# W952.net
KiCad netlist of a schematic drawn in EAGLE
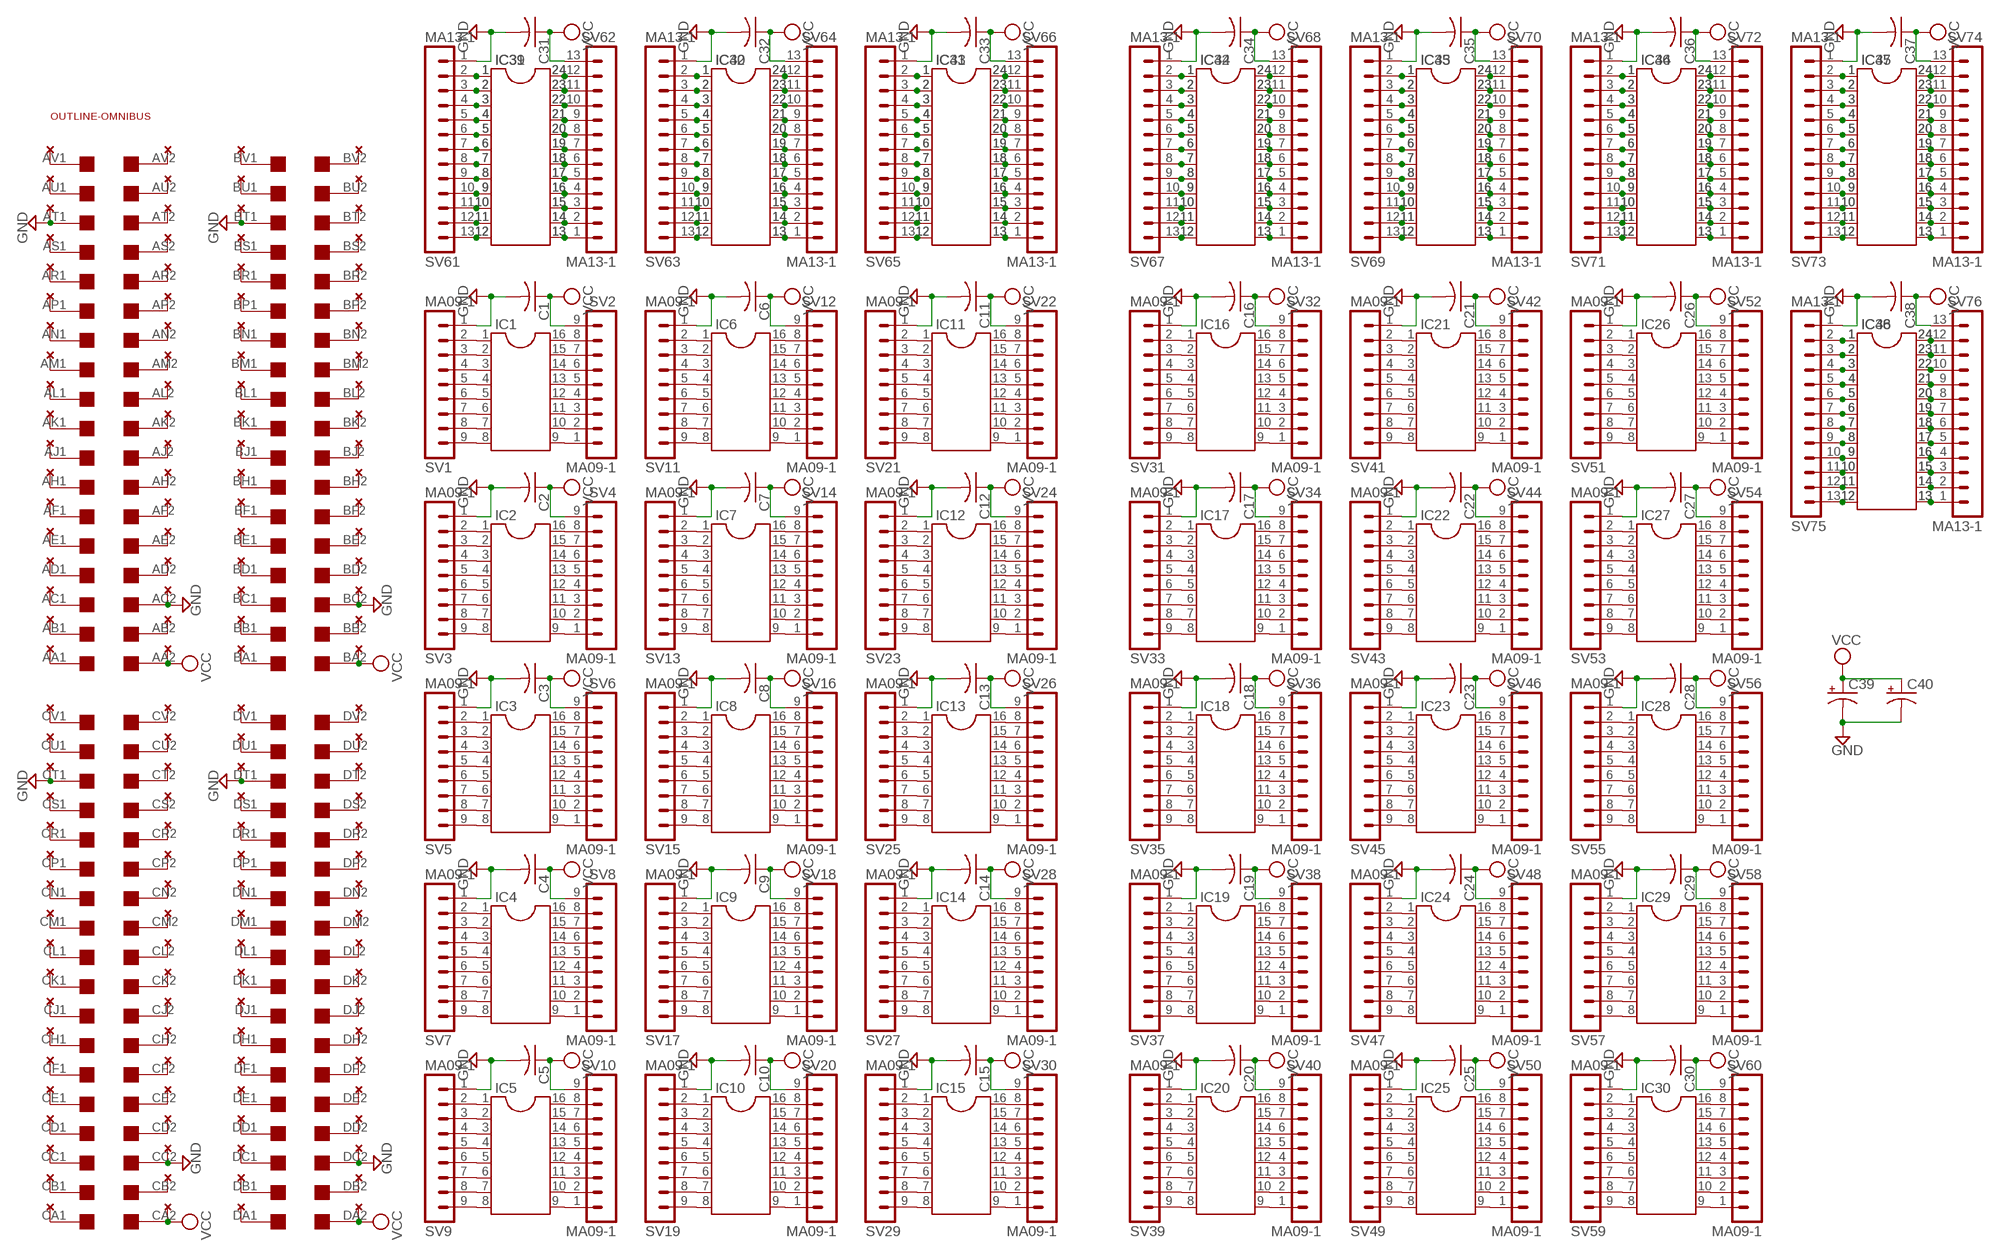
[diagram p0: schematic, sheet 1]

(export (version "E")
  (design (tool "Eeschema 10.0.6"))
  (components
    (comp (ref "C1")
      (value "C-US075-032X103")
      (footprint "eagle-import:C075-032X103")
      (libsource (lib "eagle-import") (part "C-US075-032X103"))
    )
    (comp (ref "C2")
      (value "C-US075-032X103")
      (footprint "eagle-import:C075-032X103")
      (libsource (lib "eagle-import") (part "C-US075-032X103"))
    )
    (comp (ref "C3")
      (value "C-US075-032X103")
      (footprint "eagle-import:C075-032X103")
      (libsource (lib "eagle-import") (part "C-US075-032X103"))
    )
    (comp (ref "C4")
      (value "C-US075-032X103")
      (footprint "eagle-import:C075-032X103")
      (libsource (lib "eagle-import") (part "C-US075-032X103"))
    )
    (comp (ref "C5")
      (value "C-US075-032X103")
      (footprint "eagle-import:C075-032X103")
      (libsource (lib "eagle-import") (part "C-US075-032X103"))
    )
    (comp (ref "C6")
      (value "C-US075-032X103")
      (footprint "eagle-import:C075-032X103")
      (libsource (lib "eagle-import") (part "C-US075-032X103"))
    )
    (comp (ref "C7")
      (value "C-US075-032X103")
      (footprint "eagle-import:C075-032X103")
      (libsource (lib "eagle-import") (part "C-US075-032X103"))
    )
    (comp (ref "C8")
      (value "C-US075-032X103")
      (footprint "eagle-import:C075-032X103")
      (libsource (lib "eagle-import") (part "C-US075-032X103"))
    )
    (comp (ref "C9")
      (value "C-US075-032X103")
      (footprint "eagle-import:C075-032X103")
      (libsource (lib "eagle-import") (part "C-US075-032X103"))
    )
    (comp (ref "C10")
      (value "C-US075-032X103")
      (footprint "eagle-import:C075-032X103")
      (libsource (lib "eagle-import") (part "C-US075-032X103"))
    )
    (comp (ref "C11")
      (value "C-US075-032X103")
      (footprint "eagle-import:C075-032X103")
      (libsource (lib "eagle-import") (part "C-US075-032X103"))
    )
    (comp (ref "C12")
      (value "C-US075-032X103")
      (footprint "eagle-import:C075-032X103")
      (libsource (lib "eagle-import") (part "C-US075-032X103"))
    )
    (comp (ref "C13")
      (value "C-US075-032X103")
      (footprint "eagle-import:C075-032X103")
      (libsource (lib "eagle-import") (part "C-US075-032X103"))
    )
    (comp (ref "C14")
      (value "C-US075-032X103")
      (footprint "eagle-import:C075-032X103")
      (libsource (lib "eagle-import") (part "C-US075-032X103"))
    )
    (comp (ref "C15")
      (value "C-US075-032X103")
      (footprint "eagle-import:C075-032X103")
      (libsource (lib "eagle-import") (part "C-US075-032X103"))
    )
    (comp (ref "C16")
      (value "C-US075-032X103")
      (footprint "eagle-import:C075-032X103")
      (libsource (lib "eagle-import") (part "C-US075-032X103"))
    )
    (comp (ref "C17")
      (value "C-US075-032X103")
      (footprint "eagle-import:C075-032X103")
      (libsource (lib "eagle-import") (part "C-US075-032X103"))
    )
    (comp (ref "C18")
      (value "C-US075-032X103")
      (footprint "eagle-import:C075-032X103")
      (libsource (lib "eagle-import") (part "C-US075-032X103"))
    )
    (comp (ref "C19")
      (value "C-US075-032X103")
      (footprint "eagle-import:C075-032X103")
      (libsource (lib "eagle-import") (part "C-US075-032X103"))
    )
    (comp (ref "C20")
      (value "C-US075-032X103")
      (footprint "eagle-import:C075-032X103")
      (libsource (lib "eagle-import") (part "C-US075-032X103"))
    )
    (comp (ref "C21")
      (value "C-US075-032X103")
      (footprint "eagle-import:C075-032X103")
      (libsource (lib "eagle-import") (part "C-US075-032X103"))
    )
    (comp (ref "C22")
      (value "C-US075-032X103")
      (footprint "eagle-import:C075-032X103")
      (libsource (lib "eagle-import") (part "C-US075-032X103"))
    )
    (comp (ref "C23")
      (value "C-US075-032X103")
      (footprint "eagle-import:C075-032X103")
      (libsource (lib "eagle-import") (part "C-US075-032X103"))
    )
    (comp (ref "C24")
      (value "C-US075-032X103")
      (footprint "eagle-import:C075-032X103")
      (libsource (lib "eagle-import") (part "C-US075-032X103"))
    )
    (comp (ref "C25")
      (value "C-US075-032X103")
      (footprint "eagle-import:C075-032X103")
      (libsource (lib "eagle-import") (part "C-US075-032X103"))
    )
    (comp (ref "C26")
      (value "C-US075-032X103")
      (footprint "eagle-import:C075-032X103")
      (libsource (lib "eagle-import") (part "C-US075-032X103"))
    )
    (comp (ref "C27")
      (value "C-US075-032X103")
      (footprint "eagle-import:C075-032X103")
      (libsource (lib "eagle-import") (part "C-US075-032X103"))
    )
    (comp (ref "C28")
      (value "C-US075-032X103")
      (footprint "eagle-import:C075-032X103")
      (libsource (lib "eagle-import") (part "C-US075-032X103"))
    )
    (comp (ref "C29")
      (value "C-US075-032X103")
      (footprint "eagle-import:C075-032X103")
      (libsource (lib "eagle-import") (part "C-US075-032X103"))
    )
    (comp (ref "C30")
      (value "C-US075-032X103")
      (footprint "eagle-import:C075-032X103")
      (libsource (lib "eagle-import") (part "C-US075-032X103"))
    )
    (comp (ref "C31")
      (value "C-US075-032X103")
      (footprint "eagle-import:C075-032X103")
      (libsource (lib "eagle-import") (part "C-US075-032X103"))
    )
    (comp (ref "C32")
      (value "C-US075-032X103")
      (footprint "eagle-import:C075-032X103")
      (libsource (lib "eagle-import") (part "C-US075-032X103"))
    )
    (comp (ref "C33")
      (value "C-US075-032X103")
      (footprint "eagle-import:C075-032X103")
      (libsource (lib "eagle-import") (part "C-US075-032X103"))
    )
    (comp (ref "C34")
      (value "C-US075-032X103")
      (footprint "eagle-import:C075-032X103")
      (libsource (lib "eagle-import") (part "C-US075-032X103"))
    )
    (comp (ref "C35")
      (value "C-US075-032X103")
      (footprint "eagle-import:C075-032X103")
      (libsource (lib "eagle-import") (part "C-US075-032X103"))
    )
    (comp (ref "C36")
      (value "C-US075-032X103")
      (footprint "eagle-import:C075-032X103")
      (libsource (lib "eagle-import") (part "C-US075-032X103"))
    )
    (comp (ref "C37")
      (value "C-US075-032X103")
      (footprint "eagle-import:C075-032X103")
      (libsource (lib "eagle-import") (part "C-US075-032X103"))
    )
    (comp (ref "C38")
      (value "C-US075-032X103")
      (footprint "eagle-import:C075-032X103")
      (libsource (lib "eagle-import") (part "C-US075-032X103"))
    )
    (comp (ref "C39")
      (value "CPOL-USE15-5AXIAL")
      (footprint "eagle-import:E15-5")
      (libsource (lib "eagle-import") (part "CPOL-USE15-5AXIAL"))
    )
    (comp (ref "C40")
      (value "CPOL-USE15-5AXIAL")
      (footprint "eagle-import:E15-5")
      (libsource (lib "eagle-import") (part "CPOL-USE15-5AXIAL"))
    )
    (comp (ref "IC1")
      (value "DIL16S")
      (footprint "eagle-import:SOCKET-16")
      (libsource (lib "eagle-import") (part "DIL16S"))
    )
    (comp (ref "IC2")
      (value "DIL16S")
      (footprint "eagle-import:SOCKET-16")
      (libsource (lib "eagle-import") (part "DIL16S"))
    )
    (comp (ref "IC3")
      (value "DIL16S")
      (footprint "eagle-import:SOCKET-16")
      (libsource (lib "eagle-import") (part "DIL16S"))
    )
    (comp (ref "IC4")
      (value "DIL16S")
      (footprint "eagle-import:SOCKET-16")
      (libsource (lib "eagle-import") (part "DIL16S"))
    )
    (comp (ref "IC5")
      (value "DIL16S")
      (footprint "eagle-import:SOCKET-16")
      (libsource (lib "eagle-import") (part "DIL16S"))
    )
    (comp (ref "IC6")
      (value "DIL16S")
      (footprint "eagle-import:SOCKET-16")
      (libsource (lib "eagle-import") (part "DIL16S"))
    )
    (comp (ref "IC7")
      (value "DIL16S")
      (footprint "eagle-import:SOCKET-16")
      (libsource (lib "eagle-import") (part "DIL16S"))
    )
    (comp (ref "IC8")
      (value "DIL16S")
      (footprint "eagle-import:SOCKET-16")
      (libsource (lib "eagle-import") (part "DIL16S"))
    )
    (comp (ref "IC9")
      (value "DIL16S")
      (footprint "eagle-import:SOCKET-16")
      (libsource (lib "eagle-import") (part "DIL16S"))
    )
    (comp (ref "IC10")
      (value "DIL16S")
      (footprint "eagle-import:SOCKET-16")
      (libsource (lib "eagle-import") (part "DIL16S"))
    )
    (comp (ref "IC11")
      (value "DIL16S")
      (footprint "eagle-import:SOCKET-16")
      (libsource (lib "eagle-import") (part "DIL16S"))
    )
    (comp (ref "IC12")
      (value "DIL16S")
      (footprint "eagle-import:SOCKET-16")
      (libsource (lib "eagle-import") (part "DIL16S"))
    )
    (comp (ref "IC13")
      (value "DIL16S")
      (footprint "eagle-import:SOCKET-16")
      (libsource (lib "eagle-import") (part "DIL16S"))
    )
    (comp (ref "IC14")
      (value "DIL16S")
      (footprint "eagle-import:SOCKET-16")
      (libsource (lib "eagle-import") (part "DIL16S"))
    )
    (comp (ref "IC15")
      (value "DIL16S")
      (footprint "eagle-import:SOCKET-16")
      (libsource (lib "eagle-import") (part "DIL16S"))
    )
    (comp (ref "IC16")
      (value "DIL16S")
      (footprint "eagle-import:SOCKET-16")
      (libsource (lib "eagle-import") (part "DIL16S"))
    )
    (comp (ref "IC17")
      (value "DIL16S")
      (footprint "eagle-import:SOCKET-16")
      (libsource (lib "eagle-import") (part "DIL16S"))
    )
    (comp (ref "IC18")
      (value "DIL16S")
      (footprint "eagle-import:SOCKET-16")
      (libsource (lib "eagle-import") (part "DIL16S"))
    )
    (comp (ref "IC19")
      (value "DIL16S")
      (footprint "eagle-import:SOCKET-16")
      (libsource (lib "eagle-import") (part "DIL16S"))
    )
    (comp (ref "IC20")
      (value "DIL16S")
      (footprint "eagle-import:SOCKET-16")
      (libsource (lib "eagle-import") (part "DIL16S"))
    )
    (comp (ref "IC21")
      (value "DIL16S")
      (footprint "eagle-import:SOCKET-16")
      (libsource (lib "eagle-import") (part "DIL16S"))
    )
    (comp (ref "IC22")
      (value "DIL16S")
      (footprint "eagle-import:SOCKET-16")
      (libsource (lib "eagle-import") (part "DIL16S"))
    )
    (comp (ref "IC23")
      (value "DIL16S")
      (footprint "eagle-import:SOCKET-16")
      (libsource (lib "eagle-import") (part "DIL16S"))
    )
    (comp (ref "IC24")
      (value "DIL16S")
      (footprint "eagle-import:SOCKET-16")
      (libsource (lib "eagle-import") (part "DIL16S"))
    )
    (comp (ref "IC25")
      (value "DIL16S")
      (footprint "eagle-import:SOCKET-16")
      (libsource (lib "eagle-import") (part "DIL16S"))
    )
    (comp (ref "IC26")
      (value "DIL16S")
      (footprint "eagle-import:SOCKET-16")
      (libsource (lib "eagle-import") (part "DIL16S"))
    )
    (comp (ref "IC27")
      (value "DIL16S")
      (footprint "eagle-import:SOCKET-16")
      (libsource (lib "eagle-import") (part "DIL16S"))
    )
    (comp (ref "IC28")
      (value "DIL16S")
      (footprint "eagle-import:SOCKET-16")
      (libsource (lib "eagle-import") (part "DIL16S"))
    )
    (comp (ref "IC29")
      (value "DIL16S")
      (footprint "eagle-import:SOCKET-16")
      (libsource (lib "eagle-import") (part "DIL16S"))
    )
    (comp (ref "IC30")
      (value "DIL16S")
      (footprint "eagle-import:SOCKET-16")
      (libsource (lib "eagle-import") (part "DIL16S"))
    )
    (comp (ref "IC31")
      (value "DIL24-6")
      (footprint "eagle-import:DIL24-6")
      (libsource (lib "eagle-import") (part "DIL24-6"))
    )
    (comp (ref "IC32")
      (value "DIL24-6")
      (footprint "eagle-import:DIL24-6")
      (libsource (lib "eagle-import") (part "DIL24-6"))
    )
    (comp (ref "IC33")
      (value "DIL24-6")
      (footprint "eagle-import:DIL24-6")
      (libsource (lib "eagle-import") (part "DIL24-6"))
    )
    (comp (ref "IC34")
      (value "DIL24-6")
      (footprint "eagle-import:DIL24-6")
      (libsource (lib "eagle-import") (part "DIL24-6"))
    )
    (comp (ref "IC35")
      (value "DIL24-6")
      (footprint "eagle-import:DIL24-6")
      (libsource (lib "eagle-import") (part "DIL24-6"))
    )
    (comp (ref "IC36")
      (value "DIL24-6")
      (footprint "eagle-import:DIL24-6")
      (libsource (lib "eagle-import") (part "DIL24-6"))
    )
    (comp (ref "IC37")
      (value "DIL24-6")
      (footprint "eagle-import:DIL24-6")
      (libsource (lib "eagle-import") (part "DIL24-6"))
    )
    (comp (ref "IC38")
      (value "DIL24-6")
      (footprint "eagle-import:DIL24-6")
      (libsource (lib "eagle-import") (part "DIL24-6"))
    )
    (comp (ref "IC39")
      (value "DIL24-3")
      (footprint "eagle-import:DIL24-3")
      (libsource (lib "eagle-import") (part "DIL24-3"))
    )
    (comp (ref "IC40")
      (value "DIL24-3")
      (footprint "eagle-import:DIL24-3")
      (libsource (lib "eagle-import") (part "DIL24-3"))
    )
    (comp (ref "IC41")
      (value "DIL24-3")
      (footprint "eagle-import:DIL24-3")
      (libsource (lib "eagle-import") (part "DIL24-3"))
    )
    (comp (ref "IC42")
      (value "DIL24-3")
      (footprint "eagle-import:DIL24-3")
      (libsource (lib "eagle-import") (part "DIL24-3"))
    )
    (comp (ref "IC43")
      (value "DIL24-3")
      (footprint "eagle-import:DIL24-3")
      (libsource (lib "eagle-import") (part "DIL24-3"))
    )
    (comp (ref "IC44")
      (value "DIL24-3")
      (footprint "eagle-import:DIL24-3")
      (libsource (lib "eagle-import") (part "DIL24-3"))
    )
    (comp (ref "IC45")
      (value "DIL24-3")
      (footprint "eagle-import:DIL24-3")
      (libsource (lib "eagle-import") (part "DIL24-3"))
    )
    (comp (ref "IC46")
      (value "DIL24-3")
      (footprint "eagle-import:DIL24-3")
      (libsource (lib "eagle-import") (part "DIL24-3"))
    )
    (comp (ref "SV1")
      (value "MA09-1")
      (footprint "eagle-import:MA09-1")
      (libsource (lib "eagle-import") (part "MA09-1"))
    )
    (comp (ref "SV2")
      (value "MA09-1")
      (footprint "eagle-import:MA09-1")
      (libsource (lib "eagle-import") (part "MA09-1"))
    )
    (comp (ref "SV3")
      (value "MA09-1")
      (footprint "eagle-import:MA09-1")
      (libsource (lib "eagle-import") (part "MA09-1"))
    )
    (comp (ref "SV4")
      (value "MA09-1")
      (footprint "eagle-import:MA09-1")
      (libsource (lib "eagle-import") (part "MA09-1"))
    )
    (comp (ref "SV5")
      (value "MA09-1")
      (footprint "eagle-import:MA09-1")
      (libsource (lib "eagle-import") (part "MA09-1"))
    )
    (comp (ref "SV6")
      (value "MA09-1")
      (footprint "eagle-import:MA09-1")
      (libsource (lib "eagle-import") (part "MA09-1"))
    )
    (comp (ref "SV7")
      (value "MA09-1")
      (footprint "eagle-import:MA09-1")
      (libsource (lib "eagle-import") (part "MA09-1"))
    )
    (comp (ref "SV8")
      (value "MA09-1")
      (footprint "eagle-import:MA09-1")
      (libsource (lib "eagle-import") (part "MA09-1"))
    )
    (comp (ref "SV9")
      (value "MA09-1")
      (footprint "eagle-import:MA09-1")
      (libsource (lib "eagle-import") (part "MA09-1"))
    )
    (comp (ref "SV10")
      (value "MA09-1")
      (footprint "eagle-import:MA09-1")
      (libsource (lib "eagle-import") (part "MA09-1"))
    )
    (comp (ref "SV11")
      (value "MA09-1")
      (footprint "eagle-import:MA09-1")
      (libsource (lib "eagle-import") (part "MA09-1"))
    )
    (comp (ref "SV12")
      (value "MA09-1")
      (footprint "eagle-import:MA09-1")
      (libsource (lib "eagle-import") (part "MA09-1"))
    )
    (comp (ref "SV13")
      (value "MA09-1")
      (footprint "eagle-import:MA09-1")
      (libsource (lib "eagle-import") (part "MA09-1"))
    )
    (comp (ref "SV14")
      (value "MA09-1")
      (footprint "eagle-import:MA09-1")
      (libsource (lib "eagle-import") (part "MA09-1"))
    )
    (comp (ref "SV15")
      (value "MA09-1")
      (footprint "eagle-import:MA09-1")
      (libsource (lib "eagle-import") (part "MA09-1"))
    )
    (comp (ref "SV16")
      (value "MA09-1")
      (footprint "eagle-import:MA09-1")
      (libsource (lib "eagle-import") (part "MA09-1"))
    )
    (comp (ref "SV17")
      (value "MA09-1")
      (footprint "eagle-import:MA09-1")
      (libsource (lib "eagle-import") (part "MA09-1"))
    )
    (comp (ref "SV18")
      (value "MA09-1")
      (footprint "eagle-import:MA09-1")
      (libsource (lib "eagle-import") (part "MA09-1"))
    )
    (comp (ref "SV19")
      (value "MA09-1")
      (footprint "eagle-import:MA09-1")
      (libsource (lib "eagle-import") (part "MA09-1"))
    )
    (comp (ref "SV20")
      (value "MA09-1")
      (footprint "eagle-import:MA09-1")
      (libsource (lib "eagle-import") (part "MA09-1"))
    )
    (comp (ref "SV21")
      (value "MA09-1")
      (footprint "eagle-import:MA09-1")
      (libsource (lib "eagle-import") (part "MA09-1"))
    )
    (comp (ref "SV22")
      (value "MA09-1")
      (footprint "eagle-import:MA09-1")
      (libsource (lib "eagle-import") (part "MA09-1"))
    )
    (comp (ref "SV23")
      (value "MA09-1")
      (footprint "eagle-import:MA09-1")
      (libsource (lib "eagle-import") (part "MA09-1"))
    )
    (comp (ref "SV24")
      (value "MA09-1")
      (footprint "eagle-import:MA09-1")
      (libsource (lib "eagle-import") (part "MA09-1"))
    )
    (comp (ref "SV25")
      (value "MA09-1")
      (footprint "eagle-import:MA09-1")
      (libsource (lib "eagle-import") (part "MA09-1"))
    )
    (comp (ref "SV26")
      (value "MA09-1")
      (footprint "eagle-import:MA09-1")
      (libsource (lib "eagle-import") (part "MA09-1"))
    )
    (comp (ref "SV27")
      (value "MA09-1")
      (footprint "eagle-import:MA09-1")
      (libsource (lib "eagle-import") (part "MA09-1"))
    )
    (comp (ref "SV28")
      (value "MA09-1")
      (footprint "eagle-import:MA09-1")
      (libsource (lib "eagle-import") (part "MA09-1"))
    )
    (comp (ref "SV29")
      (value "MA09-1")
      (footprint "eagle-import:MA09-1")
      (libsource (lib "eagle-import") (part "MA09-1"))
    )
    (comp (ref "SV30")
      (value "MA09-1")
      (footprint "eagle-import:MA09-1")
      (libsource (lib "eagle-import") (part "MA09-1"))
    )
    (comp (ref "SV31")
      (value "MA09-1")
      (footprint "eagle-import:MA09-1")
      (libsource (lib "eagle-import") (part "MA09-1"))
    )
    (comp (ref "SV32")
      (value "MA09-1")
      (footprint "eagle-import:MA09-1")
      (libsource (lib "eagle-import") (part "MA09-1"))
    )
    (comp (ref "SV33")
      (value "MA09-1")
      (footprint "eagle-import:MA09-1")
      (libsource (lib "eagle-import") (part "MA09-1"))
    )
    (comp (ref "SV34")
      (value "MA09-1")
      (footprint "eagle-import:MA09-1")
      (libsource (lib "eagle-import") (part "MA09-1"))
    )
    (comp (ref "SV35")
      (value "MA09-1")
      (footprint "eagle-import:MA09-1")
      (libsource (lib "eagle-import") (part "MA09-1"))
    )
    (comp (ref "SV36")
      (value "MA09-1")
      (footprint "eagle-import:MA09-1")
      (libsource (lib "eagle-import") (part "MA09-1"))
    )
    (comp (ref "SV37")
      (value "MA09-1")
      (footprint "eagle-import:MA09-1")
      (libsource (lib "eagle-import") (part "MA09-1"))
    )
    (comp (ref "SV38")
      (value "MA09-1")
      (footprint "eagle-import:MA09-1")
      (libsource (lib "eagle-import") (part "MA09-1"))
    )
    (comp (ref "SV39")
      (value "MA09-1")
      (footprint "eagle-import:MA09-1")
      (libsource (lib "eagle-import") (part "MA09-1"))
    )
    (comp (ref "SV40")
      (value "MA09-1")
      (footprint "eagle-import:MA09-1")
      (libsource (lib "eagle-import") (part "MA09-1"))
    )
    (comp (ref "SV41")
      (value "MA09-1")
      (footprint "eagle-import:MA09-1")
      (libsource (lib "eagle-import") (part "MA09-1"))
    )
    (comp (ref "SV42")
      (value "MA09-1")
      (footprint "eagle-import:MA09-1")
      (libsource (lib "eagle-import") (part "MA09-1"))
    )
    (comp (ref "SV43")
      (value "MA09-1")
      (footprint "eagle-import:MA09-1")
      (libsource (lib "eagle-import") (part "MA09-1"))
    )
    (comp (ref "SV44")
      (value "MA09-1")
      (footprint "eagle-import:MA09-1")
      (libsource (lib "eagle-import") (part "MA09-1"))
    )
    (comp (ref "SV45")
      (value "MA09-1")
      (footprint "eagle-import:MA09-1")
      (libsource (lib "eagle-import") (part "MA09-1"))
    )
    (comp (ref "SV46")
      (value "MA09-1")
      (footprint "eagle-import:MA09-1")
      (libsource (lib "eagle-import") (part "MA09-1"))
    )
    (comp (ref "SV47")
      (value "MA09-1")
      (footprint "eagle-import:MA09-1")
      (libsource (lib "eagle-import") (part "MA09-1"))
    )
    (comp (ref "SV48")
      (value "MA09-1")
      (footprint "eagle-import:MA09-1")
      (libsource (lib "eagle-import") (part "MA09-1"))
    )
    (comp (ref "SV49")
      (value "MA09-1")
      (footprint "eagle-import:MA09-1")
      (libsource (lib "eagle-import") (part "MA09-1"))
    )
    (comp (ref "SV50")
      (value "MA09-1")
      (footprint "eagle-import:MA09-1")
      (libsource (lib "eagle-import") (part "MA09-1"))
    )
    (comp (ref "SV51")
      (value "MA09-1")
      (footprint "eagle-import:MA09-1")
      (libsource (lib "eagle-import") (part "MA09-1"))
    )
    (comp (ref "SV52")
      (value "MA09-1")
      (footprint "eagle-import:MA09-1")
      (libsource (lib "eagle-import") (part "MA09-1"))
    )
    (comp (ref "SV53")
      (value "MA09-1")
      (footprint "eagle-import:MA09-1")
      (libsource (lib "eagle-import") (part "MA09-1"))
    )
    (comp (ref "SV54")
      (value "MA09-1")
      (footprint "eagle-import:MA09-1")
      (libsource (lib "eagle-import") (part "MA09-1"))
    )
    (comp (ref "SV55")
      (value "MA09-1")
      (footprint "eagle-import:MA09-1")
      (libsource (lib "eagle-import") (part "MA09-1"))
    )
    (comp (ref "SV56")
      (value "MA09-1")
      (footprint "eagle-import:MA09-1")
      (libsource (lib "eagle-import") (part "MA09-1"))
    )
    (comp (ref "SV57")
      (value "MA09-1")
      (footprint "eagle-import:MA09-1")
      (libsource (lib "eagle-import") (part "MA09-1"))
    )
    (comp (ref "SV58")
      (value "MA09-1")
      (footprint "eagle-import:MA09-1")
      (libsource (lib "eagle-import") (part "MA09-1"))
    )
    (comp (ref "SV59")
      (value "MA09-1")
      (footprint "eagle-import:MA09-1")
      (libsource (lib "eagle-import") (part "MA09-1"))
    )
    (comp (ref "SV60")
      (value "MA09-1")
      (footprint "eagle-import:MA09-1")
      (libsource (lib "eagle-import") (part "MA09-1"))
    )
    (comp (ref "SV61")
      (value "MA13-1")
      (footprint "eagle-import:MA13-1")
      (libsource (lib "eagle-import") (part "MA13-1"))
    )
    (comp (ref "SV62")
      (value "MA13-1")
      (footprint "eagle-import:MA13-1")
      (libsource (lib "eagle-import") (part "MA13-1"))
    )
    (comp (ref "SV63")
      (value "MA13-1")
      (footprint "eagle-import:MA13-1")
      (libsource (lib "eagle-import") (part "MA13-1"))
    )
    (comp (ref "SV64")
      (value "MA13-1")
      (footprint "eagle-import:MA13-1")
      (libsource (lib "eagle-import") (part "MA13-1"))
    )
    (comp (ref "SV65")
      (value "MA13-1")
      (footprint "eagle-import:MA13-1")
      (libsource (lib "eagle-import") (part "MA13-1"))
    )
    (comp (ref "SV66")
      (value "MA13-1")
      (footprint "eagle-import:MA13-1")
      (libsource (lib "eagle-import") (part "MA13-1"))
    )
    (comp (ref "SV67")
      (value "MA13-1")
      (footprint "eagle-import:MA13-1")
      (libsource (lib "eagle-import") (part "MA13-1"))
    )
    (comp (ref "SV68")
      (value "MA13-1")
      (footprint "eagle-import:MA13-1")
      (libsource (lib "eagle-import") (part "MA13-1"))
    )
    (comp (ref "SV69")
      (value "MA13-1")
      (footprint "eagle-import:MA13-1")
      (libsource (lib "eagle-import") (part "MA13-1"))
    )
    (comp (ref "SV70")
      (value "MA13-1")
      (footprint "eagle-import:MA13-1")
      (libsource (lib "eagle-import") (part "MA13-1"))
    )
    (comp (ref "SV71")
      (value "MA13-1")
      (footprint "eagle-import:MA13-1")
      (libsource (lib "eagle-import") (part "MA13-1"))
    )
    (comp (ref "SV72")
      (value "MA13-1")
      (footprint "eagle-import:MA13-1")
      (libsource (lib "eagle-import") (part "MA13-1"))
    )
    (comp (ref "SV73")
      (value "MA13-1")
      (footprint "eagle-import:MA13-1")
      (libsource (lib "eagle-import") (part "MA13-1"))
    )
    (comp (ref "SV74")
      (value "MA13-1")
      (footprint "eagle-import:MA13-1")
      (libsource (lib "eagle-import") (part "MA13-1"))
    )
    (comp (ref "SV75")
      (value "MA13-1")
      (footprint "eagle-import:MA13-1")
      (libsource (lib "eagle-import") (part "MA13-1"))
    )
    (comp (ref "SV76")
      (value "MA13-1")
      (footprint "eagle-import:MA13-1")
      (libsource (lib "eagle-import") (part "MA13-1"))
    )
    (comp (ref "U$1")
      (value "QUAD")
      (footprint "eagle-import:EDGE-CON8")
      (libsource (lib "eagle-import") (part "QUAD"))
    )
    (comp (ref "U$2")
      (value "THRU-HOLE2W")
      (footprint "eagle-import:THRU-HOLE2")
      (libsource (lib "eagle-import") (part "THRU-HOLE2W"))
    )
    (comp (ref "U$3")
      (value "THRU-HOLE2W")
      (footprint "eagle-import:THRU-HOLE2")
      (libsource (lib "eagle-import") (part "THRU-HOLE2W"))
    )
    (comp (ref "U$4")
      (value "THRU-HOLE2W")
      (footprint "eagle-import:THRU-HOLE2")
      (libsource (lib "eagle-import") (part "THRU-HOLE2W"))
    )
    (comp (ref "U$5")
      (value "THRU-HOLE2W")
      (footprint "eagle-import:THRU-HOLE2")
      (libsource (lib "eagle-import") (part "THRU-HOLE2W"))
    )
    (comp (ref "U$8")
      (value "OUTLINE-OMNIBUS")
      (footprint "eagle-import:OMNIBUS")
      (libsource (lib "eagle-import") (part "OUTLINE-OMNIBUS"))
    )
  )
  (nets
    (net (code "1") (name "GND") (class "Default")
      (node (ref "C1") (pin "2") (pinfunction "2_2") (pintype "passive"))
      (node (ref "C10") (pin "2") (pinfunction "2_2") (pintype "passive"))
      (node (ref "C11") (pin "2") (pinfunction "2_2") (pintype "passive"))
      (node (ref "C12") (pin "2") (pinfunction "2_2") (pintype "passive"))
      (node (ref "C13") (pin "2") (pinfunction "2_2") (pintype "passive"))
      (node (ref "C14") (pin "2") (pinfunction "2_2") (pintype "passive"))
      (node (ref "C15") (pin "2") (pinfunction "2_2") (pintype "passive"))
      (node (ref "C16") (pin "2") (pinfunction "2_2") (pintype "passive"))
      (node (ref "C17") (pin "2") (pinfunction "2_2") (pintype "passive"))
      (node (ref "C18") (pin "2") (pinfunction "2_2") (pintype "passive"))
      (node (ref "C19") (pin "2") (pinfunction "2_2") (pintype "passive"))
      (node (ref "C2") (pin "2") (pinfunction "2_2") (pintype "passive"))
      (node (ref "C20") (pin "2") (pinfunction "2_2") (pintype "passive"))
      (node (ref "C21") (pin "2") (pinfunction "2_2") (pintype "passive"))
      (node (ref "C22") (pin "2") (pinfunction "2_2") (pintype "passive"))
      (node (ref "C23") (pin "2") (pinfunction "2_2") (pintype "passive"))
      (node (ref "C24") (pin "2") (pinfunction "2_2") (pintype "passive"))
      (node (ref "C25") (pin "2") (pinfunction "2_2") (pintype "passive"))
      (node (ref "C26") (pin "2") (pinfunction "2_2") (pintype "passive"))
      (node (ref "C27") (pin "2") (pinfunction "2_2") (pintype "passive"))
      (node (ref "C28") (pin "2") (pinfunction "2_2") (pintype "passive"))
      (node (ref "C29") (pin "2") (pinfunction "2_2") (pintype "passive"))
      (node (ref "C3") (pin "2") (pinfunction "2_2") (pintype "passive"))
      (node (ref "C30") (pin "2") (pinfunction "2_2") (pintype "passive"))
      (node (ref "C31") (pin "2") (pinfunction "2_2") (pintype "passive"))
      (node (ref "C32") (pin "2") (pinfunction "2_2") (pintype "passive"))
      (node (ref "C33") (pin "2") (pinfunction "2_2") (pintype "passive"))
      (node (ref "C34") (pin "2") (pinfunction "2_2") (pintype "passive"))
      (node (ref "C35") (pin "2") (pinfunction "2_2") (pintype "passive"))
      (node (ref "C36") (pin "2") (pinfunction "2_2") (pintype "passive"))
      (node (ref "C37") (pin "2") (pinfunction "2_2") (pintype "passive"))
      (node (ref "C38") (pin "2") (pinfunction "2_2") (pintype "passive"))
      (node (ref "C39") (pin "-") (pinfunction "-_-") (pintype "passive"))
      (node (ref "C4") (pin "2") (pinfunction "2_2") (pintype "passive"))
      (node (ref "C40") (pin "-") (pinfunction "-_-") (pintype "passive"))
      (node (ref "C5") (pin "2") (pinfunction "2_2") (pintype "passive"))
      (node (ref "C6") (pin "2") (pinfunction "2_2") (pintype "passive"))
      (node (ref "C7") (pin "2") (pinfunction "2_2") (pintype "passive"))
      (node (ref "C8") (pin "2") (pinfunction "2_2") (pintype "passive"))
      (node (ref "C9") (pin "2") (pinfunction "2_2") (pintype "passive"))
      (node (ref "SV1") (pin "1") (pinfunction "1_1") (pintype "passive"))
      (node (ref "SV11") (pin "1") (pinfunction "1_1") (pintype "passive"))
      (node (ref "SV13") (pin "1") (pinfunction "1_1") (pintype "passive"))
      (node (ref "SV15") (pin "1") (pinfunction "1_1") (pintype "passive"))
      (node (ref "SV17") (pin "1") (pinfunction "1_1") (pintype "passive"))
      (node (ref "SV19") (pin "1") (pinfunction "1_1") (pintype "passive"))
      (node (ref "SV21") (pin "1") (pinfunction "1_1") (pintype "passive"))
      (node (ref "SV23") (pin "1") (pinfunction "1_1") (pintype "passive"))
      (node (ref "SV25") (pin "1") (pinfunction "1_1") (pintype "passive"))
      (node (ref "SV27") (pin "1") (pinfunction "1_1") (pintype "passive"))
      (node (ref "SV29") (pin "1") (pinfunction "1_1") (pintype "passive"))
      (node (ref "SV3") (pin "1") (pinfunction "1_1") (pintype "passive"))
      (node (ref "SV31") (pin "1") (pinfunction "1_1") (pintype "passive"))
      (node (ref "SV33") (pin "1") (pinfunction "1_1") (pintype "passive"))
      (node (ref "SV35") (pin "1") (pinfunction "1_1") (pintype "passive"))
      (node (ref "SV37") (pin "1") (pinfunction "1_1") (pintype "passive"))
      (node (ref "SV39") (pin "1") (pinfunction "1_1") (pintype "passive"))
      (node (ref "SV41") (pin "1") (pinfunction "1_1") (pintype "passive"))
      (node (ref "SV43") (pin "1") (pinfunction "1_1") (pintype "passive"))
      (node (ref "SV45") (pin "1") (pinfunction "1_1") (pintype "passive"))
      (node (ref "SV47") (pin "1") (pinfunction "1_1") (pintype "passive"))
      (node (ref "SV49") (pin "1") (pinfunction "1_1") (pintype "passive"))
      (node (ref "SV5") (pin "1") (pinfunction "1_1") (pintype "passive"))
      (node (ref "SV51") (pin "1") (pinfunction "1_1") (pintype "passive"))
      (node (ref "SV53") (pin "1") (pinfunction "1_1") (pintype "passive"))
      (node (ref "SV55") (pin "1") (pinfunction "1_1") (pintype "passive"))
      (node (ref "SV57") (pin "1") (pinfunction "1_1") (pintype "passive"))
      (node (ref "SV59") (pin "1") (pinfunction "1_1") (pintype "passive"))
      (node (ref "SV61") (pin "1") (pinfunction "1_1") (pintype "passive"))
      (node (ref "SV63") (pin "1") (pinfunction "1_1") (pintype "passive"))
      (node (ref "SV65") (pin "1") (pinfunction "1_1") (pintype "passive"))
      (node (ref "SV67") (pin "1") (pinfunction "1_1") (pintype "passive"))
      (node (ref "SV69") (pin "1") (pinfunction "1_1") (pintype "passive"))
      (node (ref "SV7") (pin "1") (pinfunction "1_1") (pintype "passive"))
      (node (ref "SV71") (pin "1") (pinfunction "1_1") (pintype "passive"))
      (node (ref "SV73") (pin "1") (pinfunction "1_1") (pintype "passive"))
      (node (ref "SV75") (pin "1") (pinfunction "1_1") (pintype "passive"))
      (node (ref "SV9") (pin "1") (pinfunction "1_1") (pintype "passive"))
      (node (ref "U$1") (pin "AC2") (pinfunction "1_AC2") (pintype "bidirectional"))
      (node (ref "U$1") (pin "AT1") (pinfunction "1_AT1") (pintype "bidirectional"))
      (node (ref "U$1") (pin "BC2") (pinfunction "1_BC2") (pintype "bidirectional"))
      (node (ref "U$1") (pin "BT1") (pinfunction "1_BT1") (pintype "bidirectional"))
      (node (ref "U$1") (pin "CC2") (pinfunction "1_CC2") (pintype "bidirectional"))
      (node (ref "U$1") (pin "CT1") (pinfunction "1_CT1") (pintype "bidirectional"))
      (node (ref "U$1") (pin "DC2") (pinfunction "1_DC2") (pintype "bidirectional"))
      (node (ref "U$1") (pin "DT1") (pinfunction "1_DT1") (pintype "bidirectional"))
      (node (ref "U$2") (pin "C1") (pinfunction "P$1_C1") (pintype "passive"))
      (node (ref "U$2") (pin "T2") (pinfunction "P$1_T2") (pintype "passive"))
      (node (ref "U$3") (pin "C1") (pinfunction "P$1_C1") (pintype "passive"))
      (node (ref "U$3") (pin "T2") (pinfunction "P$1_T2") (pintype "passive"))
      (node (ref "U$4") (pin "C1") (pinfunction "P$1_C1") (pintype "passive"))
      (node (ref "U$4") (pin "T2") (pinfunction "P$1_T2") (pintype "passive"))
      (node (ref "U$5") (pin "C1") (pinfunction "P$1_C1") (pintype "passive"))
      (node (ref "U$5") (pin "T2") (pinfunction "P$1_T2") (pintype "passive"))
    )
    (net (code "2") (name "Net-(IC1-Pad1)") (class "Default")
      (node (ref "IC1") (pin "1") (pinfunction "1_1") (pintype "passive"))
      (node (ref "SV1") (pin "2") (pinfunction "2_2") (pintype "passive"))
    )
    (net (code "3") (name "Net-(IC1-Pad2)") (class "Default")
      (node (ref "IC1") (pin "2") (pinfunction "2_2") (pintype "passive"))
      (node (ref "SV1") (pin "3") (pinfunction "3_3") (pintype "passive"))
    )
    (net (code "4") (name "Net-(IC1-Pad3)") (class "Default")
      (node (ref "IC1") (pin "3") (pinfunction "3_3") (pintype "passive"))
      (node (ref "SV1") (pin "4") (pinfunction "4_4") (pintype "passive"))
    )
    (net (code "5") (name "Net-(IC1-Pad4)") (class "Default")
      (node (ref "IC1") (pin "4") (pinfunction "4_4") (pintype "passive"))
      (node (ref "SV1") (pin "5") (pinfunction "5_5") (pintype "passive"))
    )
    (net (code "6") (name "Net-(IC1-Pad5)") (class "Default")
      (node (ref "IC1") (pin "5") (pinfunction "5_5") (pintype "passive"))
      (node (ref "SV1") (pin "6") (pinfunction "6_6") (pintype "passive"))
    )
    (net (code "7") (name "Net-(IC1-Pad6)") (class "Default")
      (node (ref "IC1") (pin "6") (pinfunction "6_6") (pintype "passive"))
      (node (ref "SV1") (pin "7") (pinfunction "7_7") (pintype "passive"))
    )
    (net (code "8") (name "Net-(IC1-Pad7)") (class "Default")
      (node (ref "IC1") (pin "7") (pinfunction "7_7") (pintype "passive"))
      (node (ref "SV1") (pin "8") (pinfunction "8_8") (pintype "passive"))
    )
    (net (code "9") (name "Net-(IC1-Pad8)") (class "Default")
      (node (ref "IC1") (pin "8") (pinfunction "8_8") (pintype "passive"))
      (node (ref "SV1") (pin "9") (pinfunction "9_9") (pintype "passive"))
    )
    (net (code "10") (name "Net-(IC1-Pad9)") (class "Default")
      (node (ref "IC1") (pin "9") (pinfunction "9_9") (pintype "passive"))
      (node (ref "SV2") (pin "1") (pinfunction "1_1") (pintype "passive"))
    )
    (net (code "11") (name "Net-(IC1-Pad10)") (class "Default")
      (node (ref "IC1") (pin "10") (pinfunction "10_10") (pintype "passive"))
      (node (ref "SV2") (pin "2") (pinfunction "2_2") (pintype "passive"))
    )
    (net (code "12") (name "Net-(IC1-Pad11)") (class "Default")
      (node (ref "IC1") (pin "11") (pinfunction "11_11") (pintype "passive"))
      (node (ref "SV2") (pin "3") (pinfunction "3_3") (pintype "passive"))
    )
    (net (code "13") (name "Net-(IC1-Pad12)") (class "Default")
      (node (ref "IC1") (pin "12") (pinfunction "12_12") (pintype "passive"))
      (node (ref "SV2") (pin "4") (pinfunction "4_4") (pintype "passive"))
    )
    (net (code "14") (name "Net-(IC1-Pad13)") (class "Default")
      (node (ref "IC1") (pin "13") (pinfunction "13_13") (pintype "passive"))
      (node (ref "SV2") (pin "5") (pinfunction "5_5") (pintype "passive"))
    )
    (net (code "15") (name "Net-(IC1-Pad14)") (class "Default")
      (node (ref "IC1") (pin "14") (pinfunction "14_14") (pintype "passive"))
      (node (ref "SV2") (pin "6") (pinfunction "6_6") (pintype "passive"))
    )
    (net (code "16") (name "Net-(IC1-Pad15)") (class "Default")
      (node (ref "IC1") (pin "15") (pinfunction "15_15") (pintype "passive"))
      (node (ref "SV2") (pin "7") (pinfunction "7_7") (pintype "passive"))
    )
    (net (code "17") (name "Net-(IC1-Pad16)") (class "Default")
      (node (ref "IC1") (pin "16") (pinfunction "16_16") (pintype "passive"))
      (node (ref "SV2") (pin "8") (pinfunction "8_8") (pintype "passive"))
    )
    (net (code "18") (name "Net-(IC2-Pad1)") (class "Default")
      (node (ref "IC2") (pin "1") (pinfunction "1_1") (pintype "passive"))
      (node (ref "SV3") (pin "2") (pinfunction "2_2") (pintype "passive"))
    )
    (net (code "19") (name "Net-(IC2-Pad2)") (class "Default")
      (node (ref "IC2") (pin "2") (pinfunction "2_2") (pintype "passive"))
      (node (ref "SV3") (pin "3") (pinfunction "3_3") (pintype "passive"))
    )
    (net (code "20") (name "Net-(IC2-Pad3)") (class "Default")
      (node (ref "IC2") (pin "3") (pinfunction "3_3") (pintype "passive"))
      (node (ref "SV3") (pin "4") (pinfunction "4_4") (pintype "passive"))
    )
    (net (code "21") (name "Net-(IC2-Pad4)") (class "Default")
      (node (ref "IC2") (pin "4") (pinfunction "4_4") (pintype "passive"))
      (node (ref "SV3") (pin "5") (pinfunction "5_5") (pintype "passive"))
    )
    (net (code "22") (name "Net-(IC2-Pad5)") (class "Default")
      (node (ref "IC2") (pin "5") (pinfunction "5_5") (pintype "passive"))
      (node (ref "SV3") (pin "6") (pinfunction "6_6") (pintype "passive"))
    )
    (net (code "23") (name "Net-(IC2-Pad6)") (class "Default")
      (node (ref "IC2") (pin "6") (pinfunction "6_6") (pintype "passive"))
      (node (ref "SV3") (pin "7") (pinfunction "7_7") (pintype "passive"))
    )
    (net (code "24") (name "Net-(IC2-Pad7)") (class "Default")
      (node (ref "IC2") (pin "7") (pinfunction "7_7") (pintype "passive"))
      (node (ref "SV3") (pin "8") (pinfunction "8_8") (pintype "passive"))
    )
    (net (code "25") (name "Net-(IC2-Pad8)") (class "Default")
      (node (ref "IC2") (pin "8") (pinfunction "8_8") (pintype "passive"))
      (node (ref "SV3") (pin "9") (pinfunction "9_9") (pintype "passive"))
    )
    (net (code "26") (name "Net-(IC2-Pad9)") (class "Default")
      (node (ref "IC2") (pin "9") (pinfunction "9_9") (pintype "passive"))
      (node (ref "SV4") (pin "1") (pinfunction "1_1") (pintype "passive"))
    )
    (net (code "27") (name "Net-(IC2-Pad10)") (class "Default")
      (node (ref "IC2") (pin "10") (pinfunction "10_10") (pintype "passive"))
      (node (ref "SV4") (pin "2") (pinfunction "2_2") (pintype "passive"))
    )
    (net (code "28") (name "Net-(IC2-Pad11)") (class "Default")
      (node (ref "IC2") (pin "11") (pinfunction "11_11") (pintype "passive"))
      (node (ref "SV4") (pin "3") (pinfunction "3_3") (pintype "passive"))
    )
    (net (code "29") (name "Net-(IC2-Pad12)") (class "Default")
      (node (ref "IC2") (pin "12") (pinfunction "12_12") (pintype "passive"))
      (node (ref "SV4") (pin "4") (pinfunction "4_4") (pintype "passive"))
    )
    (net (code "30") (name "Net-(IC2-Pad13)") (class "Default")
      (node (ref "IC2") (pin "13") (pinfunction "13_13") (pintype "passive"))
      (node (ref "SV4") (pin "5") (pinfunction "5_5") (pintype "passive"))
    )
    (net (code "31") (name "Net-(IC2-Pad14)") (class "Default")
      (node (ref "IC2") (pin "14") (pinfunction "14_14") (pintype "passive"))
      (node (ref "SV4") (pin "6") (pinfunction "6_6") (pintype "passive"))
    )
    (net (code "32") (name "Net-(IC2-Pad15)") (class "Default")
      (node (ref "IC2") (pin "15") (pinfunction "15_15") (pintype "passive"))
      (node (ref "SV4") (pin "7") (pinfunction "7_7") (pintype "passive"))
    )
    (net (code "33") (name "Net-(IC2-Pad16)") (class "Default")
      (node (ref "IC2") (pin "16") (pinfunction "16_16") (pintype "passive"))
      (node (ref "SV4") (pin "8") (pinfunction "8_8") (pintype "passive"))
    )
    (net (code "34") (name "Net-(IC3-Pad1)") (class "Default")
      (node (ref "IC3") (pin "1") (pinfunction "1_1") (pintype "passive"))
      (node (ref "SV5") (pin "2") (pinfunction "2_2") (pintype "passive"))
    )
    (net (code "35") (name "Net-(IC3-Pad2)") (class "Default")
      (node (ref "IC3") (pin "2") (pinfunction "2_2") (pintype "passive"))
      (node (ref "SV5") (pin "3") (pinfunction "3_3") (pintype "passive"))
    )
    (net (code "36") (name "Net-(IC3-Pad3)") (class "Default")
      (node (ref "IC3") (pin "3") (pinfunction "3_3") (pintype "passive"))
      (node (ref "SV5") (pin "4") (pinfunction "4_4") (pintype "passive"))
    )
    (net (code "37") (name "Net-(IC3-Pad4)") (class "Default")
      (node (ref "IC3") (pin "4") (pinfunction "4_4") (pintype "passive"))
      (node (ref "SV5") (pin "5") (pinfunction "5_5") (pintype "passive"))
    )
    (net (code "38") (name "Net-(IC3-Pad5)") (class "Default")
      (node (ref "IC3") (pin "5") (pinfunction "5_5") (pintype "passive"))
      (node (ref "SV5") (pin "6") (pinfunction "6_6") (pintype "passive"))
    )
    (net (code "39") (name "Net-(IC3-Pad6)") (class "Default")
      (node (ref "IC3") (pin "6") (pinfunction "6_6") (pintype "passive"))
      (node (ref "SV5") (pin "7") (pinfunction "7_7") (pintype "passive"))
    )
    (net (code "40") (name "Net-(IC3-Pad7)") (class "Default")
      (node (ref "IC3") (pin "7") (pinfunction "7_7") (pintype "passive"))
      (node (ref "SV5") (pin "8") (pinfunction "8_8") (pintype "passive"))
    )
    (net (code "41") (name "Net-(IC3-Pad8)") (class "Default")
      (node (ref "IC3") (pin "8") (pinfunction "8_8") (pintype "passive"))
      (node (ref "SV5") (pin "9") (pinfunction "9_9") (pintype "passive"))
    )
    (net (code "42") (name "Net-(IC3-Pad9)") (class "Default")
      (node (ref "IC3") (pin "9") (pinfunction "9_9") (pintype "passive"))
      (node (ref "SV6") (pin "1") (pinfunction "1_1") (pintype "passive"))
    )
    (net (code "43") (name "Net-(IC3-Pad10)") (class "Default")
      (node (ref "IC3") (pin "10") (pinfunction "10_10") (pintype "passive"))
      (node (ref "SV6") (pin "2") (pinfunction "2_2") (pintype "passive"))
    )
    (net (code "44") (name "Net-(IC3-Pad11)") (class "Default")
      (node (ref "IC3") (pin "11") (pinfunction "11_11") (pintype "passive"))
      (node (ref "SV6") (pin "3") (pinfunction "3_3") (pintype "passive"))
    )
    (net (code "45") (name "Net-(IC3-Pad12)") (class "Default")
      (node (ref "IC3") (pin "12") (pinfunction "12_12") (pintype "passive"))
      (node (ref "SV6") (pin "4") (pinfunction "4_4") (pintype "passive"))
    )
    (net (code "46") (name "Net-(IC3-Pad13)") (class "Default")
      (node (ref "IC3") (pin "13") (pinfunction "13_13") (pintype "passive"))
      (node (ref "SV6") (pin "5") (pinfunction "5_5") (pintype "passive"))
    )
    (net (code "47") (name "Net-(IC3-Pad14)") (class "Default")
      (node (ref "IC3") (pin "14") (pinfunction "14_14") (pintype "passive"))
      (node (ref "SV6") (pin "6") (pinfunction "6_6") (pintype "passive"))
    )
    (net (code "48") (name "Net-(IC3-Pad15)") (class "Default")
      (node (ref "IC3") (pin "15") (pinfunction "15_15") (pintype "passive"))
      (node (ref "SV6") (pin "7") (pinfunction "7_7") (pintype "passive"))
    )
    (net (code "49") (name "Net-(IC3-Pad16)") (class "Default")
      (node (ref "IC3") (pin "16") (pinfunction "16_16") (pintype "passive"))
      (node (ref "SV6") (pin "8") (pinfunction "8_8") (pintype "passive"))
    )
    (net (code "50") (name "Net-(IC4-Pad1)") (class "Default")
      (node (ref "IC4") (pin "1") (pinfunction "1_1") (pintype "passive"))
      (node (ref "SV7") (pin "2") (pinfunction "2_2") (pintype "passive"))
    )
    (net (code "51") (name "Net-(IC4-Pad2)") (class "Default")
      (node (ref "IC4") (pin "2") (pinfunction "2_2") (pintype "passive"))
      (node (ref "SV7") (pin "3") (pinfunction "3_3") (pintype "passive"))
    )
    (net (code "52") (name "Net-(IC4-Pad3)") (class "Default")
      (node (ref "IC4") (pin "3") (pinfunction "3_3") (pintype "passive"))
      (node (ref "SV7") (pin "4") (pinfunction "4_4") (pintype "passive"))
    )
    (net (code "53") (name "Net-(IC4-Pad4)") (class "Default")
      (node (ref "IC4") (pin "4") (pinfunction "4_4") (pintype "passive"))
      (node (ref "SV7") (pin "5") (pinfunction "5_5") (pintype "passive"))
    )
    (net (code "54") (name "Net-(IC4-Pad5)") (class "Default")
      (node (ref "IC4") (pin "5") (pinfunction "5_5") (pintype "passive"))
      (node (ref "SV7") (pin "6") (pinfunction "6_6") (pintype "passive"))
    )
    (net (code "55") (name "Net-(IC4-Pad6)") (class "Default")
      (node (ref "IC4") (pin "6") (pinfunction "6_6") (pintype "passive"))
      (node (ref "SV7") (pin "7") (pinfunction "7_7") (pintype "passive"))
    )
    (net (code "56") (name "Net-(IC4-Pad7)") (class "Default")
      (node (ref "IC4") (pin "7") (pinfunction "7_7") (pintype "passive"))
      (node (ref "SV7") (pin "8") (pinfunction "8_8") (pintype "passive"))
    )
    (net (code "57") (name "Net-(IC4-Pad8)") (class "Default")
      (node (ref "IC4") (pin "8") (pinfunction "8_8") (pintype "passive"))
      (node (ref "SV7") (pin "9") (pinfunction "9_9") (pintype "passive"))
    )
    (net (code "58") (name "Net-(IC4-Pad9)") (class "Default")
      (node (ref "IC4") (pin "9") (pinfunction "9_9") (pintype "passive"))
      (node (ref "SV8") (pin "1") (pinfunction "1_1") (pintype "passive"))
    )
    (net (code "59") (name "Net-(IC4-Pad10)") (class "Default")
      (node (ref "IC4") (pin "10") (pinfunction "10_10") (pintype "passive"))
      (node (ref "SV8") (pin "2") (pinfunction "2_2") (pintype "passive"))
    )
    (net (code "60") (name "Net-(IC4-Pad11)") (class "Default")
      (node (ref "IC4") (pin "11") (pinfunction "11_11") (pintype "passive"))
      (node (ref "SV8") (pin "3") (pinfunction "3_3") (pintype "passive"))
    )
    (net (code "61") (name "Net-(IC4-Pad12)") (class "Default")
      (node (ref "IC4") (pin "12") (pinfunction "12_12") (pintype "passive"))
      (node (ref "SV8") (pin "4") (pinfunction "4_4") (pintype "passive"))
    )
    (net (code "62") (name "Net-(IC4-Pad13)") (class "Default")
      (node (ref "IC4") (pin "13") (pinfunction "13_13") (pintype "passive"))
      (node (ref "SV8") (pin "5") (pinfunction "5_5") (pintype "passive"))
    )
    (net (code "63") (name "Net-(IC4-Pad14)") (class "Default")
      (node (ref "IC4") (pin "14") (pinfunction "14_14") (pintype "passive"))
      (node (ref "SV8") (pin "6") (pinfunction "6_6") (pintype "passive"))
    )
    (net (code "64") (name "Net-(IC4-Pad15)") (class "Default")
      (node (ref "IC4") (pin "15") (pinfunction "15_15") (pintype "passive"))
      (node (ref "SV8") (pin "7") (pinfunction "7_7") (pintype "passive"))
    )
    (net (code "65") (name "Net-(IC4-Pad16)") (class "Default")
      (node (ref "IC4") (pin "16") (pinfunction "16_16") (pintype "passive"))
      (node (ref "SV8") (pin "8") (pinfunction "8_8") (pintype "passive"))
    )
    (net (code "66") (name "Net-(IC5-Pad1)") (class "Default")
      (node (ref "IC5") (pin "1") (pinfunction "1_1") (pintype "passive"))
      (node (ref "SV9") (pin "2") (pinfunction "2_2") (pintype "passive"))
    )
    (net (code "67") (name "Net-(IC5-Pad2)") (class "Default")
      (node (ref "IC5") (pin "2") (pinfunction "2_2") (pintype "passive"))
      (node (ref "SV9") (pin "3") (pinfunction "3_3") (pintype "passive"))
    )
    (net (code "68") (name "Net-(IC5-Pad3)") (class "Default")
      (node (ref "IC5") (pin "3") (pinfunction "3_3") (pintype "passive"))
      (node (ref "SV9") (pin "4") (pinfunction "4_4") (pintype "passive"))
    )
    (net (code "69") (name "Net-(IC5-Pad4)") (class "Default")
      (node (ref "IC5") (pin "4") (pinfunction "4_4") (pintype "passive"))
      (node (ref "SV9") (pin "5") (pinfunction "5_5") (pintype "passive"))
    )
    (net (code "70") (name "Net-(IC5-Pad5)") (class "Default")
      (node (ref "IC5") (pin "5") (pinfunction "5_5") (pintype "passive"))
      (node (ref "SV9") (pin "6") (pinfunction "6_6") (pintype "passive"))
    )
    (net (code "71") (name "Net-(IC5-Pad6)") (class "Default")
      (node (ref "IC5") (pin "6") (pinfunction "6_6") (pintype "passive"))
      (node (ref "SV9") (pin "7") (pinfunction "7_7") (pintype "passive"))
    )
    (net (code "72") (name "Net-(IC5-Pad7)") (class "Default")
      (node (ref "IC5") (pin "7") (pinfunction "7_7") (pintype "passive"))
      (node (ref "SV9") (pin "8") (pinfunction "8_8") (pintype "passive"))
    )
    (net (code "73") (name "Net-(IC5-Pad8)") (class "Default")
      (node (ref "IC5") (pin "8") (pinfunction "8_8") (pintype "passive"))
      (node (ref "SV9") (pin "9") (pinfunction "9_9") (pintype "passive"))
    )
    (net (code "74") (name "Net-(IC5-Pad9)") (class "Default")
      (node (ref "IC5") (pin "9") (pinfunction "9_9") (pintype "passive"))
      (node (ref "SV10") (pin "1") (pinfunction "1_1") (pintype "passive"))
    )
    (net (code "75") (name "Net-(IC5-Pad10)") (class "Default")
      (node (ref "IC5") (pin "10") (pinfunction "10_10") (pintype "passive"))
      (node (ref "SV10") (pin "2") (pinfunction "2_2") (pintype "passive"))
    )
    (net (code "76") (name "Net-(IC5-Pad11)") (class "Default")
      (node (ref "IC5") (pin "11") (pinfunction "11_11") (pintype "passive"))
      (node (ref "SV10") (pin "3") (pinfunction "3_3") (pintype "passive"))
    )
    (net (code "77") (name "Net-(IC5-Pad12)") (class "Default")
      (node (ref "IC5") (pin "12") (pinfunction "12_12") (pintype "passive"))
      (node (ref "SV10") (pin "4") (pinfunction "4_4") (pintype "passive"))
    )
    (net (code "78") (name "Net-(IC5-Pad13)") (class "Default")
      (node (ref "IC5") (pin "13") (pinfunction "13_13") (pintype "passive"))
      (node (ref "SV10") (pin "5") (pinfunction "5_5") (pintype "passive"))
    )
    (net (code "79") (name "Net-(IC5-Pad14)") (class "Default")
      (node (ref "IC5") (pin "14") (pinfunction "14_14") (pintype "passive"))
      (node (ref "SV10") (pin "6") (pinfunction "6_6") (pintype "passive"))
    )
    (net (code "80") (name "Net-(IC5-Pad15)") (class "Default")
      (node (ref "IC5") (pin "15") (pinfunction "15_15") (pintype "passive"))
      (node (ref "SV10") (pin "7") (pinfunction "7_7") (pintype "passive"))
    )
    (net (code "81") (name "Net-(IC5-Pad16)") (class "Default")
      (node (ref "IC5") (pin "16") (pinfunction "16_16") (pintype "passive"))
      (node (ref "SV10") (pin "8") (pinfunction "8_8") (pintype "passive"))
    )
    (net (code "82") (name "Net-(IC6-Pad1)") (class "Default")
      (node (ref "IC6") (pin "1") (pinfunction "1_1") (pintype "passive"))
      (node (ref "SV11") (pin "2") (pinfunction "2_2") (pintype "passive"))
    )
    (net (code "83") (name "Net-(IC6-Pad2)") (class "Default")
      (node (ref "IC6") (pin "2") (pinfunction "2_2") (pintype "passive"))
      (node (ref "SV11") (pin "3") (pinfunction "3_3") (pintype "passive"))
    )
    (net (code "84") (name "Net-(IC6-Pad3)") (class "Default")
      (node (ref "IC6") (pin "3") (pinfunction "3_3") (pintype "passive"))
      (node (ref "SV11") (pin "4") (pinfunction "4_4") (pintype "passive"))
    )
    (net (code "85") (name "Net-(IC6-Pad4)") (class "Default")
      (node (ref "IC6") (pin "4") (pinfunction "4_4") (pintype "passive"))
      (node (ref "SV11") (pin "5") (pinfunction "5_5") (pintype "passive"))
    )
    (net (code "86") (name "Net-(IC6-Pad5)") (class "Default")
      (node (ref "IC6") (pin "5") (pinfunction "5_5") (pintype "passive"))
      (node (ref "SV11") (pin "6") (pinfunction "6_6") (pintype "passive"))
    )
    (net (code "87") (name "Net-(IC6-Pad6)") (class "Default")
      (node (ref "IC6") (pin "6") (pinfunction "6_6") (pintype "passive"))
      (node (ref "SV11") (pin "7") (pinfunction "7_7") (pintype "passive"))
    )
    (net (code "88") (name "Net-(IC6-Pad7)") (class "Default")
      (node (ref "IC6") (pin "7") (pinfunction "7_7") (pintype "passive"))
      (node (ref "SV11") (pin "8") (pinfunction "8_8") (pintype "passive"))
    )
    (net (code "89") (name "Net-(IC6-Pad8)") (class "Default")
      (node (ref "IC6") (pin "8") (pinfunction "8_8") (pintype "passive"))
      (node (ref "SV11") (pin "9") (pinfunction "9_9") (pintype "passive"))
    )
    (net (code "90") (name "Net-(IC6-Pad9)") (class "Default")
      (node (ref "IC6") (pin "9") (pinfunction "9_9") (pintype "passive"))
      (node (ref "SV12") (pin "1") (pinfunction "1_1") (pintype "passive"))
    )
    (net (code "91") (name "Net-(IC6-Pad10)") (class "Default")
      (node (ref "IC6") (pin "10") (pinfunction "10_10") (pintype "passive"))
      (node (ref "SV12") (pin "2") (pinfunction "2_2") (pintype "passive"))
    )
    (net (code "92") (name "Net-(IC6-Pad11)") (class "Default")
      (node (ref "IC6") (pin "11") (pinfunction "11_11") (pintype "passive"))
      (node (ref "SV12") (pin "3") (pinfunction "3_3") (pintype "passive"))
    )
    (net (code "93") (name "Net-(IC6-Pad12)") (class "Default")
      (node (ref "IC6") (pin "12") (pinfunction "12_12") (pintype "passive"))
      (node (ref "SV12") (pin "4") (pinfunction "4_4") (pintype "passive"))
    )
    (net (code "94") (name "Net-(IC6-Pad13)") (class "Default")
      (node (ref "IC6") (pin "13") (pinfunction "13_13") (pintype "passive"))
      (node (ref "SV12") (pin "5") (pinfunction "5_5") (pintype "passive"))
    )
    (net (code "95") (name "Net-(IC6-Pad14)") (class "Default")
      (node (ref "IC6") (pin "14") (pinfunction "14_14") (pintype "passive"))
      (node (ref "SV12") (pin "6") (pinfunction "6_6") (pintype "passive"))
    )
    (net (code "96") (name "Net-(IC6-Pad15)") (class "Default")
      (node (ref "IC6") (pin "15") (pinfunction "15_15") (pintype "passive"))
      (node (ref "SV12") (pin "7") (pinfunction "7_7") (pintype "passive"))
    )
    (net (code "97") (name "Net-(IC6-Pad16)") (class "Default")
      (node (ref "IC6") (pin "16") (pinfunction "16_16") (pintype "passive"))
      (node (ref "SV12") (pin "8") (pinfunction "8_8") (pintype "passive"))
    )
    (net (code "98") (name "Net-(IC7-Pad1)") (class "Default")
      (node (ref "IC7") (pin "1") (pinfunction "1_1") (pintype "passive"))
      (node (ref "SV13") (pin "2") (pinfunction "2_2") (pintype "passive"))
    )
    (net (code "99") (name "Net-(IC7-Pad2)") (class "Default")
      (node (ref "IC7") (pin "2") (pinfunction "2_2") (pintype "passive"))
      (node (ref "SV13") (pin "3") (pinfunction "3_3") (pintype "passive"))
    )
    (net (code "100") (name "Net-(IC7-Pad3)") (class "Default")
      (node (ref "IC7") (pin "3") (pinfunction "3_3") (pintype "passive"))
      (node (ref "SV13") (pin "4") (pinfunction "4_4") (pintype "passive"))
    )
    (net (code "101") (name "Net-(IC7-Pad4)") (class "Default")
      (node (ref "IC7") (pin "4") (pinfunction "4_4") (pintype "passive"))
      (node (ref "SV13") (pin "5") (pinfunction "5_5") (pintype "passive"))
    )
    (net (code "102") (name "Net-(IC7-Pad5)") (class "Default")
      (node (ref "IC7") (pin "5") (pinfunction "5_5") (pintype "passive"))
      (node (ref "SV13") (pin "6") (pinfunction "6_6") (pintype "passive"))
    )
    (net (code "103") (name "Net-(IC7-Pad6)") (class "Default")
      (node (ref "IC7") (pin "6") (pinfunction "6_6") (pintype "passive"))
      (node (ref "SV13") (pin "7") (pinfunction "7_7") (pintype "passive"))
    )
    (net (code "104") (name "Net-(IC7-Pad7)") (class "Default")
      (node (ref "IC7") (pin "7") (pinfunction "7_7") (pintype "passive"))
      (node (ref "SV13") (pin "8") (pinfunction "8_8") (pintype "passive"))
    )
    (net (code "105") (name "Net-(IC7-Pad8)") (class "Default")
      (node (ref "IC7") (pin "8") (pinfunction "8_8") (pintype "passive"))
      (node (ref "SV13") (pin "9") (pinfunction "9_9") (pintype "passive"))
    )
    (net (code "106") (name "Net-(IC7-Pad9)") (class "Default")
      (node (ref "IC7") (pin "9") (pinfunction "9_9") (pintype "passive"))
      (node (ref "SV14") (pin "1") (pinfunction "1_1") (pintype "passive"))
    )
    (net (code "107") (name "Net-(IC7-Pad10)") (class "Default")
      (node (ref "IC7") (pin "10") (pinfunction "10_10") (pintype "passive"))
      (node (ref "SV14") (pin "2") (pinfunction "2_2") (pintype "passive"))
    )
    (net (code "108") (name "Net-(IC7-Pad11)") (class "Default")
      (node (ref "IC7") (pin "11") (pinfunction "11_11") (pintype "passive"))
      (node (ref "SV14") (pin "3") (pinfunction "3_3") (pintype "passive"))
    )
    (net (code "109") (name "Net-(IC7-Pad12)") (class "Default")
      (node (ref "IC7") (pin "12") (pinfunction "12_12") (pintype "passive"))
      (node (ref "SV14") (pin "4") (pinfunction "4_4") (pintype "passive"))
    )
    (net (code "110") (name "Net-(IC7-Pad13)") (class "Default")
      (node (ref "IC7") (pin "13") (pinfunction "13_13") (pintype "passive"))
      (node (ref "SV14") (pin "5") (pinfunction "5_5") (pintype "passive"))
    )
    (net (code "111") (name "Net-(IC7-Pad14)") (class "Default")
      (node (ref "IC7") (pin "14") (pinfunction "14_14") (pintype "passive"))
      (node (ref "SV14") (pin "6") (pinfunction "6_6") (pintype "passive"))
    )
    (net (code "112") (name "Net-(IC7-Pad15)") (class "Default")
      (node (ref "IC7") (pin "15") (pinfunction "15_15") (pintype "passive"))
      (node (ref "SV14") (pin "7") (pinfunction "7_7") (pintype "passive"))
    )
    (net (code "113") (name "Net-(IC7-Pad16)") (class "Default")
      (node (ref "IC7") (pin "16") (pinfunction "16_16") (pintype "passive"))
      (node (ref "SV14") (pin "8") (pinfunction "8_8") (pintype "passive"))
    )
    (net (code "114") (name "Net-(IC8-Pad1)") (class "Default")
      (node (ref "IC8") (pin "1") (pinfunction "1_1") (pintype "passive"))
      (node (ref "SV15") (pin "2") (pinfunction "2_2") (pintype "passive"))
    )
    (net (code "115") (name "Net-(IC8-Pad2)") (class "Default")
      (node (ref "IC8") (pin "2") (pinfunction "2_2") (pintype "passive"))
      (node (ref "SV15") (pin "3") (pinfunction "3_3") (pintype "passive"))
    )
    (net (code "116") (name "Net-(IC8-Pad3)") (class "Default")
      (node (ref "IC8") (pin "3") (pinfunction "3_3") (pintype "passive"))
      (node (ref "SV15") (pin "4") (pinfunction "4_4") (pintype "passive"))
    )
    (net (code "117") (name "Net-(IC8-Pad4)") (class "Default")
      (node (ref "IC8") (pin "4") (pinfunction "4_4") (pintype "passive"))
      (node (ref "SV15") (pin "5") (pinfunction "5_5") (pintype "passive"))
    )
    (net (code "118") (name "Net-(IC8-Pad5)") (class "Default")
      (node (ref "IC8") (pin "5") (pinfunction "5_5") (pintype "passive"))
      (node (ref "SV15") (pin "6") (pinfunction "6_6") (pintype "passive"))
    )
    (net (code "119") (name "Net-(IC8-Pad6)") (class "Default")
      (node (ref "IC8") (pin "6") (pinfunction "6_6") (pintype "passive"))
      (node (ref "SV15") (pin "7") (pinfunction "7_7") (pintype "passive"))
    )
    (net (code "120") (name "Net-(IC8-Pad7)") (class "Default")
      (node (ref "IC8") (pin "7") (pinfunction "7_7") (pintype "passive"))
      (node (ref "SV15") (pin "8") (pinfunction "8_8") (pintype "passive"))
    )
    (net (code "121") (name "Net-(IC8-Pad8)") (class "Default")
      (node (ref "IC8") (pin "8") (pinfunction "8_8") (pintype "passive"))
      (node (ref "SV15") (pin "9") (pinfunction "9_9") (pintype "passive"))
    )
    (net (code "122") (name "Net-(IC8-Pad9)") (class "Default")
      (node (ref "IC8") (pin "9") (pinfunction "9_9") (pintype "passive"))
      (node (ref "SV16") (pin "1") (pinfunction "1_1") (pintype "passive"))
    )
    (net (code "123") (name "Net-(IC8-Pad10)") (class "Default")
      (node (ref "IC8") (pin "10") (pinfunction "10_10") (pintype "passive"))
      (node (ref "SV16") (pin "2") (pinfunction "2_2") (pintype "passive"))
    )
    (net (code "124") (name "Net-(IC8-Pad11)") (class "Default")
      (node (ref "IC8") (pin "11") (pinfunction "11_11") (pintype "passive"))
      (node (ref "SV16") (pin "3") (pinfunction "3_3") (pintype "passive"))
    )
    (net (code "125") (name "Net-(IC8-Pad12)") (class "Default")
      (node (ref "IC8") (pin "12") (pinfunction "12_12") (pintype "passive"))
      (node (ref "SV16") (pin "4") (pinfunction "4_4") (pintype "passive"))
    )
    (net (code "126") (name "Net-(IC8-Pad13)") (class "Default")
      (node (ref "IC8") (pin "13") (pinfunction "13_13") (pintype "passive"))
      (node (ref "SV16") (pin "5") (pinfunction "5_5") (pintype "passive"))
    )
    (net (code "127") (name "Net-(IC8-Pad14)") (class "Default")
      (node (ref "IC8") (pin "14") (pinfunction "14_14") (pintype "passive"))
      (node (ref "SV16") (pin "6") (pinfunction "6_6") (pintype "passive"))
    )
    (net (code "128") (name "Net-(IC8-Pad15)") (class "Default")
      (node (ref "IC8") (pin "15") (pinfunction "15_15") (pintype "passive"))
      (node (ref "SV16") (pin "7") (pinfunction "7_7") (pintype "passive"))
    )
    (net (code "129") (name "Net-(IC8-Pad16)") (class "Default")
      (node (ref "IC8") (pin "16") (pinfunction "16_16") (pintype "passive"))
      (node (ref "SV16") (pin "8") (pinfunction "8_8") (pintype "passive"))
    )
    (net (code "130") (name "Net-(IC9-Pad1)") (class "Default")
      (node (ref "IC9") (pin "1") (pinfunction "1_1") (pintype "passive"))
      (node (ref "SV17") (pin "2") (pinfunction "2_2") (pintype "passive"))
    )
    (net (code "131") (name "Net-(IC9-Pad2)") (class "Default")
      (node (ref "IC9") (pin "2") (pinfunction "2_2") (pintype "passive"))
      (node (ref "SV17") (pin "3") (pinfunction "3_3") (pintype "passive"))
    )
    (net (code "132") (name "Net-(IC9-Pad3)") (class "Default")
      (node (ref "IC9") (pin "3") (pinfunction "3_3") (pintype "passive"))
      (node (ref "SV17") (pin "4") (pinfunction "4_4") (pintype "passive"))
    )
    (net (code "133") (name "Net-(IC9-Pad4)") (class "Default")
      (node (ref "IC9") (pin "4") (pinfunction "4_4") (pintype "passive"))
      (node (ref "SV17") (pin "5") (pinfunction "5_5") (pintype "passive"))
    )
    (net (code "134") (name "Net-(IC9-Pad5)") (class "Default")
      (node (ref "IC9") (pin "5") (pinfunction "5_5") (pintype "passive"))
      (node (ref "SV17") (pin "6") (pinfunction "6_6") (pintype "passive"))
    )
    (net (code "135") (name "Net-(IC9-Pad6)") (class "Default")
      (node (ref "IC9") (pin "6") (pinfunction "6_6") (pintype "passive"))
      (node (ref "SV17") (pin "7") (pinfunction "7_7") (pintype "passive"))
    )
    (net (code "136") (name "Net-(IC9-Pad7)") (class "Default")
      (node (ref "IC9") (pin "7") (pinfunction "7_7") (pintype "passive"))
      (node (ref "SV17") (pin "8") (pinfunction "8_8") (pintype "passive"))
    )
    (net (code "137") (name "Net-(IC9-Pad8)") (class "Default")
      (node (ref "IC9") (pin "8") (pinfunction "8_8") (pintype "passive"))
      (node (ref "SV17") (pin "9") (pinfunction "9_9") (pintype "passive"))
    )
    (net (code "138") (name "Net-(IC9-Pad9)") (class "Default")
      (node (ref "IC9") (pin "9") (pinfunction "9_9") (pintype "passive"))
      (node (ref "SV18") (pin "1") (pinfunction "1_1") (pintype "passive"))
    )
    (net (code "139") (name "Net-(IC9-Pad10)") (class "Default")
      (node (ref "IC9") (pin "10") (pinfunction "10_10") (pintype "passive"))
      (node (ref "SV18") (pin "2") (pinfunction "2_2") (pintype "passive"))
    )
    (net (code "140") (name "Net-(IC9-Pad11)") (class "Default")
      (node (ref "IC9") (pin "11") (pinfunction "11_11") (pintype "passive"))
      (node (ref "SV18") (pin "3") (pinfunction "3_3") (pintype "passive"))
    )
    (net (code "141") (name "Net-(IC9-Pad12)") (class "Default")
      (node (ref "IC9") (pin "12") (pinfunction "12_12") (pintype "passive"))
      (node (ref "SV18") (pin "4") (pinfunction "4_4") (pintype "passive"))
    )
    (net (code "142") (name "Net-(IC9-Pad13)") (class "Default")
      (node (ref "IC9") (pin "13") (pinfunction "13_13") (pintype "passive"))
      (node (ref "SV18") (pin "5") (pinfunction "5_5") (pintype "passive"))
    )
    (net (code "143") (name "Net-(IC9-Pad14)") (class "Default")
      (node (ref "IC9") (pin "14") (pinfunction "14_14") (pintype "passive"))
      (node (ref "SV18") (pin "6") (pinfunction "6_6") (pintype "passive"))
    )
    (net (code "144") (name "Net-(IC9-Pad15)") (class "Default")
      (node (ref "IC9") (pin "15") (pinfunction "15_15") (pintype "passive"))
      (node (ref "SV18") (pin "7") (pinfunction "7_7") (pintype "passive"))
    )
    (net (code "145") (name "Net-(IC9-Pad16)") (class "Default")
      (node (ref "IC9") (pin "16") (pinfunction "16_16") (pintype "passive"))
      (node (ref "SV18") (pin "8") (pinfunction "8_8") (pintype "passive"))
    )
    (net (code "146") (name "Net-(IC10-Pad1)") (class "Default")
      (node (ref "IC10") (pin "1") (pinfunction "1_1") (pintype "passive"))
      (node (ref "SV19") (pin "2") (pinfunction "2_2") (pintype "passive"))
    )
    (net (code "147") (name "Net-(IC10-Pad2)") (class "Default")
      (node (ref "IC10") (pin "2") (pinfunction "2_2") (pintype "passive"))
      (node (ref "SV19") (pin "3") (pinfunction "3_3") (pintype "passive"))
    )
    (net (code "148") (name "Net-(IC10-Pad3)") (class "Default")
      (node (ref "IC10") (pin "3") (pinfunction "3_3") (pintype "passive"))
      (node (ref "SV19") (pin "4") (pinfunction "4_4") (pintype "passive"))
    )
    (net (code "149") (name "Net-(IC10-Pad4)") (class "Default")
      (node (ref "IC10") (pin "4") (pinfunction "4_4") (pintype "passive"))
      (node (ref "SV19") (pin "5") (pinfunction "5_5") (pintype "passive"))
    )
    (net (code "150") (name "Net-(IC10-Pad5)") (class "Default")
      (node (ref "IC10") (pin "5") (pinfunction "5_5") (pintype "passive"))
      (node (ref "SV19") (pin "6") (pinfunction "6_6") (pintype "passive"))
    )
    (net (code "151") (name "Net-(IC10-Pad6)") (class "Default")
      (node (ref "IC10") (pin "6") (pinfunction "6_6") (pintype "passive"))
      (node (ref "SV19") (pin "7") (pinfunction "7_7") (pintype "passive"))
    )
    (net (code "152") (name "Net-(IC10-Pad7)") (class "Default")
      (node (ref "IC10") (pin "7") (pinfunction "7_7") (pintype "passive"))
      (node (ref "SV19") (pin "8") (pinfunction "8_8") (pintype "passive"))
    )
    (net (code "153") (name "Net-(IC10-Pad8)") (class "Default")
      (node (ref "IC10") (pin "8") (pinfunction "8_8") (pintype "passive"))
      (node (ref "SV19") (pin "9") (pinfunction "9_9") (pintype "passive"))
    )
    (net (code "154") (name "Net-(IC10-Pad9)") (class "Default")
      (node (ref "IC10") (pin "9") (pinfunction "9_9") (pintype "passive"))
      (node (ref "SV20") (pin "1") (pinfunction "1_1") (pintype "passive"))
    )
    (net (code "155") (name "Net-(IC10-Pad10)") (class "Default")
      (node (ref "IC10") (pin "10") (pinfunction "10_10") (pintype "passive"))
      (node (ref "SV20") (pin "2") (pinfunction "2_2") (pintype "passive"))
    )
    (net (code "156") (name "Net-(IC10-Pad11)") (class "Default")
      (node (ref "IC10") (pin "11") (pinfunction "11_11") (pintype "passive"))
      (node (ref "SV20") (pin "3") (pinfunction "3_3") (pintype "passive"))
    )
    (net (code "157") (name "Net-(IC10-Pad12)") (class "Default")
      (node (ref "IC10") (pin "12") (pinfunction "12_12") (pintype "passive"))
      (node (ref "SV20") (pin "4") (pinfunction "4_4") (pintype "passive"))
    )
    (net (code "158") (name "Net-(IC10-Pad13)") (class "Default")
      (node (ref "IC10") (pin "13") (pinfunction "13_13") (pintype "passive"))
      (node (ref "SV20") (pin "5") (pinfunction "5_5") (pintype "passive"))
    )
    (net (code "159") (name "Net-(IC10-Pad14)") (class "Default")
      (node (ref "IC10") (pin "14") (pinfunction "14_14") (pintype "passive"))
      (node (ref "SV20") (pin "6") (pinfunction "6_6") (pintype "passive"))
    )
    (net (code "160") (name "Net-(IC10-Pad15)") (class "Default")
      (node (ref "IC10") (pin "15") (pinfunction "15_15") (pintype "passive"))
      (node (ref "SV20") (pin "7") (pinfunction "7_7") (pintype "passive"))
    )
    (net (code "161") (name "Net-(IC10-Pad16)") (class "Default")
      (node (ref "IC10") (pin "16") (pinfunction "16_16") (pintype "passive"))
      (node (ref "SV20") (pin "8") (pinfunction "8_8") (pintype "passive"))
    )
    (net (code "162") (name "Net-(IC11-Pad1)") (class "Default")
      (node (ref "IC11") (pin "1") (pinfunction "1_1") (pintype "passive"))
      (node (ref "SV21") (pin "2") (pinfunction "2_2") (pintype "passive"))
    )
    (net (code "163") (name "Net-(IC11-Pad2)") (class "Default")
      (node (ref "IC11") (pin "2") (pinfunction "2_2") (pintype "passive"))
      (node (ref "SV21") (pin "3") (pinfunction "3_3") (pintype "passive"))
    )
    (net (code "164") (name "Net-(IC11-Pad3)") (class "Default")
      (node (ref "IC11") (pin "3") (pinfunction "3_3") (pintype "passive"))
      (node (ref "SV21") (pin "4") (pinfunction "4_4") (pintype "passive"))
    )
    (net (code "165") (name "Net-(IC11-Pad4)") (class "Default")
      (node (ref "IC11") (pin "4") (pinfunction "4_4") (pintype "passive"))
      (node (ref "SV21") (pin "5") (pinfunction "5_5") (pintype "passive"))
    )
    (net (code "166") (name "Net-(IC11-Pad5)") (class "Default")
      (node (ref "IC11") (pin "5") (pinfunction "5_5") (pintype "passive"))
      (node (ref "SV21") (pin "6") (pinfunction "6_6") (pintype "passive"))
    )
    (net (code "167") (name "Net-(IC11-Pad6)") (class "Default")
      (node (ref "IC11") (pin "6") (pinfunction "6_6") (pintype "passive"))
      (node (ref "SV21") (pin "7") (pinfunction "7_7") (pintype "passive"))
    )
    (net (code "168") (name "Net-(IC11-Pad7)") (class "Default")
      (node (ref "IC11") (pin "7") (pinfunction "7_7") (pintype "passive"))
      (node (ref "SV21") (pin "8") (pinfunction "8_8") (pintype "passive"))
    )
    (net (code "169") (name "Net-(IC11-Pad8)") (class "Default")
      (node (ref "IC11") (pin "8") (pinfunction "8_8") (pintype "passive"))
      (node (ref "SV21") (pin "9") (pinfunction "9_9") (pintype "passive"))
    )
    (net (code "170") (name "Net-(IC11-Pad9)") (class "Default")
      (node (ref "IC11") (pin "9") (pinfunction "9_9") (pintype "passive"))
      (node (ref "SV22") (pin "1") (pinfunction "1_1") (pintype "passive"))
    )
    (net (code "171") (name "Net-(IC11-Pad10)") (class "Default")
      (node (ref "IC11") (pin "10") (pinfunction "10_10") (pintype "passive"))
      (node (ref "SV22") (pin "2") (pinfunction "2_2") (pintype "passive"))
    )
    (net (code "172") (name "Net-(IC11-Pad11)") (class "Default")
      (node (ref "IC11") (pin "11") (pinfunction "11_11") (pintype "passive"))
      (node (ref "SV22") (pin "3") (pinfunction "3_3") (pintype "passive"))
    )
    (net (code "173") (name "Net-(IC11-Pad12)") (class "Default")
      (node (ref "IC11") (pin "12") (pinfunction "12_12") (pintype "passive"))
      (node (ref "SV22") (pin "4") (pinfunction "4_4") (pintype "passive"))
    )
    (net (code "174") (name "Net-(IC11-Pad13)") (class "Default")
      (node (ref "IC11") (pin "13") (pinfunction "13_13") (pintype "passive"))
      (node (ref "SV22") (pin "5") (pinfunction "5_5") (pintype "passive"))
    )
    (net (code "175") (name "Net-(IC11-Pad14)") (class "Default")
      (node (ref "IC11") (pin "14") (pinfunction "14_14") (pintype "passive"))
      (node (ref "SV22") (pin "6") (pinfunction "6_6") (pintype "passive"))
    )
    (net (code "176") (name "Net-(IC11-Pad15)") (class "Default")
      (node (ref "IC11") (pin "15") (pinfunction "15_15") (pintype "passive"))
      (node (ref "SV22") (pin "7") (pinfunction "7_7") (pintype "passive"))
    )
    (net (code "177") (name "Net-(IC11-Pad16)") (class "Default")
      (node (ref "IC11") (pin "16") (pinfunction "16_16") (pintype "passive"))
      (node (ref "SV22") (pin "8") (pinfunction "8_8") (pintype "passive"))
    )
    (net (code "178") (name "Net-(IC12-Pad1)") (class "Default")
      (node (ref "IC12") (pin "1") (pinfunction "1_1") (pintype "passive"))
      (node (ref "SV23") (pin "2") (pinfunction "2_2") (pintype "passive"))
    )
    (net (code "179") (name "Net-(IC12-Pad2)") (class "Default")
      (node (ref "IC12") (pin "2") (pinfunction "2_2") (pintype "passive"))
      (node (ref "SV23") (pin "3") (pinfunction "3_3") (pintype "passive"))
    )
    (net (code "180") (name "Net-(IC12-Pad3)") (class "Default")
      (node (ref "IC12") (pin "3") (pinfunction "3_3") (pintype "passive"))
      (node (ref "SV23") (pin "4") (pinfunction "4_4") (pintype "passive"))
    )
    (net (code "181") (name "Net-(IC12-Pad4)") (class "Default")
      (node (ref "IC12") (pin "4") (pinfunction "4_4") (pintype "passive"))
      (node (ref "SV23") (pin "5") (pinfunction "5_5") (pintype "passive"))
    )
    (net (code "182") (name "Net-(IC12-Pad5)") (class "Default")
      (node (ref "IC12") (pin "5") (pinfunction "5_5") (pintype "passive"))
      (node (ref "SV23") (pin "6") (pinfunction "6_6") (pintype "passive"))
    )
    (net (code "183") (name "Net-(IC12-Pad6)") (class "Default")
      (node (ref "IC12") (pin "6") (pinfunction "6_6") (pintype "passive"))
      (node (ref "SV23") (pin "7") (pinfunction "7_7") (pintype "passive"))
    )
    (net (code "184") (name "Net-(IC12-Pad7)") (class "Default")
      (node (ref "IC12") (pin "7") (pinfunction "7_7") (pintype "passive"))
      (node (ref "SV23") (pin "8") (pinfunction "8_8") (pintype "passive"))
    )
    (net (code "185") (name "Net-(IC12-Pad8)") (class "Default")
      (node (ref "IC12") (pin "8") (pinfunction "8_8") (pintype "passive"))
      (node (ref "SV23") (pin "9") (pinfunction "9_9") (pintype "passive"))
    )
    (net (code "186") (name "Net-(IC12-Pad9)") (class "Default")
      (node (ref "IC12") (pin "9") (pinfunction "9_9") (pintype "passive"))
      (node (ref "SV24") (pin "1") (pinfunction "1_1") (pintype "passive"))
    )
    (net (code "187") (name "Net-(IC12-Pad10)") (class "Default")
      (node (ref "IC12") (pin "10") (pinfunction "10_10") (pintype "passive"))
      (node (ref "SV24") (pin "2") (pinfunction "2_2") (pintype "passive"))
    )
    (net (code "188") (name "Net-(IC12-Pad11)") (class "Default")
      (node (ref "IC12") (pin "11") (pinfunction "11_11") (pintype "passive"))
      (node (ref "SV24") (pin "3") (pinfunction "3_3") (pintype "passive"))
    )
    (net (code "189") (name "Net-(IC12-Pad12)") (class "Default")
      (node (ref "IC12") (pin "12") (pinfunction "12_12") (pintype "passive"))
      (node (ref "SV24") (pin "4") (pinfunction "4_4") (pintype "passive"))
    )
    (net (code "190") (name "Net-(IC12-Pad13)") (class "Default")
      (node (ref "IC12") (pin "13") (pinfunction "13_13") (pintype "passive"))
      (node (ref "SV24") (pin "5") (pinfunction "5_5") (pintype "passive"))
    )
    (net (code "191") (name "Net-(IC12-Pad14)") (class "Default")
      (node (ref "IC12") (pin "14") (pinfunction "14_14") (pintype "passive"))
      (node (ref "SV24") (pin "6") (pinfunction "6_6") (pintype "passive"))
    )
    (net (code "192") (name "Net-(IC12-Pad15)") (class "Default")
      (node (ref "IC12") (pin "15") (pinfunction "15_15") (pintype "passive"))
      (node (ref "SV24") (pin "7") (pinfunction "7_7") (pintype "passive"))
    )
    (net (code "193") (name "Net-(IC12-Pad16)") (class "Default")
      (node (ref "IC12") (pin "16") (pinfunction "16_16") (pintype "passive"))
      (node (ref "SV24") (pin "8") (pinfunction "8_8") (pintype "passive"))
    )
    (net (code "194") (name "Net-(IC13-Pad1)") (class "Default")
      (node (ref "IC13") (pin "1") (pinfunction "1_1") (pintype "passive"))
      (node (ref "SV25") (pin "2") (pinfunction "2_2") (pintype "passive"))
    )
    (net (code "195") (name "Net-(IC13-Pad2)") (class "Default")
      (node (ref "IC13") (pin "2") (pinfunction "2_2") (pintype "passive"))
      (node (ref "SV25") (pin "3") (pinfunction "3_3") (pintype "passive"))
    )
    (net (code "196") (name "Net-(IC13-Pad3)") (class "Default")
      (node (ref "IC13") (pin "3") (pinfunction "3_3") (pintype "passive"))
      (node (ref "SV25") (pin "4") (pinfunction "4_4") (pintype "passive"))
    )
    (net (code "197") (name "Net-(IC13-Pad4)") (class "Default")
      (node (ref "IC13") (pin "4") (pinfunction "4_4") (pintype "passive"))
      (node (ref "SV25") (pin "5") (pinfunction "5_5") (pintype "passive"))
    )
    (net (code "198") (name "Net-(IC13-Pad5)") (class "Default")
      (node (ref "IC13") (pin "5") (pinfunction "5_5") (pintype "passive"))
      (node (ref "SV25") (pin "6") (pinfunction "6_6") (pintype "passive"))
    )
    (net (code "199") (name "Net-(IC13-Pad6)") (class "Default")
      (node (ref "IC13") (pin "6") (pinfunction "6_6") (pintype "passive"))
      (node (ref "SV25") (pin "7") (pinfunction "7_7") (pintype "passive"))
    )
    (net (code "200") (name "Net-(IC13-Pad7)") (class "Default")
      (node (ref "IC13") (pin "7") (pinfunction "7_7") (pintype "passive"))
      (node (ref "SV25") (pin "8") (pinfunction "8_8") (pintype "passive"))
    )
    (net (code "201") (name "Net-(IC13-Pad8)") (class "Default")
      (node (ref "IC13") (pin "8") (pinfunction "8_8") (pintype "passive"))
      (node (ref "SV25") (pin "9") (pinfunction "9_9") (pintype "passive"))
    )
    (net (code "202") (name "Net-(IC13-Pad9)") (class "Default")
      (node (ref "IC13") (pin "9") (pinfunction "9_9") (pintype "passive"))
      (node (ref "SV26") (pin "1") (pinfunction "1_1") (pintype "passive"))
    )
    (net (code "203") (name "Net-(IC13-Pad10)") (class "Default")
      (node (ref "IC13") (pin "10") (pinfunction "10_10") (pintype "passive"))
      (node (ref "SV26") (pin "2") (pinfunction "2_2") (pintype "passive"))
    )
    (net (code "204") (name "Net-(IC13-Pad11)") (class "Default")
      (node (ref "IC13") (pin "11") (pinfunction "11_11") (pintype "passive"))
      (node (ref "SV26") (pin "3") (pinfunction "3_3") (pintype "passive"))
    )
    (net (code "205") (name "Net-(IC13-Pad12)") (class "Default")
      (node (ref "IC13") (pin "12") (pinfunction "12_12") (pintype "passive"))
      (node (ref "SV26") (pin "4") (pinfunction "4_4") (pintype "passive"))
    )
    (net (code "206") (name "Net-(IC13-Pad13)") (class "Default")
      (node (ref "IC13") (pin "13") (pinfunction "13_13") (pintype "passive"))
      (node (ref "SV26") (pin "5") (pinfunction "5_5") (pintype "passive"))
    )
    (net (code "207") (name "Net-(IC13-Pad14)") (class "Default")
      (node (ref "IC13") (pin "14") (pinfunction "14_14") (pintype "passive"))
      (node (ref "SV26") (pin "6") (pinfunction "6_6") (pintype "passive"))
    )
    (net (code "208") (name "Net-(IC13-Pad15)") (class "Default")
      (node (ref "IC13") (pin "15") (pinfunction "15_15") (pintype "passive"))
      (node (ref "SV26") (pin "7") (pinfunction "7_7") (pintype "passive"))
    )
    (net (code "209") (name "Net-(IC13-Pad16)") (class "Default")
      (node (ref "IC13") (pin "16") (pinfunction "16_16") (pintype "passive"))
      (node (ref "SV26") (pin "8") (pinfunction "8_8") (pintype "passive"))
    )
    (net (code "210") (name "Net-(IC14-Pad1)") (class "Default")
      (node (ref "IC14") (pin "1") (pinfunction "1_1") (pintype "passive"))
      (node (ref "SV27") (pin "2") (pinfunction "2_2") (pintype "passive"))
    )
    (net (code "211") (name "Net-(IC14-Pad2)") (class "Default")
      (node (ref "IC14") (pin "2") (pinfunction "2_2") (pintype "passive"))
      (node (ref "SV27") (pin "3") (pinfunction "3_3") (pintype "passive"))
    )
    (net (code "212") (name "Net-(IC14-Pad3)") (class "Default")
      (node (ref "IC14") (pin "3") (pinfunction "3_3") (pintype "passive"))
      (node (ref "SV27") (pin "4") (pinfunction "4_4") (pintype "passive"))
    )
    (net (code "213") (name "Net-(IC14-Pad4)") (class "Default")
      (node (ref "IC14") (pin "4") (pinfunction "4_4") (pintype "passive"))
      (node (ref "SV27") (pin "5") (pinfunction "5_5") (pintype "passive"))
    )
    (net (code "214") (name "Net-(IC14-Pad5)") (class "Default")
      (node (ref "IC14") (pin "5") (pinfunction "5_5") (pintype "passive"))
      (node (ref "SV27") (pin "6") (pinfunction "6_6") (pintype "passive"))
    )
    (net (code "215") (name "Net-(IC14-Pad6)") (class "Default")
      (node (ref "IC14") (pin "6") (pinfunction "6_6") (pintype "passive"))
      (node (ref "SV27") (pin "7") (pinfunction "7_7") (pintype "passive"))
    )
    (net (code "216") (name "Net-(IC14-Pad7)") (class "Default")
      (node (ref "IC14") (pin "7") (pinfunction "7_7") (pintype "passive"))
      (node (ref "SV27") (pin "8") (pinfunction "8_8") (pintype "passive"))
    )
    (net (code "217") (name "Net-(IC14-Pad8)") (class "Default")
      (node (ref "IC14") (pin "8") (pinfunction "8_8") (pintype "passive"))
      (node (ref "SV27") (pin "9") (pinfunction "9_9") (pintype "passive"))
    )
    (net (code "218") (name "Net-(IC14-Pad9)") (class "Default")
      (node (ref "IC14") (pin "9") (pinfunction "9_9") (pintype "passive"))
      (node (ref "SV28") (pin "1") (pinfunction "1_1") (pintype "passive"))
    )
    (net (code "219") (name "Net-(IC14-Pad10)") (class "Default")
      (node (ref "IC14") (pin "10") (pinfunction "10_10") (pintype "passive"))
      (node (ref "SV28") (pin "2") (pinfunction "2_2") (pintype "passive"))
    )
    (net (code "220") (name "Net-(IC14-Pad11)") (class "Default")
      (node (ref "IC14") (pin "11") (pinfunction "11_11") (pintype "passive"))
      (node (ref "SV28") (pin "3") (pinfunction "3_3") (pintype "passive"))
    )
    (net (code "221") (name "Net-(IC14-Pad12)") (class "Default")
      (node (ref "IC14") (pin "12") (pinfunction "12_12") (pintype "passive"))
      (node (ref "SV28") (pin "4") (pinfunction "4_4") (pintype "passive"))
    )
    (net (code "222") (name "Net-(IC14-Pad13)") (class "Default")
      (node (ref "IC14") (pin "13") (pinfunction "13_13") (pintype "passive"))
      (node (ref "SV28") (pin "5") (pinfunction "5_5") (pintype "passive"))
    )
    (net (code "223") (name "Net-(IC14-Pad14)") (class "Default")
      (node (ref "IC14") (pin "14") (pinfunction "14_14") (pintype "passive"))
      (node (ref "SV28") (pin "6") (pinfunction "6_6") (pintype "passive"))
    )
    (net (code "224") (name "Net-(IC14-Pad15)") (class "Default")
      (node (ref "IC14") (pin "15") (pinfunction "15_15") (pintype "passive"))
      (node (ref "SV28") (pin "7") (pinfunction "7_7") (pintype "passive"))
    )
    (net (code "225") (name "Net-(IC14-Pad16)") (class "Default")
      (node (ref "IC14") (pin "16") (pinfunction "16_16") (pintype "passive"))
      (node (ref "SV28") (pin "8") (pinfunction "8_8") (pintype "passive"))
    )
    (net (code "226") (name "Net-(IC15-Pad1)") (class "Default")
      (node (ref "IC15") (pin "1") (pinfunction "1_1") (pintype "passive"))
      (node (ref "SV29") (pin "2") (pinfunction "2_2") (pintype "passive"))
    )
    (net (code "227") (name "Net-(IC15-Pad2)") (class "Default")
      (node (ref "IC15") (pin "2") (pinfunction "2_2") (pintype "passive"))
      (node (ref "SV29") (pin "3") (pinfunction "3_3") (pintype "passive"))
    )
    (net (code "228") (name "Net-(IC15-Pad3)") (class "Default")
      (node (ref "IC15") (pin "3") (pinfunction "3_3") (pintype "passive"))
      (node (ref "SV29") (pin "4") (pinfunction "4_4") (pintype "passive"))
    )
    (net (code "229") (name "Net-(IC15-Pad4)") (class "Default")
      (node (ref "IC15") (pin "4") (pinfunction "4_4") (pintype "passive"))
      (node (ref "SV29") (pin "5") (pinfunction "5_5") (pintype "passive"))
    )
    (net (code "230") (name "Net-(IC15-Pad5)") (class "Default")
      (node (ref "IC15") (pin "5") (pinfunction "5_5") (pintype "passive"))
      (node (ref "SV29") (pin "6") (pinfunction "6_6") (pintype "passive"))
    )
    (net (code "231") (name "Net-(IC15-Pad6)") (class "Default")
      (node (ref "IC15") (pin "6") (pinfunction "6_6") (pintype "passive"))
      (node (ref "SV29") (pin "7") (pinfunction "7_7") (pintype "passive"))
    )
    (net (code "232") (name "Net-(IC15-Pad7)") (class "Default")
      (node (ref "IC15") (pin "7") (pinfunction "7_7") (pintype "passive"))
      (node (ref "SV29") (pin "8") (pinfunction "8_8") (pintype "passive"))
    )
    (net (code "233") (name "Net-(IC15-Pad8)") (class "Default")
      (node (ref "IC15") (pin "8") (pinfunction "8_8") (pintype "passive"))
      (node (ref "SV29") (pin "9") (pinfunction "9_9") (pintype "passive"))
    )
    (net (code "234") (name "Net-(IC15-Pad9)") (class "Default")
      (node (ref "IC15") (pin "9") (pinfunction "9_9") (pintype "passive"))
      (node (ref "SV30") (pin "1") (pinfunction "1_1") (pintype "passive"))
    )
    (net (code "235") (name "Net-(IC15-Pad10)") (class "Default")
      (node (ref "IC15") (pin "10") (pinfunction "10_10") (pintype "passive"))
      (node (ref "SV30") (pin "2") (pinfunction "2_2") (pintype "passive"))
    )
    (net (code "236") (name "Net-(IC15-Pad11)") (class "Default")
      (node (ref "IC15") (pin "11") (pinfunction "11_11") (pintype "passive"))
      (node (ref "SV30") (pin "3") (pinfunction "3_3") (pintype "passive"))
    )
    (net (code "237") (name "Net-(IC15-Pad12)") (class "Default")
      (node (ref "IC15") (pin "12") (pinfunction "12_12") (pintype "passive"))
      (node (ref "SV30") (pin "4") (pinfunction "4_4") (pintype "passive"))
    )
    (net (code "238") (name "Net-(IC15-Pad13)") (class "Default")
      (node (ref "IC15") (pin "13") (pinfunction "13_13") (pintype "passive"))
      (node (ref "SV30") (pin "5") (pinfunction "5_5") (pintype "passive"))
    )
    (net (code "239") (name "Net-(IC15-Pad14)") (class "Default")
      (node (ref "IC15") (pin "14") (pinfunction "14_14") (pintype "passive"))
      (node (ref "SV30") (pin "6") (pinfunction "6_6") (pintype "passive"))
    )
    (net (code "240") (name "Net-(IC15-Pad15)") (class "Default")
      (node (ref "IC15") (pin "15") (pinfunction "15_15") (pintype "passive"))
      (node (ref "SV30") (pin "7") (pinfunction "7_7") (pintype "passive"))
    )
    (net (code "241") (name "Net-(IC15-Pad16)") (class "Default")
      (node (ref "IC15") (pin "16") (pinfunction "16_16") (pintype "passive"))
      (node (ref "SV30") (pin "8") (pinfunction "8_8") (pintype "passive"))
    )
    (net (code "242") (name "Net-(IC16-Pad1)") (class "Default")
      (node (ref "IC16") (pin "1") (pinfunction "1_1") (pintype "passive"))
      (node (ref "SV31") (pin "2") (pinfunction "2_2") (pintype "passive"))
    )
    (net (code "243") (name "Net-(IC16-Pad2)") (class "Default")
      (node (ref "IC16") (pin "2") (pinfunction "2_2") (pintype "passive"))
      (node (ref "SV31") (pin "3") (pinfunction "3_3") (pintype "passive"))
    )
    (net (code "244") (name "Net-(IC16-Pad3)") (class "Default")
      (node (ref "IC16") (pin "3") (pinfunction "3_3") (pintype "passive"))
      (node (ref "SV31") (pin "4") (pinfunction "4_4") (pintype "passive"))
    )
    (net (code "245") (name "Net-(IC16-Pad4)") (class "Default")
      (node (ref "IC16") (pin "4") (pinfunction "4_4") (pintype "passive"))
      (node (ref "SV31") (pin "5") (pinfunction "5_5") (pintype "passive"))
    )
    (net (code "246") (name "Net-(IC16-Pad5)") (class "Default")
      (node (ref "IC16") (pin "5") (pinfunction "5_5") (pintype "passive"))
      (node (ref "SV31") (pin "6") (pinfunction "6_6") (pintype "passive"))
    )
    (net (code "247") (name "Net-(IC16-Pad6)") (class "Default")
      (node (ref "IC16") (pin "6") (pinfunction "6_6") (pintype "passive"))
      (node (ref "SV31") (pin "7") (pinfunction "7_7") (pintype "passive"))
    )
    (net (code "248") (name "Net-(IC16-Pad7)") (class "Default")
      (node (ref "IC16") (pin "7") (pinfunction "7_7") (pintype "passive"))
      (node (ref "SV31") (pin "8") (pinfunction "8_8") (pintype "passive"))
    )
    (net (code "249") (name "Net-(IC16-Pad8)") (class "Default")
      (node (ref "IC16") (pin "8") (pinfunction "8_8") (pintype "passive"))
      (node (ref "SV31") (pin "9") (pinfunction "9_9") (pintype "passive"))
    )
    (net (code "250") (name "Net-(IC16-Pad9)") (class "Default")
      (node (ref "IC16") (pin "9") (pinfunction "9_9") (pintype "passive"))
      (node (ref "SV32") (pin "1") (pinfunction "1_1") (pintype "passive"))
    )
    (net (code "251") (name "Net-(IC16-Pad10)") (class "Default")
      (node (ref "IC16") (pin "10") (pinfunction "10_10") (pintype "passive"))
      (node (ref "SV32") (pin "2") (pinfunction "2_2") (pintype "passive"))
    )
    (net (code "252") (name "Net-(IC16-Pad11)") (class "Default")
      (node (ref "IC16") (pin "11") (pinfunction "11_11") (pintype "passive"))
      (node (ref "SV32") (pin "3") (pinfunction "3_3") (pintype "passive"))
    )
    (net (code "253") (name "Net-(IC16-Pad12)") (class "Default")
      (node (ref "IC16") (pin "12") (pinfunction "12_12") (pintype "passive"))
      (node (ref "SV32") (pin "4") (pinfunction "4_4") (pintype "passive"))
    )
    (net (code "254") (name "Net-(IC16-Pad13)") (class "Default")
      (node (ref "IC16") (pin "13") (pinfunction "13_13") (pintype "passive"))
      (node (ref "SV32") (pin "5") (pinfunction "5_5") (pintype "passive"))
    )
    (net (code "255") (name "Net-(IC16-Pad14)") (class "Default")
      (node (ref "IC16") (pin "14") (pinfunction "14_14") (pintype "passive"))
      (node (ref "SV32") (pin "6") (pinfunction "6_6") (pintype "passive"))
    )
    (net (code "256") (name "Net-(IC16-Pad15)") (class "Default")
      (node (ref "IC16") (pin "15") (pinfunction "15_15") (pintype "passive"))
      (node (ref "SV32") (pin "7") (pinfunction "7_7") (pintype "passive"))
    )
    (net (code "257") (name "Net-(IC16-Pad16)") (class "Default")
      (node (ref "IC16") (pin "16") (pinfunction "16_16") (pintype "passive"))
      (node (ref "SV32") (pin "8") (pinfunction "8_8") (pintype "passive"))
    )
    (net (code "258") (name "Net-(IC17-Pad1)") (class "Default")
      (node (ref "IC17") (pin "1") (pinfunction "1_1") (pintype "passive"))
      (node (ref "SV33") (pin "2") (pinfunction "2_2") (pintype "passive"))
    )
    (net (code "259") (name "Net-(IC17-Pad2)") (class "Default")
      (node (ref "IC17") (pin "2") (pinfunction "2_2") (pintype "passive"))
      (node (ref "SV33") (pin "3") (pinfunction "3_3") (pintype "passive"))
    )
    (net (code "260") (name "Net-(IC17-Pad3)") (class "Default")
      (node (ref "IC17") (pin "3") (pinfunction "3_3") (pintype "passive"))
      (node (ref "SV33") (pin "4") (pinfunction "4_4") (pintype "passive"))
    )
    (net (code "261") (name "Net-(IC17-Pad4)") (class "Default")
      (node (ref "IC17") (pin "4") (pinfunction "4_4") (pintype "passive"))
      (node (ref "SV33") (pin "5") (pinfunction "5_5") (pintype "passive"))
    )
    (net (code "262") (name "Net-(IC17-Pad5)") (class "Default")
      (node (ref "IC17") (pin "5") (pinfunction "5_5") (pintype "passive"))
      (node (ref "SV33") (pin "6") (pinfunction "6_6") (pintype "passive"))
    )
    (net (code "263") (name "Net-(IC17-Pad6)") (class "Default")
      (node (ref "IC17") (pin "6") (pinfunction "6_6") (pintype "passive"))
      (node (ref "SV33") (pin "7") (pinfunction "7_7") (pintype "passive"))
    )
    (net (code "264") (name "Net-(IC17-Pad7)") (class "Default")
      (node (ref "IC17") (pin "7") (pinfunction "7_7") (pintype "passive"))
      (node (ref "SV33") (pin "8") (pinfunction "8_8") (pintype "passive"))
    )
    (net (code "265") (name "Net-(IC17-Pad8)") (class "Default")
      (node (ref "IC17") (pin "8") (pinfunction "8_8") (pintype "passive"))
      (node (ref "SV33") (pin "9") (pinfunction "9_9") (pintype "passive"))
    )
    (net (code "266") (name "Net-(IC17-Pad9)") (class "Default")
      (node (ref "IC17") (pin "9") (pinfunction "9_9") (pintype "passive"))
      (node (ref "SV34") (pin "1") (pinfunction "1_1") (pintype "passive"))
    )
    (net (code "267") (name "Net-(IC17-Pad10)") (class "Default")
      (node (ref "IC17") (pin "10") (pinfunction "10_10") (pintype "passive"))
      (node (ref "SV34") (pin "2") (pinfunction "2_2") (pintype "passive"))
    )
    (net (code "268") (name "Net-(IC17-Pad11)") (class "Default")
      (node (ref "IC17") (pin "11") (pinfunction "11_11") (pintype "passive"))
      (node (ref "SV34") (pin "3") (pinfunction "3_3") (pintype "passive"))
    )
    (net (code "269") (name "Net-(IC17-Pad12)") (class "Default")
      (node (ref "IC17") (pin "12") (pinfunction "12_12") (pintype "passive"))
      (node (ref "SV34") (pin "4") (pinfunction "4_4") (pintype "passive"))
    )
    (net (code "270") (name "Net-(IC17-Pad13)") (class "Default")
      (node (ref "IC17") (pin "13") (pinfunction "13_13") (pintype "passive"))
      (node (ref "SV34") (pin "5") (pinfunction "5_5") (pintype "passive"))
    )
    (net (code "271") (name "Net-(IC17-Pad14)") (class "Default")
      (node (ref "IC17") (pin "14") (pinfunction "14_14") (pintype "passive"))
      (node (ref "SV34") (pin "6") (pinfunction "6_6") (pintype "passive"))
    )
    (net (code "272") (name "Net-(IC17-Pad15)") (class "Default")
      (node (ref "IC17") (pin "15") (pinfunction "15_15") (pintype "passive"))
      (node (ref "SV34") (pin "7") (pinfunction "7_7") (pintype "passive"))
    )
    (net (code "273") (name "Net-(IC17-Pad16)") (class "Default")
      (node (ref "IC17") (pin "16") (pinfunction "16_16") (pintype "passive"))
      (node (ref "SV34") (pin "8") (pinfunction "8_8") (pintype "passive"))
    )
    (net (code "274") (name "Net-(IC18-Pad1)") (class "Default")
      (node (ref "IC18") (pin "1") (pinfunction "1_1") (pintype "passive"))
      (node (ref "SV35") (pin "2") (pinfunction "2_2") (pintype "passive"))
    )
    (net (code "275") (name "Net-(IC18-Pad2)") (class "Default")
      (node (ref "IC18") (pin "2") (pinfunction "2_2") (pintype "passive"))
      (node (ref "SV35") (pin "3") (pinfunction "3_3") (pintype "passive"))
    )
    (net (code "276") (name "Net-(IC18-Pad3)") (class "Default")
      (node (ref "IC18") (pin "3") (pinfunction "3_3") (pintype "passive"))
      (node (ref "SV35") (pin "4") (pinfunction "4_4") (pintype "passive"))
    )
    (net (code "277") (name "Net-(IC18-Pad4)") (class "Default")
      (node (ref "IC18") (pin "4") (pinfunction "4_4") (pintype "passive"))
      (node (ref "SV35") (pin "5") (pinfunction "5_5") (pintype "passive"))
    )
    (net (code "278") (name "Net-(IC18-Pad5)") (class "Default")
      (node (ref "IC18") (pin "5") (pinfunction "5_5") (pintype "passive"))
      (node (ref "SV35") (pin "6") (pinfunction "6_6") (pintype "passive"))
    )
    (net (code "279") (name "Net-(IC18-Pad6)") (class "Default")
      (node (ref "IC18") (pin "6") (pinfunction "6_6") (pintype "passive"))
      (node (ref "SV35") (pin "7") (pinfunction "7_7") (pintype "passive"))
    )
    (net (code "280") (name "Net-(IC18-Pad7)") (class "Default")
      (node (ref "IC18") (pin "7") (pinfunction "7_7") (pintype "passive"))
      (node (ref "SV35") (pin "8") (pinfunction "8_8") (pintype "passive"))
    )
    (net (code "281") (name "Net-(IC18-Pad8)") (class "Default")
      (node (ref "IC18") (pin "8") (pinfunction "8_8") (pintype "passive"))
      (node (ref "SV35") (pin "9") (pinfunction "9_9") (pintype "passive"))
    )
    (net (code "282") (name "Net-(IC18-Pad9)") (class "Default")
      (node (ref "IC18") (pin "9") (pinfunction "9_9") (pintype "passive"))
      (node (ref "SV36") (pin "1") (pinfunction "1_1") (pintype "passive"))
    )
    (net (code "283") (name "Net-(IC18-Pad10)") (class "Default")
      (node (ref "IC18") (pin "10") (pinfunction "10_10") (pintype "passive"))
      (node (ref "SV36") (pin "2") (pinfunction "2_2") (pintype "passive"))
    )
    (net (code "284") (name "Net-(IC18-Pad11)") (class "Default")
      (node (ref "IC18") (pin "11") (pinfunction "11_11") (pintype "passive"))
      (node (ref "SV36") (pin "3") (pinfunction "3_3") (pintype "passive"))
    )
    (net (code "285") (name "Net-(IC18-Pad12)") (class "Default")
      (node (ref "IC18") (pin "12") (pinfunction "12_12") (pintype "passive"))
      (node (ref "SV36") (pin "4") (pinfunction "4_4") (pintype "passive"))
    )
    (net (code "286") (name "Net-(IC18-Pad13)") (class "Default")
      (node (ref "IC18") (pin "13") (pinfunction "13_13") (pintype "passive"))
      (node (ref "SV36") (pin "5") (pinfunction "5_5") (pintype "passive"))
    )
    (net (code "287") (name "Net-(IC18-Pad14)") (class "Default")
      (node (ref "IC18") (pin "14") (pinfunction "14_14") (pintype "passive"))
      (node (ref "SV36") (pin "6") (pinfunction "6_6") (pintype "passive"))
    )
    (net (code "288") (name "Net-(IC18-Pad15)") (class "Default")
      (node (ref "IC18") (pin "15") (pinfunction "15_15") (pintype "passive"))
      (node (ref "SV36") (pin "7") (pinfunction "7_7") (pintype "passive"))
    )
    (net (code "289") (name "Net-(IC18-Pad16)") (class "Default")
      (node (ref "IC18") (pin "16") (pinfunction "16_16") (pintype "passive"))
      (node (ref "SV36") (pin "8") (pinfunction "8_8") (pintype "passive"))
    )
    (net (code "290") (name "Net-(IC19-Pad1)") (class "Default")
      (node (ref "IC19") (pin "1") (pinfunction "1_1") (pintype "passive"))
      (node (ref "SV37") (pin "2") (pinfunction "2_2") (pintype "passive"))
    )
    (net (code "291") (name "Net-(IC19-Pad2)") (class "Default")
      (node (ref "IC19") (pin "2") (pinfunction "2_2") (pintype "passive"))
      (node (ref "SV37") (pin "3") (pinfunction "3_3") (pintype "passive"))
    )
    (net (code "292") (name "Net-(IC19-Pad3)") (class "Default")
      (node (ref "IC19") (pin "3") (pinfunction "3_3") (pintype "passive"))
      (node (ref "SV37") (pin "4") (pinfunction "4_4") (pintype "passive"))
    )
    (net (code "293") (name "Net-(IC19-Pad4)") (class "Default")
      (node (ref "IC19") (pin "4") (pinfunction "4_4") (pintype "passive"))
      (node (ref "SV37") (pin "5") (pinfunction "5_5") (pintype "passive"))
    )
    (net (code "294") (name "Net-(IC19-Pad5)") (class "Default")
      (node (ref "IC19") (pin "5") (pinfunction "5_5") (pintype "passive"))
      (node (ref "SV37") (pin "6") (pinfunction "6_6") (pintype "passive"))
    )
    (net (code "295") (name "Net-(IC19-Pad6)") (class "Default")
      (node (ref "IC19") (pin "6") (pinfunction "6_6") (pintype "passive"))
      (node (ref "SV37") (pin "7") (pinfunction "7_7") (pintype "passive"))
    )
    (net (code "296") (name "Net-(IC19-Pad7)") (class "Default")
      (node (ref "IC19") (pin "7") (pinfunction "7_7") (pintype "passive"))
      (node (ref "SV37") (pin "8") (pinfunction "8_8") (pintype "passive"))
    )
    (net (code "297") (name "Net-(IC19-Pad8)") (class "Default")
      (node (ref "IC19") (pin "8") (pinfunction "8_8") (pintype "passive"))
      (node (ref "SV37") (pin "9") (pinfunction "9_9") (pintype "passive"))
    )
    (net (code "298") (name "Net-(IC19-Pad9)") (class "Default")
      (node (ref "IC19") (pin "9") (pinfunction "9_9") (pintype "passive"))
      (node (ref "SV38") (pin "1") (pinfunction "1_1") (pintype "passive"))
    )
    (net (code "299") (name "Net-(IC19-Pad10)") (class "Default")
      (node (ref "IC19") (pin "10") (pinfunction "10_10") (pintype "passive"))
      (node (ref "SV38") (pin "2") (pinfunction "2_2") (pintype "passive"))
    )
    (net (code "300") (name "Net-(IC19-Pad11)") (class "Default")
      (node (ref "IC19") (pin "11") (pinfunction "11_11") (pintype "passive"))
      (node (ref "SV38") (pin "3") (pinfunction "3_3") (pintype "passive"))
    )
    (net (code "301") (name "Net-(IC19-Pad12)") (class "Default")
      (node (ref "IC19") (pin "12") (pinfunction "12_12") (pintype "passive"))
      (node (ref "SV38") (pin "4") (pinfunction "4_4") (pintype "passive"))
    )
    (net (code "302") (name "Net-(IC19-Pad13)") (class "Default")
      (node (ref "IC19") (pin "13") (pinfunction "13_13") (pintype "passive"))
      (node (ref "SV38") (pin "5") (pinfunction "5_5") (pintype "passive"))
    )
    (net (code "303") (name "Net-(IC19-Pad14)") (class "Default")
      (node (ref "IC19") (pin "14") (pinfunction "14_14") (pintype "passive"))
      (node (ref "SV38") (pin "6") (pinfunction "6_6") (pintype "passive"))
    )
    (net (code "304") (name "Net-(IC19-Pad15)") (class "Default")
      (node (ref "IC19") (pin "15") (pinfunction "15_15") (pintype "passive"))
      (node (ref "SV38") (pin "7") (pinfunction "7_7") (pintype "passive"))
    )
    (net (code "305") (name "Net-(IC19-Pad16)") (class "Default")
      (node (ref "IC19") (pin "16") (pinfunction "16_16") (pintype "passive"))
      (node (ref "SV38") (pin "8") (pinfunction "8_8") (pintype "passive"))
    )
    (net (code "306") (name "Net-(IC20-Pad1)") (class "Default")
      (node (ref "IC20") (pin "1") (pinfunction "1_1") (pintype "passive"))
      (node (ref "SV39") (pin "2") (pinfunction "2_2") (pintype "passive"))
    )
    (net (code "307") (name "Net-(IC20-Pad2)") (class "Default")
      (node (ref "IC20") (pin "2") (pinfunction "2_2") (pintype "passive"))
      (node (ref "SV39") (pin "3") (pinfunction "3_3") (pintype "passive"))
    )
    (net (code "308") (name "Net-(IC20-Pad3)") (class "Default")
      (node (ref "IC20") (pin "3") (pinfunction "3_3") (pintype "passive"))
      (node (ref "SV39") (pin "4") (pinfunction "4_4") (pintype "passive"))
    )
    (net (code "309") (name "Net-(IC20-Pad4)") (class "Default")
      (node (ref "IC20") (pin "4") (pinfunction "4_4") (pintype "passive"))
      (node (ref "SV39") (pin "5") (pinfunction "5_5") (pintype "passive"))
    )
    (net (code "310") (name "Net-(IC20-Pad5)") (class "Default")
      (node (ref "IC20") (pin "5") (pinfunction "5_5") (pintype "passive"))
      (node (ref "SV39") (pin "6") (pinfunction "6_6") (pintype "passive"))
    )
    (net (code "311") (name "Net-(IC20-Pad6)") (class "Default")
      (node (ref "IC20") (pin "6") (pinfunction "6_6") (pintype "passive"))
      (node (ref "SV39") (pin "7") (pinfunction "7_7") (pintype "passive"))
    )
    (net (code "312") (name "Net-(IC20-Pad7)") (class "Default")
      (node (ref "IC20") (pin "7") (pinfunction "7_7") (pintype "passive"))
      (node (ref "SV39") (pin "8") (pinfunction "8_8") (pintype "passive"))
    )
    (net (code "313") (name "Net-(IC20-Pad8)") (class "Default")
      (node (ref "IC20") (pin "8") (pinfunction "8_8") (pintype "passive"))
      (node (ref "SV39") (pin "9") (pinfunction "9_9") (pintype "passive"))
    )
    (net (code "314") (name "Net-(IC20-Pad9)") (class "Default")
      (node (ref "IC20") (pin "9") (pinfunction "9_9") (pintype "passive"))
      (node (ref "SV40") (pin "1") (pinfunction "1_1") (pintype "passive"))
    )
    (net (code "315") (name "Net-(IC20-Pad10)") (class "Default")
      (node (ref "IC20") (pin "10") (pinfunction "10_10") (pintype "passive"))
      (node (ref "SV40") (pin "2") (pinfunction "2_2") (pintype "passive"))
    )
    (net (code "316") (name "Net-(IC20-Pad11)") (class "Default")
      (node (ref "IC20") (pin "11") (pinfunction "11_11") (pintype "passive"))
      (node (ref "SV40") (pin "3") (pinfunction "3_3") (pintype "passive"))
    )
    (net (code "317") (name "Net-(IC20-Pad12)") (class "Default")
      (node (ref "IC20") (pin "12") (pinfunction "12_12") (pintype "passive"))
      (node (ref "SV40") (pin "4") (pinfunction "4_4") (pintype "passive"))
    )
    (net (code "318") (name "Net-(IC20-Pad13)") (class "Default")
      (node (ref "IC20") (pin "13") (pinfunction "13_13") (pintype "passive"))
      (node (ref "SV40") (pin "5") (pinfunction "5_5") (pintype "passive"))
    )
    (net (code "319") (name "Net-(IC20-Pad14)") (class "Default")
      (node (ref "IC20") (pin "14") (pinfunction "14_14") (pintype "passive"))
      (node (ref "SV40") (pin "6") (pinfunction "6_6") (pintype "passive"))
    )
    (net (code "320") (name "Net-(IC20-Pad15)") (class "Default")
      (node (ref "IC20") (pin "15") (pinfunction "15_15") (pintype "passive"))
      (node (ref "SV40") (pin "7") (pinfunction "7_7") (pintype "passive"))
    )
    (net (code "321") (name "Net-(IC20-Pad16)") (class "Default")
      (node (ref "IC20") (pin "16") (pinfunction "16_16") (pintype "passive"))
      (node (ref "SV40") (pin "8") (pinfunction "8_8") (pintype "passive"))
    )
    (net (code "322") (name "Net-(IC21-Pad1)") (class "Default")
      (node (ref "IC21") (pin "1") (pinfunction "1_1") (pintype "passive"))
      (node (ref "SV41") (pin "2") (pinfunction "2_2") (pintype "passive"))
    )
    (net (code "323") (name "Net-(IC21-Pad2)") (class "Default")
      (node (ref "IC21") (pin "2") (pinfunction "2_2") (pintype "passive"))
      (node (ref "SV41") (pin "3") (pinfunction "3_3") (pintype "passive"))
    )
    (net (code "324") (name "Net-(IC21-Pad3)") (class "Default")
      (node (ref "IC21") (pin "3") (pinfunction "3_3") (pintype "passive"))
      (node (ref "SV41") (pin "4") (pinfunction "4_4") (pintype "passive"))
    )
    (net (code "325") (name "Net-(IC21-Pad4)") (class "Default")
      (node (ref "IC21") (pin "4") (pinfunction "4_4") (pintype "passive"))
      (node (ref "SV41") (pin "5") (pinfunction "5_5") (pintype "passive"))
    )
    (net (code "326") (name "Net-(IC21-Pad5)") (class "Default")
      (node (ref "IC21") (pin "5") (pinfunction "5_5") (pintype "passive"))
      (node (ref "SV41") (pin "6") (pinfunction "6_6") (pintype "passive"))
    )
    (net (code "327") (name "Net-(IC21-Pad6)") (class "Default")
      (node (ref "IC21") (pin "6") (pinfunction "6_6") (pintype "passive"))
      (node (ref "SV41") (pin "7") (pinfunction "7_7") (pintype "passive"))
    )
    (net (code "328") (name "Net-(IC21-Pad7)") (class "Default")
      (node (ref "IC21") (pin "7") (pinfunction "7_7") (pintype "passive"))
      (node (ref "SV41") (pin "8") (pinfunction "8_8") (pintype "passive"))
    )
    (net (code "329") (name "Net-(IC21-Pad8)") (class "Default")
      (node (ref "IC21") (pin "8") (pinfunction "8_8") (pintype "passive"))
      (node (ref "SV41") (pin "9") (pinfunction "9_9") (pintype "passive"))
    )
    (net (code "330") (name "Net-(IC21-Pad9)") (class "Default")
      (node (ref "IC21") (pin "9") (pinfunction "9_9") (pintype "passive"))
      (node (ref "SV42") (pin "1") (pinfunction "1_1") (pintype "passive"))
    )
    (net (code "331") (name "Net-(IC21-Pad10)") (class "Default")
      (node (ref "IC21") (pin "10") (pinfunction "10_10") (pintype "passive"))
      (node (ref "SV42") (pin "2") (pinfunction "2_2") (pintype "passive"))
    )
    (net (code "332") (name "Net-(IC21-Pad11)") (class "Default")
      (node (ref "IC21") (pin "11") (pinfunction "11_11") (pintype "passive"))
      (node (ref "SV42") (pin "3") (pinfunction "3_3") (pintype "passive"))
    )
    (net (code "333") (name "Net-(IC21-Pad12)") (class "Default")
      (node (ref "IC21") (pin "12") (pinfunction "12_12") (pintype "passive"))
      (node (ref "SV42") (pin "4") (pinfunction "4_4") (pintype "passive"))
    )
    (net (code "334") (name "Net-(IC21-Pad13)") (class "Default")
      (node (ref "IC21") (pin "13") (pinfunction "13_13") (pintype "passive"))
      (node (ref "SV42") (pin "5") (pinfunction "5_5") (pintype "passive"))
    )
    (net (code "335") (name "Net-(IC21-Pad14)") (class "Default")
      (node (ref "IC21") (pin "14") (pinfunction "14_14") (pintype "passive"))
      (node (ref "SV42") (pin "6") (pinfunction "6_6") (pintype "passive"))
    )
    (net (code "336") (name "Net-(IC21-Pad15)") (class "Default")
      (node (ref "IC21") (pin "15") (pinfunction "15_15") (pintype "passive"))
      (node (ref "SV42") (pin "7") (pinfunction "7_7") (pintype "passive"))
    )
    (net (code "337") (name "Net-(IC21-Pad16)") (class "Default")
      (node (ref "IC21") (pin "16") (pinfunction "16_16") (pintype "passive"))
      (node (ref "SV42") (pin "8") (pinfunction "8_8") (pintype "passive"))
    )
    (net (code "338") (name "Net-(IC22-Pad1)") (class "Default")
      (node (ref "IC22") (pin "1") (pinfunction "1_1") (pintype "passive"))
      (node (ref "SV43") (pin "2") (pinfunction "2_2") (pintype "passive"))
    )
    (net (code "339") (name "Net-(IC22-Pad2)") (class "Default")
      (node (ref "IC22") (pin "2") (pinfunction "2_2") (pintype "passive"))
      (node (ref "SV43") (pin "3") (pinfunction "3_3") (pintype "passive"))
    )
    (net (code "340") (name "Net-(IC22-Pad3)") (class "Default")
      (node (ref "IC22") (pin "3") (pinfunction "3_3") (pintype "passive"))
      (node (ref "SV43") (pin "4") (pinfunction "4_4") (pintype "passive"))
    )
    (net (code "341") (name "Net-(IC22-Pad4)") (class "Default")
      (node (ref "IC22") (pin "4") (pinfunction "4_4") (pintype "passive"))
      (node (ref "SV43") (pin "5") (pinfunction "5_5") (pintype "passive"))
    )
    (net (code "342") (name "Net-(IC22-Pad5)") (class "Default")
      (node (ref "IC22") (pin "5") (pinfunction "5_5") (pintype "passive"))
      (node (ref "SV43") (pin "6") (pinfunction "6_6") (pintype "passive"))
    )
    (net (code "343") (name "Net-(IC22-Pad6)") (class "Default")
      (node (ref "IC22") (pin "6") (pinfunction "6_6") (pintype "passive"))
      (node (ref "SV43") (pin "7") (pinfunction "7_7") (pintype "passive"))
    )
    (net (code "344") (name "Net-(IC22-Pad7)") (class "Default")
      (node (ref "IC22") (pin "7") (pinfunction "7_7") (pintype "passive"))
      (node (ref "SV43") (pin "8") (pinfunction "8_8") (pintype "passive"))
    )
    (net (code "345") (name "Net-(IC22-Pad8)") (class "Default")
      (node (ref "IC22") (pin "8") (pinfunction "8_8") (pintype "passive"))
      (node (ref "SV43") (pin "9") (pinfunction "9_9") (pintype "passive"))
    )
    (net (code "346") (name "Net-(IC22-Pad9)") (class "Default")
      (node (ref "IC22") (pin "9") (pinfunction "9_9") (pintype "passive"))
      (node (ref "SV44") (pin "1") (pinfunction "1_1") (pintype "passive"))
    )
    (net (code "347") (name "Net-(IC22-Pad10)") (class "Default")
      (node (ref "IC22") (pin "10") (pinfunction "10_10") (pintype "passive"))
      (node (ref "SV44") (pin "2") (pinfunction "2_2") (pintype "passive"))
    )
    (net (code "348") (name "Net-(IC22-Pad11)") (class "Default")
      (node (ref "IC22") (pin "11") (pinfunction "11_11") (pintype "passive"))
      (node (ref "SV44") (pin "3") (pinfunction "3_3") (pintype "passive"))
    )
    (net (code "349") (name "Net-(IC22-Pad12)") (class "Default")
      (node (ref "IC22") (pin "12") (pinfunction "12_12") (pintype "passive"))
      (node (ref "SV44") (pin "4") (pinfunction "4_4") (pintype "passive"))
    )
    (net (code "350") (name "Net-(IC22-Pad13)") (class "Default")
      (node (ref "IC22") (pin "13") (pinfunction "13_13") (pintype "passive"))
      (node (ref "SV44") (pin "5") (pinfunction "5_5") (pintype "passive"))
    )
    (net (code "351") (name "Net-(IC22-Pad14)") (class "Default")
      (node (ref "IC22") (pin "14") (pinfunction "14_14") (pintype "passive"))
      (node (ref "SV44") (pin "6") (pinfunction "6_6") (pintype "passive"))
    )
    (net (code "352") (name "Net-(IC22-Pad15)") (class "Default")
      (node (ref "IC22") (pin "15") (pinfunction "15_15") (pintype "passive"))
      (node (ref "SV44") (pin "7") (pinfunction "7_7") (pintype "passive"))
    )
    (net (code "353") (name "Net-(IC22-Pad16)") (class "Default")
      (node (ref "IC22") (pin "16") (pinfunction "16_16") (pintype "passive"))
      (node (ref "SV44") (pin "8") (pinfunction "8_8") (pintype "passive"))
    )
    (net (code "354") (name "Net-(IC23-Pad1)") (class "Default")
      (node (ref "IC23") (pin "1") (pinfunction "1_1") (pintype "passive"))
      (node (ref "SV45") (pin "2") (pinfunction "2_2") (pintype "passive"))
    )
    (net (code "355") (name "Net-(IC23-Pad2)") (class "Default")
      (node (ref "IC23") (pin "2") (pinfunction "2_2") (pintype "passive"))
      (node (ref "SV45") (pin "3") (pinfunction "3_3") (pintype "passive"))
    )
    (net (code "356") (name "Net-(IC23-Pad3)") (class "Default")
      (node (ref "IC23") (pin "3") (pinfunction "3_3") (pintype "passive"))
      (node (ref "SV45") (pin "4") (pinfunction "4_4") (pintype "passive"))
    )
    (net (code "357") (name "Net-(IC23-Pad4)") (class "Default")
      (node (ref "IC23") (pin "4") (pinfunction "4_4") (pintype "passive"))
      (node (ref "SV45") (pin "5") (pinfunction "5_5") (pintype "passive"))
    )
    (net (code "358") (name "Net-(IC23-Pad5)") (class "Default")
      (node (ref "IC23") (pin "5") (pinfunction "5_5") (pintype "passive"))
      (node (ref "SV45") (pin "6") (pinfunction "6_6") (pintype "passive"))
    )
    (net (code "359") (name "Net-(IC23-Pad6)") (class "Default")
      (node (ref "IC23") (pin "6") (pinfunction "6_6") (pintype "passive"))
      (node (ref "SV45") (pin "7") (pinfunction "7_7") (pintype "passive"))
    )
    (net (code "360") (name "Net-(IC23-Pad7)") (class "Default")
      (node (ref "IC23") (pin "7") (pinfunction "7_7") (pintype "passive"))
      (node (ref "SV45") (pin "8") (pinfunction "8_8") (pintype "passive"))
    )
    (net (code "361") (name "Net-(IC23-Pad8)") (class "Default")
      (node (ref "IC23") (pin "8") (pinfunction "8_8") (pintype "passive"))
      (node (ref "SV45") (pin "9") (pinfunction "9_9") (pintype "passive"))
    )
    (net (code "362") (name "Net-(IC23-Pad9)") (class "Default")
      (node (ref "IC23") (pin "9") (pinfunction "9_9") (pintype "passive"))
      (node (ref "SV46") (pin "1") (pinfunction "1_1") (pintype "passive"))
    )
    (net (code "363") (name "Net-(IC23-Pad10)") (class "Default")
      (node (ref "IC23") (pin "10") (pinfunction "10_10") (pintype "passive"))
      (node (ref "SV46") (pin "2") (pinfunction "2_2") (pintype "passive"))
    )
    (net (code "364") (name "Net-(IC23-Pad11)") (class "Default")
      (node (ref "IC23") (pin "11") (pinfunction "11_11") (pintype "passive"))
      (node (ref "SV46") (pin "3") (pinfunction "3_3") (pintype "passive"))
    )
    (net (code "365") (name "Net-(IC23-Pad12)") (class "Default")
      (node (ref "IC23") (pin "12") (pinfunction "12_12") (pintype "passive"))
      (node (ref "SV46") (pin "4") (pinfunction "4_4") (pintype "passive"))
    )
    (net (code "366") (name "Net-(IC23-Pad13)") (class "Default")
      (node (ref "IC23") (pin "13") (pinfunction "13_13") (pintype "passive"))
      (node (ref "SV46") (pin "5") (pinfunction "5_5") (pintype "passive"))
    )
    (net (code "367") (name "Net-(IC23-Pad14)") (class "Default")
      (node (ref "IC23") (pin "14") (pinfunction "14_14") (pintype "passive"))
      (node (ref "SV46") (pin "6") (pinfunction "6_6") (pintype "passive"))
    )
    (net (code "368") (name "Net-(IC23-Pad15)") (class "Default")
      (node (ref "IC23") (pin "15") (pinfunction "15_15") (pintype "passive"))
      (node (ref "SV46") (pin "7") (pinfunction "7_7") (pintype "passive"))
    )
    (net (code "369") (name "Net-(IC23-Pad16)") (class "Default")
      (node (ref "IC23") (pin "16") (pinfunction "16_16") (pintype "passive"))
      (node (ref "SV46") (pin "8") (pinfunction "8_8") (pintype "passive"))
    )
    (net (code "370") (name "Net-(IC24-Pad1)") (class "Default")
      (node (ref "IC24") (pin "1") (pinfunction "1_1") (pintype "passive"))
      (node (ref "SV47") (pin "2") (pinfunction "2_2") (pintype "passive"))
    )
    (net (code "371") (name "Net-(IC24-Pad2)") (class "Default")
      (node (ref "IC24") (pin "2") (pinfunction "2_2") (pintype "passive"))
      (node (ref "SV47") (pin "3") (pinfunction "3_3") (pintype "passive"))
    )
    (net (code "372") (name "Net-(IC24-Pad3)") (class "Default")
      (node (ref "IC24") (pin "3") (pinfunction "3_3") (pintype "passive"))
      (node (ref "SV47") (pin "4") (pinfunction "4_4") (pintype "passive"))
    )
    (net (code "373") (name "Net-(IC24-Pad4)") (class "Default")
      (node (ref "IC24") (pin "4") (pinfunction "4_4") (pintype "passive"))
      (node (ref "SV47") (pin "5") (pinfunction "5_5") (pintype "passive"))
    )
    (net (code "374") (name "Net-(IC24-Pad5)") (class "Default")
      (node (ref "IC24") (pin "5") (pinfunction "5_5") (pintype "passive"))
      (node (ref "SV47") (pin "6") (pinfunction "6_6") (pintype "passive"))
    )
    (net (code "375") (name "Net-(IC24-Pad6)") (class "Default")
      (node (ref "IC24") (pin "6") (pinfunction "6_6") (pintype "passive"))
      (node (ref "SV47") (pin "7") (pinfunction "7_7") (pintype "passive"))
    )
    (net (code "376") (name "Net-(IC24-Pad7)") (class "Default")
      (node (ref "IC24") (pin "7") (pinfunction "7_7") (pintype "passive"))
      (node (ref "SV47") (pin "8") (pinfunction "8_8") (pintype "passive"))
    )
    (net (code "377") (name "Net-(IC24-Pad8)") (class "Default")
      (node (ref "IC24") (pin "8") (pinfunction "8_8") (pintype "passive"))
      (node (ref "SV47") (pin "9") (pinfunction "9_9") (pintype "passive"))
    )
    (net (code "378") (name "Net-(IC24-Pad9)") (class "Default")
      (node (ref "IC24") (pin "9") (pinfunction "9_9") (pintype "passive"))
      (node (ref "SV48") (pin "1") (pinfunction "1_1") (pintype "passive"))
    )
    (net (code "379") (name "Net-(IC24-Pad10)") (class "Default")
      (node (ref "IC24") (pin "10") (pinfunction "10_10") (pintype "passive"))
      (node (ref "SV48") (pin "2") (pinfunction "2_2") (pintype "passive"))
    )
    (net (code "380") (name "Net-(IC24-Pad11)") (class "Default")
      (node (ref "IC24") (pin "11") (pinfunction "11_11") (pintype "passive"))
      (node (ref "SV48") (pin "3") (pinfunction "3_3") (pintype "passive"))
    )
    (net (code "381") (name "Net-(IC24-Pad12)") (class "Default")
      (node (ref "IC24") (pin "12") (pinfunction "12_12") (pintype "passive"))
      (node (ref "SV48") (pin "4") (pinfunction "4_4") (pintype "passive"))
    )
    (net (code "382") (name "Net-(IC24-Pad13)") (class "Default")
      (node (ref "IC24") (pin "13") (pinfunction "13_13") (pintype "passive"))
      (node (ref "SV48") (pin "5") (pinfunction "5_5") (pintype "passive"))
    )
    (net (code "383") (name "Net-(IC24-Pad14)") (class "Default")
      (node (ref "IC24") (pin "14") (pinfunction "14_14") (pintype "passive"))
      (node (ref "SV48") (pin "6") (pinfunction "6_6") (pintype "passive"))
    )
    (net (code "384") (name "Net-(IC24-Pad15)") (class "Default")
      (node (ref "IC24") (pin "15") (pinfunction "15_15") (pintype "passive"))
      (node (ref "SV48") (pin "7") (pinfunction "7_7") (pintype "passive"))
    )
    (net (code "385") (name "Net-(IC24-Pad16)") (class "Default")
      (node (ref "IC24") (pin "16") (pinfunction "16_16") (pintype "passive"))
      (node (ref "SV48") (pin "8") (pinfunction "8_8") (pintype "passive"))
    )
    (net (code "386") (name "Net-(IC25-Pad1)") (class "Default")
      (node (ref "IC25") (pin "1") (pinfunction "1_1") (pintype "passive"))
      (node (ref "SV49") (pin "2") (pinfunction "2_2") (pintype "passive"))
    )
    (net (code "387") (name "Net-(IC25-Pad2)") (class "Default")
      (node (ref "IC25") (pin "2") (pinfunction "2_2") (pintype "passive"))
      (node (ref "SV49") (pin "3") (pinfunction "3_3") (pintype "passive"))
    )
    (net (code "388") (name "Net-(IC25-Pad3)") (class "Default")
      (node (ref "IC25") (pin "3") (pinfunction "3_3") (pintype "passive"))
      (node (ref "SV49") (pin "4") (pinfunction "4_4") (pintype "passive"))
    )
    (net (code "389") (name "Net-(IC25-Pad4)") (class "Default")
      (node (ref "IC25") (pin "4") (pinfunction "4_4") (pintype "passive"))
      (node (ref "SV49") (pin "5") (pinfunction "5_5") (pintype "passive"))
    )
    (net (code "390") (name "Net-(IC25-Pad5)") (class "Default")
      (node (ref "IC25") (pin "5") (pinfunction "5_5") (pintype "passive"))
      (node (ref "SV49") (pin "6") (pinfunction "6_6") (pintype "passive"))
    )
    (net (code "391") (name "Net-(IC25-Pad6)") (class "Default")
      (node (ref "IC25") (pin "6") (pinfunction "6_6") (pintype "passive"))
      (node (ref "SV49") (pin "7") (pinfunction "7_7") (pintype "passive"))
    )
    (net (code "392") (name "Net-(IC25-Pad7)") (class "Default")
      (node (ref "IC25") (pin "7") (pinfunction "7_7") (pintype "passive"))
      (node (ref "SV49") (pin "8") (pinfunction "8_8") (pintype "passive"))
    )
    (net (code "393") (name "Net-(IC25-Pad8)") (class "Default")
      (node (ref "IC25") (pin "8") (pinfunction "8_8") (pintype "passive"))
      (node (ref "SV49") (pin "9") (pinfunction "9_9") (pintype "passive"))
    )
    (net (code "394") (name "Net-(IC25-Pad9)") (class "Default")
      (node (ref "IC25") (pin "9") (pinfunction "9_9") (pintype "passive"))
      (node (ref "SV50") (pin "1") (pinfunction "1_1") (pintype "passive"))
    )
    (net (code "395") (name "Net-(IC25-Pad10)") (class "Default")
      (node (ref "IC25") (pin "10") (pinfunction "10_10") (pintype "passive"))
      (node (ref "SV50") (pin "2") (pinfunction "2_2") (pintype "passive"))
    )
    (net (code "396") (name "Net-(IC25-Pad11)") (class "Default")
      (node (ref "IC25") (pin "11") (pinfunction "11_11") (pintype "passive"))
      (node (ref "SV50") (pin "3") (pinfunction "3_3") (pintype "passive"))
    )
    (net (code "397") (name "Net-(IC25-Pad12)") (class "Default")
      (node (ref "IC25") (pin "12") (pinfunction "12_12") (pintype "passive"))
      (node (ref "SV50") (pin "4") (pinfunction "4_4") (pintype "passive"))
    )
    (net (code "398") (name "Net-(IC25-Pad13)") (class "Default")
      (node (ref "IC25") (pin "13") (pinfunction "13_13") (pintype "passive"))
      (node (ref "SV50") (pin "5") (pinfunction "5_5") (pintype "passive"))
    )
    (net (code "399") (name "Net-(IC25-Pad14)") (class "Default")
      (node (ref "IC25") (pin "14") (pinfunction "14_14") (pintype "passive"))
      (node (ref "SV50") (pin "6") (pinfunction "6_6") (pintype "passive"))
    )
    (net (code "400") (name "Net-(IC25-Pad15)") (class "Default")
      (node (ref "IC25") (pin "15") (pinfunction "15_15") (pintype "passive"))
      (node (ref "SV50") (pin "7") (pinfunction "7_7") (pintype "passive"))
    )
    (net (code "401") (name "Net-(IC25-Pad16)") (class "Default")
      (node (ref "IC25") (pin "16") (pinfunction "16_16") (pintype "passive"))
      (node (ref "SV50") (pin "8") (pinfunction "8_8") (pintype "passive"))
    )
    (net (code "402") (name "Net-(IC26-Pad1)") (class "Default")
      (node (ref "IC26") (pin "1") (pinfunction "1_1") (pintype "passive"))
      (node (ref "SV51") (pin "2") (pinfunction "2_2") (pintype "passive"))
    )
    (net (code "403") (name "Net-(IC26-Pad2)") (class "Default")
      (node (ref "IC26") (pin "2") (pinfunction "2_2") (pintype "passive"))
      (node (ref "SV51") (pin "3") (pinfunction "3_3") (pintype "passive"))
    )
    (net (code "404") (name "Net-(IC26-Pad3)") (class "Default")
      (node (ref "IC26") (pin "3") (pinfunction "3_3") (pintype "passive"))
      (node (ref "SV51") (pin "4") (pinfunction "4_4") (pintype "passive"))
    )
    (net (code "405") (name "Net-(IC26-Pad4)") (class "Default")
      (node (ref "IC26") (pin "4") (pinfunction "4_4") (pintype "passive"))
      (node (ref "SV51") (pin "5") (pinfunction "5_5") (pintype "passive"))
    )
    (net (code "406") (name "Net-(IC26-Pad5)") (class "Default")
      (node (ref "IC26") (pin "5") (pinfunction "5_5") (pintype "passive"))
      (node (ref "SV51") (pin "6") (pinfunction "6_6") (pintype "passive"))
    )
    (net (code "407") (name "Net-(IC26-Pad6)") (class "Default")
      (node (ref "IC26") (pin "6") (pinfunction "6_6") (pintype "passive"))
      (node (ref "SV51") (pin "7") (pinfunction "7_7") (pintype "passive"))
    )
    (net (code "408") (name "Net-(IC26-Pad7)") (class "Default")
      (node (ref "IC26") (pin "7") (pinfunction "7_7") (pintype "passive"))
      (node (ref "SV51") (pin "8") (pinfunction "8_8") (pintype "passive"))
    )
    (net (code "409") (name "Net-(IC26-Pad8)") (class "Default")
      (node (ref "IC26") (pin "8") (pinfunction "8_8") (pintype "passive"))
      (node (ref "SV51") (pin "9") (pinfunction "9_9") (pintype "passive"))
    )
    (net (code "410") (name "Net-(IC26-Pad9)") (class "Default")
      (node (ref "IC26") (pin "9") (pinfunction "9_9") (pintype "passive"))
      (node (ref "SV52") (pin "1") (pinfunction "1_1") (pintype "passive"))
    )
    (net (code "411") (name "Net-(IC26-Pad10)") (class "Default")
      (node (ref "IC26") (pin "10") (pinfunction "10_10") (pintype "passive"))
      (node (ref "SV52") (pin "2") (pinfunction "2_2") (pintype "passive"))
    )
    (net (code "412") (name "Net-(IC26-Pad11)") (class "Default")
      (node (ref "IC26") (pin "11") (pinfunction "11_11") (pintype "passive"))
      (node (ref "SV52") (pin "3") (pinfunction "3_3") (pintype "passive"))
    )
    (net (code "413") (name "Net-(IC26-Pad12)") (class "Default")
      (node (ref "IC26") (pin "12") (pinfunction "12_12") (pintype "passive"))
      (node (ref "SV52") (pin "4") (pinfunction "4_4") (pintype "passive"))
    )
    (net (code "414") (name "Net-(IC26-Pad13)") (class "Default")
      (node (ref "IC26") (pin "13") (pinfunction "13_13") (pintype "passive"))
      (node (ref "SV52") (pin "5") (pinfunction "5_5") (pintype "passive"))
    )
    (net (code "415") (name "Net-(IC26-Pad14)") (class "Default")
      (node (ref "IC26") (pin "14") (pinfunction "14_14") (pintype "passive"))
      (node (ref "SV52") (pin "6") (pinfunction "6_6") (pintype "passive"))
    )
    (net (code "416") (name "Net-(IC26-Pad15)") (class "Default")
      (node (ref "IC26") (pin "15") (pinfunction "15_15") (pintype "passive"))
      (node (ref "SV52") (pin "7") (pinfunction "7_7") (pintype "passive"))
    )
    (net (code "417") (name "Net-(IC26-Pad16)") (class "Default")
      (node (ref "IC26") (pin "16") (pinfunction "16_16") (pintype "passive"))
      (node (ref "SV52") (pin "8") (pinfunction "8_8") (pintype "passive"))
    )
    (net (code "418") (name "Net-(IC27-Pad1)") (class "Default")
      (node (ref "IC27") (pin "1") (pinfunction "1_1") (pintype "passive"))
      (node (ref "SV53") (pin "2") (pinfunction "2_2") (pintype "passive"))
    )
    (net (code "419") (name "Net-(IC27-Pad2)") (class "Default")
      (node (ref "IC27") (pin "2") (pinfunction "2_2") (pintype "passive"))
      (node (ref "SV53") (pin "3") (pinfunction "3_3") (pintype "passive"))
    )
    (net (code "420") (name "Net-(IC27-Pad3)") (class "Default")
      (node (ref "IC27") (pin "3") (pinfunction "3_3") (pintype "passive"))
      (node (ref "SV53") (pin "4") (pinfunction "4_4") (pintype "passive"))
    )
    (net (code "421") (name "Net-(IC27-Pad4)") (class "Default")
      (node (ref "IC27") (pin "4") (pinfunction "4_4") (pintype "passive"))
      (node (ref "SV53") (pin "5") (pinfunction "5_5") (pintype "passive"))
    )
    (net (code "422") (name "Net-(IC27-Pad5)") (class "Default")
      (node (ref "IC27") (pin "5") (pinfunction "5_5") (pintype "passive"))
      (node (ref "SV53") (pin "6") (pinfunction "6_6") (pintype "passive"))
    )
    (net (code "423") (name "Net-(IC27-Pad6)") (class "Default")
      (node (ref "IC27") (pin "6") (pinfunction "6_6") (pintype "passive"))
      (node (ref "SV53") (pin "7") (pinfunction "7_7") (pintype "passive"))
    )
    (net (code "424") (name "Net-(IC27-Pad7)") (class "Default")
      (node (ref "IC27") (pin "7") (pinfunction "7_7") (pintype "passive"))
      (node (ref "SV53") (pin "8") (pinfunction "8_8") (pintype "passive"))
    )
    (net (code "425") (name "Net-(IC27-Pad8)") (class "Default")
      (node (ref "IC27") (pin "8") (pinfunction "8_8") (pintype "passive"))
      (node (ref "SV53") (pin "9") (pinfunction "9_9") (pintype "passive"))
    )
    (net (code "426") (name "Net-(IC27-Pad9)") (class "Default")
      (node (ref "IC27") (pin "9") (pinfunction "9_9") (pintype "passive"))
      (node (ref "SV54") (pin "1") (pinfunction "1_1") (pintype "passive"))
    )
    (net (code "427") (name "Net-(IC27-Pad10)") (class "Default")
      (node (ref "IC27") (pin "10") (pinfunction "10_10") (pintype "passive"))
      (node (ref "SV54") (pin "2") (pinfunction "2_2") (pintype "passive"))
    )
    (net (code "428") (name "Net-(IC27-Pad11)") (class "Default")
      (node (ref "IC27") (pin "11") (pinfunction "11_11") (pintype "passive"))
      (node (ref "SV54") (pin "3") (pinfunction "3_3") (pintype "passive"))
    )
    (net (code "429") (name "Net-(IC27-Pad12)") (class "Default")
      (node (ref "IC27") (pin "12") (pinfunction "12_12") (pintype "passive"))
      (node (ref "SV54") (pin "4") (pinfunction "4_4") (pintype "passive"))
    )
    (net (code "430") (name "Net-(IC27-Pad13)") (class "Default")
      (node (ref "IC27") (pin "13") (pinfunction "13_13") (pintype "passive"))
      (node (ref "SV54") (pin "5") (pinfunction "5_5") (pintype "passive"))
    )
    (net (code "431") (name "Net-(IC27-Pad14)") (class "Default")
      (node (ref "IC27") (pin "14") (pinfunction "14_14") (pintype "passive"))
      (node (ref "SV54") (pin "6") (pinfunction "6_6") (pintype "passive"))
    )
    (net (code "432") (name "Net-(IC27-Pad15)") (class "Default")
      (node (ref "IC27") (pin "15") (pinfunction "15_15") (pintype "passive"))
      (node (ref "SV54") (pin "7") (pinfunction "7_7") (pintype "passive"))
    )
    (net (code "433") (name "Net-(IC27-Pad16)") (class "Default")
      (node (ref "IC27") (pin "16") (pinfunction "16_16") (pintype "passive"))
      (node (ref "SV54") (pin "8") (pinfunction "8_8") (pintype "passive"))
    )
    (net (code "434") (name "Net-(IC28-Pad1)") (class "Default")
      (node (ref "IC28") (pin "1") (pinfunction "1_1") (pintype "passive"))
      (node (ref "SV55") (pin "2") (pinfunction "2_2") (pintype "passive"))
    )
    (net (code "435") (name "Net-(IC28-Pad2)") (class "Default")
      (node (ref "IC28") (pin "2") (pinfunction "2_2") (pintype "passive"))
      (node (ref "SV55") (pin "3") (pinfunction "3_3") (pintype "passive"))
    )
    (net (code "436") (name "Net-(IC28-Pad3)") (class "Default")
      (node (ref "IC28") (pin "3") (pinfunction "3_3") (pintype "passive"))
      (node (ref "SV55") (pin "4") (pinfunction "4_4") (pintype "passive"))
    )
    (net (code "437") (name "Net-(IC28-Pad4)") (class "Default")
      (node (ref "IC28") (pin "4") (pinfunction "4_4") (pintype "passive"))
      (node (ref "SV55") (pin "5") (pinfunction "5_5") (pintype "passive"))
    )
    (net (code "438") (name "Net-(IC28-Pad5)") (class "Default")
      (node (ref "IC28") (pin "5") (pinfunction "5_5") (pintype "passive"))
      (node (ref "SV55") (pin "6") (pinfunction "6_6") (pintype "passive"))
    )
    (net (code "439") (name "Net-(IC28-Pad6)") (class "Default")
      (node (ref "IC28") (pin "6") (pinfunction "6_6") (pintype "passive"))
      (node (ref "SV55") (pin "7") (pinfunction "7_7") (pintype "passive"))
    )
    (net (code "440") (name "Net-(IC28-Pad7)") (class "Default")
      (node (ref "IC28") (pin "7") (pinfunction "7_7") (pintype "passive"))
      (node (ref "SV55") (pin "8") (pinfunction "8_8") (pintype "passive"))
    )
    (net (code "441") (name "Net-(IC28-Pad8)") (class "Default")
      (node (ref "IC28") (pin "8") (pinfunction "8_8") (pintype "passive"))
      (node (ref "SV55") (pin "9") (pinfunction "9_9") (pintype "passive"))
    )
    (net (code "442") (name "Net-(IC28-Pad9)") (class "Default")
      (node (ref "IC28") (pin "9") (pinfunction "9_9") (pintype "passive"))
      (node (ref "SV56") (pin "1") (pinfunction "1_1") (pintype "passive"))
    )
    (net (code "443") (name "Net-(IC28-Pad10)") (class "Default")
      (node (ref "IC28") (pin "10") (pinfunction "10_10") (pintype "passive"))
      (node (ref "SV56") (pin "2") (pinfunction "2_2") (pintype "passive"))
    )
    (net (code "444") (name "Net-(IC28-Pad11)") (class "Default")
      (node (ref "IC28") (pin "11") (pinfunction "11_11") (pintype "passive"))
      (node (ref "SV56") (pin "3") (pinfunction "3_3") (pintype "passive"))
    )
    (net (code "445") (name "Net-(IC28-Pad12)") (class "Default")
      (node (ref "IC28") (pin "12") (pinfunction "12_12") (pintype "passive"))
      (node (ref "SV56") (pin "4") (pinfunction "4_4") (pintype "passive"))
    )
    (net (code "446") (name "Net-(IC28-Pad13)") (class "Default")
      (node (ref "IC28") (pin "13") (pinfunction "13_13") (pintype "passive"))
      (node (ref "SV56") (pin "5") (pinfunction "5_5") (pintype "passive"))
    )
    (net (code "447") (name "Net-(IC28-Pad14)") (class "Default")
      (node (ref "IC28") (pin "14") (pinfunction "14_14") (pintype "passive"))
      (node (ref "SV56") (pin "6") (pinfunction "6_6") (pintype "passive"))
    )
    (net (code "448") (name "Net-(IC28-Pad15)") (class "Default")
      (node (ref "IC28") (pin "15") (pinfunction "15_15") (pintype "passive"))
      (node (ref "SV56") (pin "7") (pinfunction "7_7") (pintype "passive"))
    )
    (net (code "449") (name "Net-(IC28-Pad16)") (class "Default")
      (node (ref "IC28") (pin "16") (pinfunction "16_16") (pintype "passive"))
      (node (ref "SV56") (pin "8") (pinfunction "8_8") (pintype "passive"))
    )
    (net (code "450") (name "Net-(IC29-Pad1)") (class "Default")
      (node (ref "IC29") (pin "1") (pinfunction "1_1") (pintype "passive"))
      (node (ref "SV57") (pin "2") (pinfunction "2_2") (pintype "passive"))
    )
    (net (code "451") (name "Net-(IC29-Pad2)") (class "Default")
      (node (ref "IC29") (pin "2") (pinfunction "2_2") (pintype "passive"))
      (node (ref "SV57") (pin "3") (pinfunction "3_3") (pintype "passive"))
    )
    (net (code "452") (name "Net-(IC29-Pad3)") (class "Default")
      (node (ref "IC29") (pin "3") (pinfunction "3_3") (pintype "passive"))
      (node (ref "SV57") (pin "4") (pinfunction "4_4") (pintype "passive"))
    )
    (net (code "453") (name "Net-(IC29-Pad4)") (class "Default")
      (node (ref "IC29") (pin "4") (pinfunction "4_4") (pintype "passive"))
      (node (ref "SV57") (pin "5") (pinfunction "5_5") (pintype "passive"))
    )
    (net (code "454") (name "Net-(IC29-Pad5)") (class "Default")
      (node (ref "IC29") (pin "5") (pinfunction "5_5") (pintype "passive"))
      (node (ref "SV57") (pin "6") (pinfunction "6_6") (pintype "passive"))
    )
    (net (code "455") (name "Net-(IC29-Pad6)") (class "Default")
      (node (ref "IC29") (pin "6") (pinfunction "6_6") (pintype "passive"))
      (node (ref "SV57") (pin "7") (pinfunction "7_7") (pintype "passive"))
    )
    (net (code "456") (name "Net-(IC29-Pad7)") (class "Default")
      (node (ref "IC29") (pin "7") (pinfunction "7_7") (pintype "passive"))
      (node (ref "SV57") (pin "8") (pinfunction "8_8") (pintype "passive"))
    )
    (net (code "457") (name "Net-(IC29-Pad8)") (class "Default")
      (node (ref "IC29") (pin "8") (pinfunction "8_8") (pintype "passive"))
      (node (ref "SV57") (pin "9") (pinfunction "9_9") (pintype "passive"))
    )
    (net (code "458") (name "Net-(IC29-Pad9)") (class "Default")
      (node (ref "IC29") (pin "9") (pinfunction "9_9") (pintype "passive"))
      (node (ref "SV58") (pin "1") (pinfunction "1_1") (pintype "passive"))
    )
    (net (code "459") (name "Net-(IC29-Pad10)") (class "Default")
      (node (ref "IC29") (pin "10") (pinfunction "10_10") (pintype "passive"))
      (node (ref "SV58") (pin "2") (pinfunction "2_2") (pintype "passive"))
    )
    (net (code "460") (name "Net-(IC29-Pad11)") (class "Default")
      (node (ref "IC29") (pin "11") (pinfunction "11_11") (pintype "passive"))
      (node (ref "SV58") (pin "3") (pinfunction "3_3") (pintype "passive"))
    )
    (net (code "461") (name "Net-(IC29-Pad12)") (class "Default")
      (node (ref "IC29") (pin "12") (pinfunction "12_12") (pintype "passive"))
      (node (ref "SV58") (pin "4") (pinfunction "4_4") (pintype "passive"))
    )
    (net (code "462") (name "Net-(IC29-Pad13)") (class "Default")
      (node (ref "IC29") (pin "13") (pinfunction "13_13") (pintype "passive"))
      (node (ref "SV58") (pin "5") (pinfunction "5_5") (pintype "passive"))
    )
    (net (code "463") (name "Net-(IC29-Pad14)") (class "Default")
      (node (ref "IC29") (pin "14") (pinfunction "14_14") (pintype "passive"))
      (node (ref "SV58") (pin "6") (pinfunction "6_6") (pintype "passive"))
    )
    (net (code "464") (name "Net-(IC29-Pad15)") (class "Default")
      (node (ref "IC29") (pin "15") (pinfunction "15_15") (pintype "passive"))
      (node (ref "SV58") (pin "7") (pinfunction "7_7") (pintype "passive"))
    )
    (net (code "465") (name "Net-(IC29-Pad16)") (class "Default")
      (node (ref "IC29") (pin "16") (pinfunction "16_16") (pintype "passive"))
      (node (ref "SV58") (pin "8") (pinfunction "8_8") (pintype "passive"))
    )
    (net (code "466") (name "Net-(IC30-Pad1)") (class "Default")
      (node (ref "IC30") (pin "1") (pinfunction "1_1") (pintype "passive"))
      (node (ref "SV59") (pin "2") (pinfunction "2_2") (pintype "passive"))
    )
    (net (code "467") (name "Net-(IC30-Pad2)") (class "Default")
      (node (ref "IC30") (pin "2") (pinfunction "2_2") (pintype "passive"))
      (node (ref "SV59") (pin "3") (pinfunction "3_3") (pintype "passive"))
    )
    (net (code "468") (name "Net-(IC30-Pad3)") (class "Default")
      (node (ref "IC30") (pin "3") (pinfunction "3_3") (pintype "passive"))
      (node (ref "SV59") (pin "4") (pinfunction "4_4") (pintype "passive"))
    )
    (net (code "469") (name "Net-(IC30-Pad4)") (class "Default")
      (node (ref "IC30") (pin "4") (pinfunction "4_4") (pintype "passive"))
      (node (ref "SV59") (pin "5") (pinfunction "5_5") (pintype "passive"))
    )
    (net (code "470") (name "Net-(IC30-Pad5)") (class "Default")
      (node (ref "IC30") (pin "5") (pinfunction "5_5") (pintype "passive"))
      (node (ref "SV59") (pin "6") (pinfunction "6_6") (pintype "passive"))
    )
    (net (code "471") (name "Net-(IC30-Pad6)") (class "Default")
      (node (ref "IC30") (pin "6") (pinfunction "6_6") (pintype "passive"))
      (node (ref "SV59") (pin "7") (pinfunction "7_7") (pintype "passive"))
    )
    (net (code "472") (name "Net-(IC30-Pad7)") (class "Default")
      (node (ref "IC30") (pin "7") (pinfunction "7_7") (pintype "passive"))
      (node (ref "SV59") (pin "8") (pinfunction "8_8") (pintype "passive"))
    )
    (net (code "473") (name "Net-(IC30-Pad8)") (class "Default")
      (node (ref "IC30") (pin "8") (pinfunction "8_8") (pintype "passive"))
      (node (ref "SV59") (pin "9") (pinfunction "9_9") (pintype "passive"))
    )
    (net (code "474") (name "Net-(IC30-Pad9)") (class "Default")
      (node (ref "IC30") (pin "9") (pinfunction "9_9") (pintype "passive"))
      (node (ref "SV60") (pin "1") (pinfunction "1_1") (pintype "passive"))
    )
    (net (code "475") (name "Net-(IC30-Pad10)") (class "Default")
      (node (ref "IC30") (pin "10") (pinfunction "10_10") (pintype "passive"))
      (node (ref "SV60") (pin "2") (pinfunction "2_2") (pintype "passive"))
    )
    (net (code "476") (name "Net-(IC30-Pad11)") (class "Default")
      (node (ref "IC30") (pin "11") (pinfunction "11_11") (pintype "passive"))
      (node (ref "SV60") (pin "3") (pinfunction "3_3") (pintype "passive"))
    )
    (net (code "477") (name "Net-(IC30-Pad12)") (class "Default")
      (node (ref "IC30") (pin "12") (pinfunction "12_12") (pintype "passive"))
      (node (ref "SV60") (pin "4") (pinfunction "4_4") (pintype "passive"))
    )
    (net (code "478") (name "Net-(IC30-Pad13)") (class "Default")
      (node (ref "IC30") (pin "13") (pinfunction "13_13") (pintype "passive"))
      (node (ref "SV60") (pin "5") (pinfunction "5_5") (pintype "passive"))
    )
    (net (code "479") (name "Net-(IC30-Pad14)") (class "Default")
      (node (ref "IC30") (pin "14") (pinfunction "14_14") (pintype "passive"))
      (node (ref "SV60") (pin "6") (pinfunction "6_6") (pintype "passive"))
    )
    (net (code "480") (name "Net-(IC30-Pad15)") (class "Default")
      (node (ref "IC30") (pin "15") (pinfunction "15_15") (pintype "passive"))
      (node (ref "SV60") (pin "7") (pinfunction "7_7") (pintype "passive"))
    )
    (net (code "481") (name "Net-(IC30-Pad16)") (class "Default")
      (node (ref "IC30") (pin "16") (pinfunction "16_16") (pintype "passive"))
      (node (ref "SV60") (pin "8") (pinfunction "8_8") (pintype "passive"))
    )
    (net (code "482") (name "Net-(IC31-Pad1)") (class "Default")
      (node (ref "IC31") (pin "1") (pinfunction "1_1") (pintype "passive"))
      (node (ref "IC39") (pin "1") (pinfunction "1_1") (pintype "passive"))
      (node (ref "SV61") (pin "2") (pinfunction "2_2") (pintype "passive"))
    )
    (net (code "483") (name "Net-(IC31-Pad2)") (class "Default")
      (node (ref "IC31") (pin "2") (pinfunction "2_2") (pintype "passive"))
      (node (ref "IC39") (pin "2") (pinfunction "2_2") (pintype "passive"))
      (node (ref "SV61") (pin "3") (pinfunction "3_3") (pintype "passive"))
    )
    (net (code "484") (name "Net-(IC31-Pad3)") (class "Default")
      (node (ref "IC31") (pin "3") (pinfunction "3_3") (pintype "passive"))
      (node (ref "IC39") (pin "3") (pinfunction "3_3") (pintype "passive"))
      (node (ref "SV61") (pin "4") (pinfunction "4_4") (pintype "passive"))
    )
    (net (code "485") (name "Net-(IC31-Pad4)") (class "Default")
      (node (ref "IC31") (pin "4") (pinfunction "4_4") (pintype "passive"))
      (node (ref "IC39") (pin "4") (pinfunction "4_4") (pintype "passive"))
      (node (ref "SV61") (pin "5") (pinfunction "5_5") (pintype "passive"))
    )
    (net (code "486") (name "Net-(IC31-Pad5)") (class "Default")
      (node (ref "IC31") (pin "5") (pinfunction "5_5") (pintype "passive"))
      (node (ref "IC39") (pin "5") (pinfunction "5_5") (pintype "passive"))
      (node (ref "SV61") (pin "6") (pinfunction "6_6") (pintype "passive"))
    )
    (net (code "487") (name "Net-(IC31-Pad6)") (class "Default")
      (node (ref "IC31") (pin "6") (pinfunction "6_6") (pintype "passive"))
      (node (ref "IC39") (pin "6") (pinfunction "6_6") (pintype "passive"))
      (node (ref "SV61") (pin "7") (pinfunction "7_7") (pintype "passive"))
    )
    (net (code "488") (name "Net-(IC31-Pad7)") (class "Default")
      (node (ref "IC31") (pin "7") (pinfunction "7_7") (pintype "passive"))
      (node (ref "IC39") (pin "7") (pinfunction "7_7") (pintype "passive"))
      (node (ref "SV61") (pin "8") (pinfunction "8_8") (pintype "passive"))
    )
    (net (code "489") (name "Net-(IC31-Pad8)") (class "Default")
      (node (ref "IC31") (pin "8") (pinfunction "8_8") (pintype "passive"))
      (node (ref "IC39") (pin "8") (pinfunction "8_8") (pintype "passive"))
      (node (ref "SV61") (pin "9") (pinfunction "9_9") (pintype "passive"))
    )
    (net (code "490") (name "Net-(IC31-Pad9)") (class "Default")
      (node (ref "IC31") (pin "9") (pinfunction "9_9") (pintype "passive"))
      (node (ref "IC39") (pin "9") (pinfunction "9_9") (pintype "passive"))
      (node (ref "SV61") (pin "10") (pinfunction "10_10") (pintype "passive"))
    )
    (net (code "491") (name "Net-(IC31-Pad10)") (class "Default")
      (node (ref "IC31") (pin "10") (pinfunction "10_10") (pintype "passive"))
      (node (ref "IC39") (pin "10") (pinfunction "10_10") (pintype "passive"))
      (node (ref "SV61") (pin "11") (pinfunction "11_11") (pintype "passive"))
    )
    (net (code "492") (name "Net-(IC31-Pad11)") (class "Default")
      (node (ref "IC31") (pin "11") (pinfunction "11_11") (pintype "passive"))
      (node (ref "IC39") (pin "11") (pinfunction "11_11") (pintype "passive"))
      (node (ref "SV61") (pin "12") (pinfunction "12_12") (pintype "passive"))
    )
    (net (code "493") (name "Net-(IC31-Pad12)") (class "Default")
      (node (ref "IC31") (pin "12") (pinfunction "12_12") (pintype "passive"))
      (node (ref "IC39") (pin "12") (pinfunction "12_12") (pintype "passive"))
      (node (ref "SV61") (pin "13") (pinfunction "13_13") (pintype "passive"))
    )
    (net (code "494") (name "Net-(IC31-Pad13)") (class "Default")
      (node (ref "IC31") (pin "13") (pinfunction "13_13") (pintype "passive"))
      (node (ref "IC39") (pin "13") (pinfunction "13_13") (pintype "passive"))
      (node (ref "SV62") (pin "1") (pinfunction "1_1") (pintype "passive"))
    )
    (net (code "495") (name "Net-(IC31-Pad14)") (class "Default")
      (node (ref "IC31") (pin "14") (pinfunction "14_14") (pintype "passive"))
      (node (ref "IC39") (pin "14") (pinfunction "14_14") (pintype "passive"))
      (node (ref "SV62") (pin "2") (pinfunction "2_2") (pintype "passive"))
    )
    (net (code "496") (name "Net-(IC31-Pad15)") (class "Default")
      (node (ref "IC31") (pin "15") (pinfunction "15_15") (pintype "passive"))
      (node (ref "IC39") (pin "15") (pinfunction "15_15") (pintype "passive"))
      (node (ref "SV62") (pin "3") (pinfunction "3_3") (pintype "passive"))
    )
    (net (code "497") (name "Net-(IC31-Pad16)") (class "Default")
      (node (ref "IC31") (pin "16") (pinfunction "16_16") (pintype "passive"))
      (node (ref "IC39") (pin "16") (pinfunction "16_16") (pintype "passive"))
      (node (ref "SV62") (pin "4") (pinfunction "4_4") (pintype "passive"))
    )
    (net (code "498") (name "Net-(IC31-Pad17)") (class "Default")
      (node (ref "IC31") (pin "17") (pinfunction "17_17") (pintype "passive"))
      (node (ref "IC39") (pin "17") (pinfunction "17_17") (pintype "passive"))
      (node (ref "SV62") (pin "5") (pinfunction "5_5") (pintype "passive"))
    )
    (net (code "499") (name "Net-(IC31-Pad18)") (class "Default")
      (node (ref "IC31") (pin "18") (pinfunction "18_18") (pintype "passive"))
      (node (ref "IC39") (pin "18") (pinfunction "18_18") (pintype "passive"))
      (node (ref "SV62") (pin "6") (pinfunction "6_6") (pintype "passive"))
    )
    (net (code "500") (name "Net-(IC31-Pad19)") (class "Default")
      (node (ref "IC31") (pin "19") (pinfunction "19_19") (pintype "passive"))
      (node (ref "IC39") (pin "19") (pinfunction "19_19") (pintype "passive"))
      (node (ref "SV62") (pin "7") (pinfunction "7_7") (pintype "passive"))
    )
    (net (code "501") (name "Net-(IC31-Pad20)") (class "Default")
      (node (ref "IC31") (pin "20") (pinfunction "20_20") (pintype "passive"))
      (node (ref "IC39") (pin "20") (pinfunction "20_20") (pintype "passive"))
      (node (ref "SV62") (pin "8") (pinfunction "8_8") (pintype "passive"))
    )
    (net (code "502") (name "Net-(IC31-Pad21)") (class "Default")
      (node (ref "IC31") (pin "21") (pinfunction "21_21") (pintype "passive"))
      (node (ref "IC39") (pin "21") (pinfunction "21_21") (pintype "passive"))
      (node (ref "SV62") (pin "9") (pinfunction "9_9") (pintype "passive"))
    )
    (net (code "503") (name "Net-(IC31-Pad22)") (class "Default")
      (node (ref "IC31") (pin "22") (pinfunction "22_22") (pintype "passive"))
      (node (ref "IC39") (pin "22") (pinfunction "22_22") (pintype "passive"))
      (node (ref "SV62") (pin "10") (pinfunction "10_10") (pintype "passive"))
    )
    (net (code "504") (name "Net-(IC31-Pad23)") (class "Default")
      (node (ref "IC31") (pin "23") (pinfunction "23_23") (pintype "passive"))
      (node (ref "IC39") (pin "23") (pinfunction "23_23") (pintype "passive"))
      (node (ref "SV62") (pin "11") (pinfunction "11_11") (pintype "passive"))
    )
    (net (code "505") (name "Net-(IC31-Pad24)") (class "Default")
      (node (ref "IC31") (pin "24") (pinfunction "24_24") (pintype "passive"))
      (node (ref "IC39") (pin "24") (pinfunction "24_24") (pintype "passive"))
      (node (ref "SV62") (pin "12") (pinfunction "12_12") (pintype "passive"))
    )
    (net (code "506") (name "Net-(IC32-Pad1)") (class "Default")
      (node (ref "IC32") (pin "1") (pinfunction "1_1") (pintype "passive"))
      (node (ref "IC40") (pin "1") (pinfunction "1_1") (pintype "passive"))
      (node (ref "SV63") (pin "2") (pinfunction "2_2") (pintype "passive"))
    )
    (net (code "507") (name "Net-(IC32-Pad2)") (class "Default")
      (node (ref "IC32") (pin "2") (pinfunction "2_2") (pintype "passive"))
      (node (ref "IC40") (pin "2") (pinfunction "2_2") (pintype "passive"))
      (node (ref "SV63") (pin "3") (pinfunction "3_3") (pintype "passive"))
    )
    (net (code "508") (name "Net-(IC32-Pad3)") (class "Default")
      (node (ref "IC32") (pin "3") (pinfunction "3_3") (pintype "passive"))
      (node (ref "IC40") (pin "3") (pinfunction "3_3") (pintype "passive"))
      (node (ref "SV63") (pin "4") (pinfunction "4_4") (pintype "passive"))
    )
    (net (code "509") (name "Net-(IC32-Pad4)") (class "Default")
      (node (ref "IC32") (pin "4") (pinfunction "4_4") (pintype "passive"))
      (node (ref "IC40") (pin "4") (pinfunction "4_4") (pintype "passive"))
      (node (ref "SV63") (pin "5") (pinfunction "5_5") (pintype "passive"))
    )
    (net (code "510") (name "Net-(IC32-Pad5)") (class "Default")
      (node (ref "IC32") (pin "5") (pinfunction "5_5") (pintype "passive"))
      (node (ref "IC40") (pin "5") (pinfunction "5_5") (pintype "passive"))
      (node (ref "SV63") (pin "6") (pinfunction "6_6") (pintype "passive"))
    )
    (net (code "511") (name "Net-(IC32-Pad6)") (class "Default")
      (node (ref "IC32") (pin "6") (pinfunction "6_6") (pintype "passive"))
      (node (ref "IC40") (pin "6") (pinfunction "6_6") (pintype "passive"))
      (node (ref "SV63") (pin "7") (pinfunction "7_7") (pintype "passive"))
    )
    (net (code "512") (name "Net-(IC32-Pad7)") (class "Default")
      (node (ref "IC32") (pin "7") (pinfunction "7_7") (pintype "passive"))
      (node (ref "IC40") (pin "7") (pinfunction "7_7") (pintype "passive"))
      (node (ref "SV63") (pin "8") (pinfunction "8_8") (pintype "passive"))
    )
    (net (code "513") (name "Net-(IC32-Pad8)") (class "Default")
      (node (ref "IC32") (pin "8") (pinfunction "8_8") (pintype "passive"))
      (node (ref "IC40") (pin "8") (pinfunction "8_8") (pintype "passive"))
      (node (ref "SV63") (pin "9") (pinfunction "9_9") (pintype "passive"))
    )
    (net (code "514") (name "Net-(IC32-Pad9)") (class "Default")
      (node (ref "IC32") (pin "9") (pinfunction "9_9") (pintype "passive"))
      (node (ref "IC40") (pin "9") (pinfunction "9_9") (pintype "passive"))
      (node (ref "SV63") (pin "10") (pinfunction "10_10") (pintype "passive"))
    )
    (net (code "515") (name "Net-(IC32-Pad10)") (class "Default")
      (node (ref "IC32") (pin "10") (pinfunction "10_10") (pintype "passive"))
      (node (ref "IC40") (pin "10") (pinfunction "10_10") (pintype "passive"))
      (node (ref "SV63") (pin "11") (pinfunction "11_11") (pintype "passive"))
    )
    (net (code "516") (name "Net-(IC32-Pad11)") (class "Default")
      (node (ref "IC32") (pin "11") (pinfunction "11_11") (pintype "passive"))
      (node (ref "IC40") (pin "11") (pinfunction "11_11") (pintype "passive"))
      (node (ref "SV63") (pin "12") (pinfunction "12_12") (pintype "passive"))
    )
    (net (code "517") (name "Net-(IC32-Pad12)") (class "Default")
      (node (ref "IC32") (pin "12") (pinfunction "12_12") (pintype "passive"))
      (node (ref "IC40") (pin "12") (pinfunction "12_12") (pintype "passive"))
      (node (ref "SV63") (pin "13") (pinfunction "13_13") (pintype "passive"))
    )
    (net (code "518") (name "Net-(IC32-Pad13)") (class "Default")
      (node (ref "IC32") (pin "13") (pinfunction "13_13") (pintype "passive"))
      (node (ref "IC40") (pin "13") (pinfunction "13_13") (pintype "passive"))
      (node (ref "SV64") (pin "1") (pinfunction "1_1") (pintype "passive"))
    )
    (net (code "519") (name "Net-(IC32-Pad14)") (class "Default")
      (node (ref "IC32") (pin "14") (pinfunction "14_14") (pintype "passive"))
      (node (ref "IC40") (pin "14") (pinfunction "14_14") (pintype "passive"))
      (node (ref "SV64") (pin "2") (pinfunction "2_2") (pintype "passive"))
    )
    (net (code "520") (name "Net-(IC32-Pad15)") (class "Default")
      (node (ref "IC32") (pin "15") (pinfunction "15_15") (pintype "passive"))
      (node (ref "IC40") (pin "15") (pinfunction "15_15") (pintype "passive"))
      (node (ref "SV64") (pin "3") (pinfunction "3_3") (pintype "passive"))
    )
    (net (code "521") (name "Net-(IC32-Pad16)") (class "Default")
      (node (ref "IC32") (pin "16") (pinfunction "16_16") (pintype "passive"))
      (node (ref "IC40") (pin "16") (pinfunction "16_16") (pintype "passive"))
      (node (ref "SV64") (pin "4") (pinfunction "4_4") (pintype "passive"))
    )
    (net (code "522") (name "Net-(IC32-Pad17)") (class "Default")
      (node (ref "IC32") (pin "17") (pinfunction "17_17") (pintype "passive"))
      (node (ref "IC40") (pin "17") (pinfunction "17_17") (pintype "passive"))
      (node (ref "SV64") (pin "5") (pinfunction "5_5") (pintype "passive"))
    )
    (net (code "523") (name "Net-(IC32-Pad18)") (class "Default")
      (node (ref "IC32") (pin "18") (pinfunction "18_18") (pintype "passive"))
      (node (ref "IC40") (pin "18") (pinfunction "18_18") (pintype "passive"))
      (node (ref "SV64") (pin "6") (pinfunction "6_6") (pintype "passive"))
    )
    (net (code "524") (name "Net-(IC32-Pad19)") (class "Default")
      (node (ref "IC32") (pin "19") (pinfunction "19_19") (pintype "passive"))
      (node (ref "IC40") (pin "19") (pinfunction "19_19") (pintype "passive"))
      (node (ref "SV64") (pin "7") (pinfunction "7_7") (pintype "passive"))
    )
    (net (code "525") (name "Net-(IC32-Pad20)") (class "Default")
      (node (ref "IC32") (pin "20") (pinfunction "20_20") (pintype "passive"))
      (node (ref "IC40") (pin "20") (pinfunction "20_20") (pintype "passive"))
      (node (ref "SV64") (pin "8") (pinfunction "8_8") (pintype "passive"))
    )
    (net (code "526") (name "Net-(IC32-Pad21)") (class "Default")
      (node (ref "IC32") (pin "21") (pinfunction "21_21") (pintype "passive"))
      (node (ref "IC40") (pin "21") (pinfunction "21_21") (pintype "passive"))
      (node (ref "SV64") (pin "9") (pinfunction "9_9") (pintype "passive"))
    )
    (net (code "527") (name "Net-(IC32-Pad22)") (class "Default")
      (node (ref "IC32") (pin "22") (pinfunction "22_22") (pintype "passive"))
      (node (ref "IC40") (pin "22") (pinfunction "22_22") (pintype "passive"))
      (node (ref "SV64") (pin "10") (pinfunction "10_10") (pintype "passive"))
    )
    (net (code "528") (name "Net-(IC32-Pad23)") (class "Default")
      (node (ref "IC32") (pin "23") (pinfunction "23_23") (pintype "passive"))
      (node (ref "IC40") (pin "23") (pinfunction "23_23") (pintype "passive"))
      (node (ref "SV64") (pin "11") (pinfunction "11_11") (pintype "passive"))
    )
    (net (code "529") (name "Net-(IC32-Pad24)") (class "Default")
      (node (ref "IC32") (pin "24") (pinfunction "24_24") (pintype "passive"))
      (node (ref "IC40") (pin "24") (pinfunction "24_24") (pintype "passive"))
      (node (ref "SV64") (pin "12") (pinfunction "12_12") (pintype "passive"))
    )
    (net (code "530") (name "Net-(IC33-Pad1)") (class "Default")
      (node (ref "IC33") (pin "1") (pinfunction "1_1") (pintype "passive"))
      (node (ref "IC41") (pin "1") (pinfunction "1_1") (pintype "passive"))
      (node (ref "SV65") (pin "2") (pinfunction "2_2") (pintype "passive"))
    )
    (net (code "531") (name "Net-(IC33-Pad2)") (class "Default")
      (node (ref "IC33") (pin "2") (pinfunction "2_2") (pintype "passive"))
      (node (ref "IC41") (pin "2") (pinfunction "2_2") (pintype "passive"))
      (node (ref "SV65") (pin "3") (pinfunction "3_3") (pintype "passive"))
    )
    (net (code "532") (name "Net-(IC33-Pad3)") (class "Default")
      (node (ref "IC33") (pin "3") (pinfunction "3_3") (pintype "passive"))
      (node (ref "IC41") (pin "3") (pinfunction "3_3") (pintype "passive"))
      (node (ref "SV65") (pin "4") (pinfunction "4_4") (pintype "passive"))
    )
    (net (code "533") (name "Net-(IC33-Pad4)") (class "Default")
      (node (ref "IC33") (pin "4") (pinfunction "4_4") (pintype "passive"))
      (node (ref "IC41") (pin "4") (pinfunction "4_4") (pintype "passive"))
      (node (ref "SV65") (pin "5") (pinfunction "5_5") (pintype "passive"))
    )
    (net (code "534") (name "Net-(IC33-Pad5)") (class "Default")
      (node (ref "IC33") (pin "5") (pinfunction "5_5") (pintype "passive"))
      (node (ref "IC41") (pin "5") (pinfunction "5_5") (pintype "passive"))
      (node (ref "SV65") (pin "6") (pinfunction "6_6") (pintype "passive"))
    )
    (net (code "535") (name "Net-(IC33-Pad6)") (class "Default")
      (node (ref "IC33") (pin "6") (pinfunction "6_6") (pintype "passive"))
      (node (ref "IC41") (pin "6") (pinfunction "6_6") (pintype "passive"))
      (node (ref "SV65") (pin "7") (pinfunction "7_7") (pintype "passive"))
    )
    (net (code "536") (name "Net-(IC33-Pad7)") (class "Default")
      (node (ref "IC33") (pin "7") (pinfunction "7_7") (pintype "passive"))
      (node (ref "IC41") (pin "7") (pinfunction "7_7") (pintype "passive"))
      (node (ref "SV65") (pin "8") (pinfunction "8_8") (pintype "passive"))
    )
    (net (code "537") (name "Net-(IC33-Pad8)") (class "Default")
      (node (ref "IC33") (pin "8") (pinfunction "8_8") (pintype "passive"))
      (node (ref "IC41") (pin "8") (pinfunction "8_8") (pintype "passive"))
      (node (ref "SV65") (pin "9") (pinfunction "9_9") (pintype "passive"))
    )
    (net (code "538") (name "Net-(IC33-Pad9)") (class "Default")
      (node (ref "IC33") (pin "9") (pinfunction "9_9") (pintype "passive"))
      (node (ref "IC41") (pin "9") (pinfunction "9_9") (pintype "passive"))
      (node (ref "SV65") (pin "10") (pinfunction "10_10") (pintype "passive"))
    )
    (net (code "539") (name "Net-(IC33-Pad10)") (class "Default")
      (node (ref "IC33") (pin "10") (pinfunction "10_10") (pintype "passive"))
      (node (ref "IC41") (pin "10") (pinfunction "10_10") (pintype "passive"))
      (node (ref "SV65") (pin "11") (pinfunction "11_11") (pintype "passive"))
    )
    (net (code "540") (name "Net-(IC33-Pad11)") (class "Default")
      (node (ref "IC33") (pin "11") (pinfunction "11_11") (pintype "passive"))
      (node (ref "IC41") (pin "11") (pinfunction "11_11") (pintype "passive"))
      (node (ref "SV65") (pin "12") (pinfunction "12_12") (pintype "passive"))
    )
    (net (code "541") (name "Net-(IC33-Pad12)") (class "Default")
      (node (ref "IC33") (pin "12") (pinfunction "12_12") (pintype "passive"))
      (node (ref "IC41") (pin "12") (pinfunction "12_12") (pintype "passive"))
      (node (ref "SV65") (pin "13") (pinfunction "13_13") (pintype "passive"))
    )
    (net (code "542") (name "Net-(IC33-Pad13)") (class "Default")
      (node (ref "IC33") (pin "13") (pinfunction "13_13") (pintype "passive"))
      (node (ref "IC41") (pin "13") (pinfunction "13_13") (pintype "passive"))
      (node (ref "SV66") (pin "1") (pinfunction "1_1") (pintype "passive"))
    )
    (net (code "543") (name "Net-(IC33-Pad14)") (class "Default")
      (node (ref "IC33") (pin "14") (pinfunction "14_14") (pintype "passive"))
      (node (ref "IC41") (pin "14") (pinfunction "14_14") (pintype "passive"))
      (node (ref "SV66") (pin "2") (pinfunction "2_2") (pintype "passive"))
    )
    (net (code "544") (name "Net-(IC33-Pad15)") (class "Default")
      (node (ref "IC33") (pin "15") (pinfunction "15_15") (pintype "passive"))
      (node (ref "IC41") (pin "15") (pinfunction "15_15") (pintype "passive"))
      (node (ref "SV66") (pin "3") (pinfunction "3_3") (pintype "passive"))
    )
    (net (code "545") (name "Net-(IC33-Pad16)") (class "Default")
      (node (ref "IC33") (pin "16") (pinfunction "16_16") (pintype "passive"))
      (node (ref "IC41") (pin "16") (pinfunction "16_16") (pintype "passive"))
      (node (ref "SV66") (pin "4") (pinfunction "4_4") (pintype "passive"))
    )
    (net (code "546") (name "Net-(IC33-Pad17)") (class "Default")
      (node (ref "IC33") (pin "17") (pinfunction "17_17") (pintype "passive"))
      (node (ref "IC41") (pin "17") (pinfunction "17_17") (pintype "passive"))
      (node (ref "SV66") (pin "5") (pinfunction "5_5") (pintype "passive"))
    )
    (net (code "547") (name "Net-(IC33-Pad18)") (class "Default")
      (node (ref "IC33") (pin "18") (pinfunction "18_18") (pintype "passive"))
      (node (ref "IC41") (pin "18") (pinfunction "18_18") (pintype "passive"))
      (node (ref "SV66") (pin "6") (pinfunction "6_6") (pintype "passive"))
    )
    (net (code "548") (name "Net-(IC33-Pad19)") (class "Default")
      (node (ref "IC33") (pin "19") (pinfunction "19_19") (pintype "passive"))
      (node (ref "IC41") (pin "19") (pinfunction "19_19") (pintype "passive"))
      (node (ref "SV66") (pin "7") (pinfunction "7_7") (pintype "passive"))
    )
    (net (code "549") (name "Net-(IC33-Pad20)") (class "Default")
      (node (ref "IC33") (pin "20") (pinfunction "20_20") (pintype "passive"))
      (node (ref "IC41") (pin "20") (pinfunction "20_20") (pintype "passive"))
      (node (ref "SV66") (pin "8") (pinfunction "8_8") (pintype "passive"))
    )
    (net (code "550") (name "Net-(IC33-Pad21)") (class "Default")
      (node (ref "IC33") (pin "21") (pinfunction "21_21") (pintype "passive"))
      (node (ref "IC41") (pin "21") (pinfunction "21_21") (pintype "passive"))
      (node (ref "SV66") (pin "9") (pinfunction "9_9") (pintype "passive"))
    )
    (net (code "551") (name "Net-(IC33-Pad22)") (class "Default")
      (node (ref "IC33") (pin "22") (pinfunction "22_22") (pintype "passive"))
      (node (ref "IC41") (pin "22") (pinfunction "22_22") (pintype "passive"))
      (node (ref "SV66") (pin "10") (pinfunction "10_10") (pintype "passive"))
    )
    (net (code "552") (name "Net-(IC33-Pad23)") (class "Default")
      (node (ref "IC33") (pin "23") (pinfunction "23_23") (pintype "passive"))
      (node (ref "IC41") (pin "23") (pinfunction "23_23") (pintype "passive"))
      (node (ref "SV66") (pin "11") (pinfunction "11_11") (pintype "passive"))
    )
    (net (code "553") (name "Net-(IC33-Pad24)") (class "Default")
      (node (ref "IC33") (pin "24") (pinfunction "24_24") (pintype "passive"))
      (node (ref "IC41") (pin "24") (pinfunction "24_24") (pintype "passive"))
      (node (ref "SV66") (pin "12") (pinfunction "12_12") (pintype "passive"))
    )
    (net (code "554") (name "Net-(IC34-Pad1)") (class "Default")
      (node (ref "IC34") (pin "1") (pinfunction "1_1") (pintype "passive"))
      (node (ref "IC42") (pin "1") (pinfunction "1_1") (pintype "passive"))
      (node (ref "SV67") (pin "2") (pinfunction "2_2") (pintype "passive"))
    )
    (net (code "555") (name "Net-(IC34-Pad2)") (class "Default")
      (node (ref "IC34") (pin "2") (pinfunction "2_2") (pintype "passive"))
      (node (ref "IC42") (pin "2") (pinfunction "2_2") (pintype "passive"))
      (node (ref "SV67") (pin "3") (pinfunction "3_3") (pintype "passive"))
    )
    (net (code "556") (name "Net-(IC34-Pad3)") (class "Default")
      (node (ref "IC34") (pin "3") (pinfunction "3_3") (pintype "passive"))
      (node (ref "IC42") (pin "3") (pinfunction "3_3") (pintype "passive"))
      (node (ref "SV67") (pin "4") (pinfunction "4_4") (pintype "passive"))
    )
    (net (code "557") (name "Net-(IC34-Pad4)") (class "Default")
      (node (ref "IC34") (pin "4") (pinfunction "4_4") (pintype "passive"))
      (node (ref "IC42") (pin "4") (pinfunction "4_4") (pintype "passive"))
      (node (ref "SV67") (pin "5") (pinfunction "5_5") (pintype "passive"))
    )
    (net (code "558") (name "Net-(IC34-Pad5)") (class "Default")
      (node (ref "IC34") (pin "5") (pinfunction "5_5") (pintype "passive"))
      (node (ref "IC42") (pin "5") (pinfunction "5_5") (pintype "passive"))
      (node (ref "SV67") (pin "6") (pinfunction "6_6") (pintype "passive"))
    )
    (net (code "559") (name "Net-(IC34-Pad6)") (class "Default")
      (node (ref "IC34") (pin "6") (pinfunction "6_6") (pintype "passive"))
      (node (ref "IC42") (pin "6") (pinfunction "6_6") (pintype "passive"))
      (node (ref "SV67") (pin "7") (pinfunction "7_7") (pintype "passive"))
    )
    (net (code "560") (name "Net-(IC34-Pad7)") (class "Default")
      (node (ref "IC34") (pin "7") (pinfunction "7_7") (pintype "passive"))
      (node (ref "IC42") (pin "7") (pinfunction "7_7") (pintype "passive"))
      (node (ref "SV67") (pin "8") (pinfunction "8_8") (pintype "passive"))
    )
    (net (code "561") (name "Net-(IC34-Pad8)") (class "Default")
      (node (ref "IC34") (pin "8") (pinfunction "8_8") (pintype "passive"))
      (node (ref "IC42") (pin "8") (pinfunction "8_8") (pintype "passive"))
      (node (ref "SV67") (pin "9") (pinfunction "9_9") (pintype "passive"))
    )
    (net (code "562") (name "Net-(IC34-Pad9)") (class "Default")
      (node (ref "IC34") (pin "9") (pinfunction "9_9") (pintype "passive"))
      (node (ref "IC42") (pin "9") (pinfunction "9_9") (pintype "passive"))
      (node (ref "SV67") (pin "10") (pinfunction "10_10") (pintype "passive"))
    )
    (net (code "563") (name "Net-(IC34-Pad10)") (class "Default")
      (node (ref "IC34") (pin "10") (pinfunction "10_10") (pintype "passive"))
      (node (ref "IC42") (pin "10") (pinfunction "10_10") (pintype "passive"))
      (node (ref "SV67") (pin "11") (pinfunction "11_11") (pintype "passive"))
    )
    (net (code "564") (name "Net-(IC34-Pad11)") (class "Default")
      (node (ref "IC34") (pin "11") (pinfunction "11_11") (pintype "passive"))
      (node (ref "IC42") (pin "11") (pinfunction "11_11") (pintype "passive"))
      (node (ref "SV67") (pin "12") (pinfunction "12_12") (pintype "passive"))
    )
    (net (code "565") (name "Net-(IC34-Pad12)") (class "Default")
      (node (ref "IC34") (pin "12") (pinfunction "12_12") (pintype "passive"))
      (node (ref "IC42") (pin "12") (pinfunction "12_12") (pintype "passive"))
      (node (ref "SV67") (pin "13") (pinfunction "13_13") (pintype "passive"))
    )
    (net (code "566") (name "Net-(IC34-Pad13)") (class "Default")
      (node (ref "IC34") (pin "13") (pinfunction "13_13") (pintype "passive"))
      (node (ref "IC42") (pin "13") (pinfunction "13_13") (pintype "passive"))
      (node (ref "SV68") (pin "1") (pinfunction "1_1") (pintype "passive"))
    )
    (net (code "567") (name "Net-(IC34-Pad14)") (class "Default")
      (node (ref "IC34") (pin "14") (pinfunction "14_14") (pintype "passive"))
      (node (ref "IC42") (pin "14") (pinfunction "14_14") (pintype "passive"))
      (node (ref "SV68") (pin "2") (pinfunction "2_2") (pintype "passive"))
    )
    (net (code "568") (name "Net-(IC34-Pad15)") (class "Default")
      (node (ref "IC34") (pin "15") (pinfunction "15_15") (pintype "passive"))
      (node (ref "IC42") (pin "15") (pinfunction "15_15") (pintype "passive"))
      (node (ref "SV68") (pin "3") (pinfunction "3_3") (pintype "passive"))
    )
    (net (code "569") (name "Net-(IC34-Pad16)") (class "Default")
      (node (ref "IC34") (pin "16") (pinfunction "16_16") (pintype "passive"))
      (node (ref "IC42") (pin "16") (pinfunction "16_16") (pintype "passive"))
      (node (ref "SV68") (pin "4") (pinfunction "4_4") (pintype "passive"))
    )
    (net (code "570") (name "Net-(IC34-Pad17)") (class "Default")
      (node (ref "IC34") (pin "17") (pinfunction "17_17") (pintype "passive"))
      (node (ref "IC42") (pin "17") (pinfunction "17_17") (pintype "passive"))
      (node (ref "SV68") (pin "5") (pinfunction "5_5") (pintype "passive"))
    )
    (net (code "571") (name "Net-(IC34-Pad18)") (class "Default")
      (node (ref "IC34") (pin "18") (pinfunction "18_18") (pintype "passive"))
      (node (ref "IC42") (pin "18") (pinfunction "18_18") (pintype "passive"))
      (node (ref "SV68") (pin "6") (pinfunction "6_6") (pintype "passive"))
    )
    (net (code "572") (name "Net-(IC34-Pad19)") (class "Default")
      (node (ref "IC34") (pin "19") (pinfunction "19_19") (pintype "passive"))
      (node (ref "IC42") (pin "19") (pinfunction "19_19") (pintype "passive"))
      (node (ref "SV68") (pin "7") (pinfunction "7_7") (pintype "passive"))
    )
    (net (code "573") (name "Net-(IC34-Pad20)") (class "Default")
      (node (ref "IC34") (pin "20") (pinfunction "20_20") (pintype "passive"))
      (node (ref "IC42") (pin "20") (pinfunction "20_20") (pintype "passive"))
      (node (ref "SV68") (pin "8") (pinfunction "8_8") (pintype "passive"))
    )
    (net (code "574") (name "Net-(IC34-Pad21)") (class "Default")
      (node (ref "IC34") (pin "21") (pinfunction "21_21") (pintype "passive"))
      (node (ref "IC42") (pin "21") (pinfunction "21_21") (pintype "passive"))
      (node (ref "SV68") (pin "9") (pinfunction "9_9") (pintype "passive"))
    )
    (net (code "575") (name "Net-(IC34-Pad22)") (class "Default")
      (node (ref "IC34") (pin "22") (pinfunction "22_22") (pintype "passive"))
      (node (ref "IC42") (pin "22") (pinfunction "22_22") (pintype "passive"))
      (node (ref "SV68") (pin "10") (pinfunction "10_10") (pintype "passive"))
    )
    (net (code "576") (name "Net-(IC34-Pad23)") (class "Default")
      (node (ref "IC34") (pin "23") (pinfunction "23_23") (pintype "passive"))
      (node (ref "IC42") (pin "23") (pinfunction "23_23") (pintype "passive"))
      (node (ref "SV68") (pin "11") (pinfunction "11_11") (pintype "passive"))
    )
    (net (code "577") (name "Net-(IC34-Pad24)") (class "Default")
      (node (ref "IC34") (pin "24") (pinfunction "24_24") (pintype "passive"))
      (node (ref "IC42") (pin "24") (pinfunction "24_24") (pintype "passive"))
      (node (ref "SV68") (pin "12") (pinfunction "12_12") (pintype "passive"))
    )
    (net (code "578") (name "Net-(IC35-Pad1)") (class "Default")
      (node (ref "IC35") (pin "1") (pinfunction "1_1") (pintype "passive"))
      (node (ref "IC43") (pin "1") (pinfunction "1_1") (pintype "passive"))
      (node (ref "SV69") (pin "2") (pinfunction "2_2") (pintype "passive"))
    )
    (net (code "579") (name "Net-(IC35-Pad2)") (class "Default")
      (node (ref "IC35") (pin "2") (pinfunction "2_2") (pintype "passive"))
      (node (ref "IC43") (pin "2") (pinfunction "2_2") (pintype "passive"))
      (node (ref "SV69") (pin "3") (pinfunction "3_3") (pintype "passive"))
    )
    (net (code "580") (name "Net-(IC35-Pad3)") (class "Default")
      (node (ref "IC35") (pin "3") (pinfunction "3_3") (pintype "passive"))
      (node (ref "IC43") (pin "3") (pinfunction "3_3") (pintype "passive"))
      (node (ref "SV69") (pin "4") (pinfunction "4_4") (pintype "passive"))
    )
    (net (code "581") (name "Net-(IC35-Pad4)") (class "Default")
      (node (ref "IC35") (pin "4") (pinfunction "4_4") (pintype "passive"))
      (node (ref "IC43") (pin "4") (pinfunction "4_4") (pintype "passive"))
      (node (ref "SV69") (pin "5") (pinfunction "5_5") (pintype "passive"))
    )
    (net (code "582") (name "Net-(IC35-Pad5)") (class "Default")
      (node (ref "IC35") (pin "5") (pinfunction "5_5") (pintype "passive"))
      (node (ref "IC43") (pin "5") (pinfunction "5_5") (pintype "passive"))
      (node (ref "SV69") (pin "6") (pinfunction "6_6") (pintype "passive"))
    )
    (net (code "583") (name "Net-(IC35-Pad6)") (class "Default")
      (node (ref "IC35") (pin "6") (pinfunction "6_6") (pintype "passive"))
      (node (ref "IC43") (pin "6") (pinfunction "6_6") (pintype "passive"))
      (node (ref "SV69") (pin "7") (pinfunction "7_7") (pintype "passive"))
    )
    (net (code "584") (name "Net-(IC35-Pad7)") (class "Default")
      (node (ref "IC35") (pin "7") (pinfunction "7_7") (pintype "passive"))
      (node (ref "IC43") (pin "7") (pinfunction "7_7") (pintype "passive"))
      (node (ref "SV69") (pin "8") (pinfunction "8_8") (pintype "passive"))
    )
    (net (code "585") (name "Net-(IC35-Pad8)") (class "Default")
      (node (ref "IC35") (pin "8") (pinfunction "8_8") (pintype "passive"))
      (node (ref "IC43") (pin "8") (pinfunction "8_8") (pintype "passive"))
      (node (ref "SV69") (pin "9") (pinfunction "9_9") (pintype "passive"))
    )
    (net (code "586") (name "Net-(IC35-Pad9)") (class "Default")
      (node (ref "IC35") (pin "9") (pinfunction "9_9") (pintype "passive"))
      (node (ref "IC43") (pin "9") (pinfunction "9_9") (pintype "passive"))
      (node (ref "SV69") (pin "10") (pinfunction "10_10") (pintype "passive"))
    )
    (net (code "587") (name "Net-(IC35-Pad10)") (class "Default")
      (node (ref "IC35") (pin "10") (pinfunction "10_10") (pintype "passive"))
      (node (ref "IC43") (pin "10") (pinfunction "10_10") (pintype "passive"))
      (node (ref "SV69") (pin "11") (pinfunction "11_11") (pintype "passive"))
    )
    (net (code "588") (name "Net-(IC35-Pad11)") (class "Default")
      (node (ref "IC35") (pin "11") (pinfunction "11_11") (pintype "passive"))
      (node (ref "IC43") (pin "11") (pinfunction "11_11") (pintype "passive"))
      (node (ref "SV69") (pin "12") (pinfunction "12_12") (pintype "passive"))
    )
    (net (code "589") (name "Net-(IC35-Pad12)") (class "Default")
      (node (ref "IC35") (pin "12") (pinfunction "12_12") (pintype "passive"))
      (node (ref "IC43") (pin "12") (pinfunction "12_12") (pintype "passive"))
      (node (ref "SV69") (pin "13") (pinfunction "13_13") (pintype "passive"))
    )
    (net (code "590") (name "Net-(IC35-Pad13)") (class "Default")
      (node (ref "IC35") (pin "13") (pinfunction "13_13") (pintype "passive"))
      (node (ref "IC43") (pin "13") (pinfunction "13_13") (pintype "passive"))
      (node (ref "SV70") (pin "1") (pinfunction "1_1") (pintype "passive"))
    )
    (net (code "591") (name "Net-(IC35-Pad14)") (class "Default")
      (node (ref "IC35") (pin "14") (pinfunction "14_14") (pintype "passive"))
      (node (ref "IC43") (pin "14") (pinfunction "14_14") (pintype "passive"))
      (node (ref "SV70") (pin "2") (pinfunction "2_2") (pintype "passive"))
    )
    (net (code "592") (name "Net-(IC35-Pad15)") (class "Default")
      (node (ref "IC35") (pin "15") (pinfunction "15_15") (pintype "passive"))
      (node (ref "IC43") (pin "15") (pinfunction "15_15") (pintype "passive"))
      (node (ref "SV70") (pin "3") (pinfunction "3_3") (pintype "passive"))
    )
    (net (code "593") (name "Net-(IC35-Pad16)") (class "Default")
      (node (ref "IC35") (pin "16") (pinfunction "16_16") (pintype "passive"))
      (node (ref "IC43") (pin "16") (pinfunction "16_16") (pintype "passive"))
      (node (ref "SV70") (pin "4") (pinfunction "4_4") (pintype "passive"))
    )
    (net (code "594") (name "Net-(IC35-Pad17)") (class "Default")
      (node (ref "IC35") (pin "17") (pinfunction "17_17") (pintype "passive"))
      (node (ref "IC43") (pin "17") (pinfunction "17_17") (pintype "passive"))
      (node (ref "SV70") (pin "5") (pinfunction "5_5") (pintype "passive"))
    )
    (net (code "595") (name "Net-(IC35-Pad18)") (class "Default")
      (node (ref "IC35") (pin "18") (pinfunction "18_18") (pintype "passive"))
      (node (ref "IC43") (pin "18") (pinfunction "18_18") (pintype "passive"))
      (node (ref "SV70") (pin "6") (pinfunction "6_6") (pintype "passive"))
    )
    (net (code "596") (name "Net-(IC35-Pad19)") (class "Default")
      (node (ref "IC35") (pin "19") (pinfunction "19_19") (pintype "passive"))
      (node (ref "IC43") (pin "19") (pinfunction "19_19") (pintype "passive"))
      (node (ref "SV70") (pin "7") (pinfunction "7_7") (pintype "passive"))
    )
    (net (code "597") (name "Net-(IC35-Pad20)") (class "Default")
      (node (ref "IC35") (pin "20") (pinfunction "20_20") (pintype "passive"))
      (node (ref "IC43") (pin "20") (pinfunction "20_20") (pintype "passive"))
      (node (ref "SV70") (pin "8") (pinfunction "8_8") (pintype "passive"))
    )
    (net (code "598") (name "Net-(IC35-Pad21)") (class "Default")
      (node (ref "IC35") (pin "21") (pinfunction "21_21") (pintype "passive"))
      (node (ref "IC43") (pin "21") (pinfunction "21_21") (pintype "passive"))
      (node (ref "SV70") (pin "9") (pinfunction "9_9") (pintype "passive"))
    )
    (net (code "599") (name "Net-(IC35-Pad22)") (class "Default")
      (node (ref "IC35") (pin "22") (pinfunction "22_22") (pintype "passive"))
      (node (ref "IC43") (pin "22") (pinfunction "22_22") (pintype "passive"))
      (node (ref "SV70") (pin "10") (pinfunction "10_10") (pintype "passive"))
    )
    (net (code "600") (name "Net-(IC35-Pad23)") (class "Default")
      (node (ref "IC35") (pin "23") (pinfunction "23_23") (pintype "passive"))
      (node (ref "IC43") (pin "23") (pinfunction "23_23") (pintype "passive"))
      (node (ref "SV70") (pin "11") (pinfunction "11_11") (pintype "passive"))
    )
    (net (code "601") (name "Net-(IC35-Pad24)") (class "Default")
      (node (ref "IC35") (pin "24") (pinfunction "24_24") (pintype "passive"))
      (node (ref "IC43") (pin "24") (pinfunction "24_24") (pintype "passive"))
      (node (ref "SV70") (pin "12") (pinfunction "12_12") (pintype "passive"))
    )
    (net (code "602") (name "Net-(IC36-Pad1)") (class "Default")
      (node (ref "IC36") (pin "1") (pinfunction "1_1") (pintype "passive"))
      (node (ref "IC44") (pin "1") (pinfunction "1_1") (pintype "passive"))
      (node (ref "SV71") (pin "2") (pinfunction "2_2") (pintype "passive"))
    )
    (net (code "603") (name "Net-(IC36-Pad2)") (class "Default")
      (node (ref "IC36") (pin "2") (pinfunction "2_2") (pintype "passive"))
      (node (ref "IC44") (pin "2") (pinfunction "2_2") (pintype "passive"))
      (node (ref "SV71") (pin "3") (pinfunction "3_3") (pintype "passive"))
    )
    (net (code "604") (name "Net-(IC36-Pad3)") (class "Default")
      (node (ref "IC36") (pin "3") (pinfunction "3_3") (pintype "passive"))
      (node (ref "IC44") (pin "3") (pinfunction "3_3") (pintype "passive"))
      (node (ref "SV71") (pin "4") (pinfunction "4_4") (pintype "passive"))
    )
    (net (code "605") (name "Net-(IC36-Pad4)") (class "Default")
      (node (ref "IC36") (pin "4") (pinfunction "4_4") (pintype "passive"))
      (node (ref "IC44") (pin "4") (pinfunction "4_4") (pintype "passive"))
      (node (ref "SV71") (pin "5") (pinfunction "5_5") (pintype "passive"))
    )
    (net (code "606") (name "Net-(IC36-Pad5)") (class "Default")
      (node (ref "IC36") (pin "5") (pinfunction "5_5") (pintype "passive"))
      (node (ref "IC44") (pin "5") (pinfunction "5_5") (pintype "passive"))
      (node (ref "SV71") (pin "6") (pinfunction "6_6") (pintype "passive"))
    )
    (net (code "607") (name "Net-(IC36-Pad6)") (class "Default")
      (node (ref "IC36") (pin "6") (pinfunction "6_6") (pintype "passive"))
      (node (ref "IC44") (pin "6") (pinfunction "6_6") (pintype "passive"))
      (node (ref "SV71") (pin "7") (pinfunction "7_7") (pintype "passive"))
    )
    (net (code "608") (name "Net-(IC36-Pad7)") (class "Default")
      (node (ref "IC36") (pin "7") (pinfunction "7_7") (pintype "passive"))
      (node (ref "IC44") (pin "7") (pinfunction "7_7") (pintype "passive"))
      (node (ref "SV71") (pin "8") (pinfunction "8_8") (pintype "passive"))
    )
    (net (code "609") (name "Net-(IC36-Pad8)") (class "Default")
      (node (ref "IC36") (pin "8") (pinfunction "8_8") (pintype "passive"))
      (node (ref "IC44") (pin "8") (pinfunction "8_8") (pintype "passive"))
      (node (ref "SV71") (pin "9") (pinfunction "9_9") (pintype "passive"))
    )
    (net (code "610") (name "Net-(IC36-Pad9)") (class "Default")
      (node (ref "IC36") (pin "9") (pinfunction "9_9") (pintype "passive"))
      (node (ref "IC44") (pin "9") (pinfunction "9_9") (pintype "passive"))
      (node (ref "SV71") (pin "10") (pinfunction "10_10") (pintype "passive"))
    )
    (net (code "611") (name "Net-(IC36-Pad10)") (class "Default")
      (node (ref "IC36") (pin "10") (pinfunction "10_10") (pintype "passive"))
      (node (ref "IC44") (pin "10") (pinfunction "10_10") (pintype "passive"))
      (node (ref "SV71") (pin "11") (pinfunction "11_11") (pintype "passive"))
    )
    (net (code "612") (name "Net-(IC36-Pad11)") (class "Default")
      (node (ref "IC36") (pin "11") (pinfunction "11_11") (pintype "passive"))
      (node (ref "IC44") (pin "11") (pinfunction "11_11") (pintype "passive"))
      (node (ref "SV71") (pin "12") (pinfunction "12_12") (pintype "passive"))
    )
    (net (code "613") (name "Net-(IC36-Pad12)") (class "Default")
      (node (ref "IC36") (pin "12") (pinfunction "12_12") (pintype "passive"))
      (node (ref "IC44") (pin "12") (pinfunction "12_12") (pintype "passive"))
      (node (ref "SV71") (pin "13") (pinfunction "13_13") (pintype "passive"))
    )
    (net (code "614") (name "Net-(IC36-Pad13)") (class "Default")
      (node (ref "IC36") (pin "13") (pinfunction "13_13") (pintype "passive"))
      (node (ref "IC44") (pin "13") (pinfunction "13_13") (pintype "passive"))
      (node (ref "SV72") (pin "1") (pinfunction "1_1") (pintype "passive"))
    )
    (net (code "615") (name "Net-(IC36-Pad14)") (class "Default")
      (node (ref "IC36") (pin "14") (pinfunction "14_14") (pintype "passive"))
      (node (ref "IC44") (pin "14") (pinfunction "14_14") (pintype "passive"))
      (node (ref "SV72") (pin "2") (pinfunction "2_2") (pintype "passive"))
    )
    (net (code "616") (name "Net-(IC36-Pad15)") (class "Default")
      (node (ref "IC36") (pin "15") (pinfunction "15_15") (pintype "passive"))
      (node (ref "IC44") (pin "15") (pinfunction "15_15") (pintype "passive"))
      (node (ref "SV72") (pin "3") (pinfunction "3_3") (pintype "passive"))
    )
    (net (code "617") (name "Net-(IC36-Pad16)") (class "Default")
      (node (ref "IC36") (pin "16") (pinfunction "16_16") (pintype "passive"))
      (node (ref "IC44") (pin "16") (pinfunction "16_16") (pintype "passive"))
      (node (ref "SV72") (pin "4") (pinfunction "4_4") (pintype "passive"))
    )
    (net (code "618") (name "Net-(IC36-Pad17)") (class "Default")
      (node (ref "IC36") (pin "17") (pinfunction "17_17") (pintype "passive"))
      (node (ref "IC44") (pin "17") (pinfunction "17_17") (pintype "passive"))
      (node (ref "SV72") (pin "5") (pinfunction "5_5") (pintype "passive"))
    )
    (net (code "619") (name "Net-(IC36-Pad18)") (class "Default")
      (node (ref "IC36") (pin "18") (pinfunction "18_18") (pintype "passive"))
      (node (ref "IC44") (pin "18") (pinfunction "18_18") (pintype "passive"))
      (node (ref "SV72") (pin "6") (pinfunction "6_6") (pintype "passive"))
    )
    (net (code "620") (name "Net-(IC36-Pad19)") (class "Default")
      (node (ref "IC36") (pin "19") (pinfunction "19_19") (pintype "passive"))
      (node (ref "IC44") (pin "19") (pinfunction "19_19") (pintype "passive"))
      (node (ref "SV72") (pin "7") (pinfunction "7_7") (pintype "passive"))
    )
    (net (code "621") (name "Net-(IC36-Pad20)") (class "Default")
      (node (ref "IC36") (pin "20") (pinfunction "20_20") (pintype "passive"))
      (node (ref "IC44") (pin "20") (pinfunction "20_20") (pintype "passive"))
      (node (ref "SV72") (pin "8") (pinfunction "8_8") (pintype "passive"))
    )
    (net (code "622") (name "Net-(IC36-Pad21)") (class "Default")
      (node (ref "IC36") (pin "21") (pinfunction "21_21") (pintype "passive"))
      (node (ref "IC44") (pin "21") (pinfunction "21_21") (pintype "passive"))
      (node (ref "SV72") (pin "9") (pinfunction "9_9") (pintype "passive"))
    )
    (net (code "623") (name "Net-(IC36-Pad22)") (class "Default")
      (node (ref "IC36") (pin "22") (pinfunction "22_22") (pintype "passive"))
      (node (ref "IC44") (pin "22") (pinfunction "22_22") (pintype "passive"))
      (node (ref "SV72") (pin "10") (pinfunction "10_10") (pintype "passive"))
    )
    (net (code "624") (name "Net-(IC36-Pad23)") (class "Default")
      (node (ref "IC36") (pin "23") (pinfunction "23_23") (pintype "passive"))
      (node (ref "IC44") (pin "23") (pinfunction "23_23") (pintype "passive"))
      (node (ref "SV72") (pin "11") (pinfunction "11_11") (pintype "passive"))
    )
    (net (code "625") (name "Net-(IC36-Pad24)") (class "Default")
      (node (ref "IC36") (pin "24") (pinfunction "24_24") (pintype "passive"))
      (node (ref "IC44") (pin "24") (pinfunction "24_24") (pintype "passive"))
      (node (ref "SV72") (pin "12") (pinfunction "12_12") (pintype "passive"))
    )
    (net (code "626") (name "Net-(IC37-Pad1)") (class "Default")
      (node (ref "IC37") (pin "1") (pinfunction "1_1") (pintype "passive"))
      (node (ref "IC45") (pin "1") (pinfunction "1_1") (pintype "passive"))
      (node (ref "SV73") (pin "2") (pinfunction "2_2") (pintype "passive"))
    )
    (net (code "627") (name "Net-(IC37-Pad2)") (class "Default")
      (node (ref "IC37") (pin "2") (pinfunction "2_2") (pintype "passive"))
      (node (ref "IC45") (pin "2") (pinfunction "2_2") (pintype "passive"))
      (node (ref "SV73") (pin "3") (pinfunction "3_3") (pintype "passive"))
    )
    (net (code "628") (name "Net-(IC37-Pad3)") (class "Default")
      (node (ref "IC37") (pin "3") (pinfunction "3_3") (pintype "passive"))
      (node (ref "IC45") (pin "3") (pinfunction "3_3") (pintype "passive"))
      (node (ref "SV73") (pin "4") (pinfunction "4_4") (pintype "passive"))
    )
    (net (code "629") (name "Net-(IC37-Pad4)") (class "Default")
      (node (ref "IC37") (pin "4") (pinfunction "4_4") (pintype "passive"))
      (node (ref "IC45") (pin "4") (pinfunction "4_4") (pintype "passive"))
      (node (ref "SV73") (pin "5") (pinfunction "5_5") (pintype "passive"))
    )
    (net (code "630") (name "Net-(IC37-Pad5)") (class "Default")
      (node (ref "IC37") (pin "5") (pinfunction "5_5") (pintype "passive"))
      (node (ref "IC45") (pin "5") (pinfunction "5_5") (pintype "passive"))
      (node (ref "SV73") (pin "6") (pinfunction "6_6") (pintype "passive"))
    )
    (net (code "631") (name "Net-(IC37-Pad6)") (class "Default")
      (node (ref "IC37") (pin "6") (pinfunction "6_6") (pintype "passive"))
      (node (ref "IC45") (pin "6") (pinfunction "6_6") (pintype "passive"))
      (node (ref "SV73") (pin "7") (pinfunction "7_7") (pintype "passive"))
    )
    (net (code "632") (name "Net-(IC37-Pad7)") (class "Default")
      (node (ref "IC37") (pin "7") (pinfunction "7_7") (pintype "passive"))
      (node (ref "IC45") (pin "7") (pinfunction "7_7") (pintype "passive"))
      (node (ref "SV73") (pin "8") (pinfunction "8_8") (pintype "passive"))
    )
    (net (code "633") (name "Net-(IC37-Pad8)") (class "Default")
      (node (ref "IC37") (pin "8") (pinfunction "8_8") (pintype "passive"))
      (node (ref "IC45") (pin "8") (pinfunction "8_8") (pintype "passive"))
      (node (ref "SV73") (pin "9") (pinfunction "9_9") (pintype "passive"))
    )
    (net (code "634") (name "Net-(IC37-Pad9)") (class "Default")
      (node (ref "IC37") (pin "9") (pinfunction "9_9") (pintype "passive"))
      (node (ref "IC45") (pin "9") (pinfunction "9_9") (pintype "passive"))
      (node (ref "SV73") (pin "10") (pinfunction "10_10") (pintype "passive"))
    )
    (net (code "635") (name "Net-(IC37-Pad10)") (class "Default")
      (node (ref "IC37") (pin "10") (pinfunction "10_10") (pintype "passive"))
      (node (ref "IC45") (pin "10") (pinfunction "10_10") (pintype "passive"))
      (node (ref "SV73") (pin "11") (pinfunction "11_11") (pintype "passive"))
    )
    (net (code "636") (name "Net-(IC37-Pad11)") (class "Default")
      (node (ref "IC37") (pin "11") (pinfunction "11_11") (pintype "passive"))
      (node (ref "IC45") (pin "11") (pinfunction "11_11") (pintype "passive"))
      (node (ref "SV73") (pin "12") (pinfunction "12_12") (pintype "passive"))
    )
    (net (code "637") (name "Net-(IC37-Pad12)") (class "Default")
      (node (ref "IC37") (pin "12") (pinfunction "12_12") (pintype "passive"))
      (node (ref "IC45") (pin "12") (pinfunction "12_12") (pintype "passive"))
      (node (ref "SV73") (pin "13") (pinfunction "13_13") (pintype "passive"))
    )
    (net (code "638") (name "Net-(IC37-Pad13)") (class "Default")
      (node (ref "IC37") (pin "13") (pinfunction "13_13") (pintype "passive"))
      (node (ref "IC45") (pin "13") (pinfunction "13_13") (pintype "passive"))
      (node (ref "SV74") (pin "1") (pinfunction "1_1") (pintype "passive"))
    )
    (net (code "639") (name "Net-(IC37-Pad14)") (class "Default")
      (node (ref "IC37") (pin "14") (pinfunction "14_14") (pintype "passive"))
      (node (ref "IC45") (pin "14") (pinfunction "14_14") (pintype "passive"))
      (node (ref "SV74") (pin "2") (pinfunction "2_2") (pintype "passive"))
    )
    (net (code "640") (name "Net-(IC37-Pad15)") (class "Default")
      (node (ref "IC37") (pin "15") (pinfunction "15_15") (pintype "passive"))
      (node (ref "IC45") (pin "15") (pinfunction "15_15") (pintype "passive"))
      (node (ref "SV74") (pin "3") (pinfunction "3_3") (pintype "passive"))
    )
    (net (code "641") (name "Net-(IC37-Pad16)") (class "Default")
      (node (ref "IC37") (pin "16") (pinfunction "16_16") (pintype "passive"))
      (node (ref "IC45") (pin "16") (pinfunction "16_16") (pintype "passive"))
      (node (ref "SV74") (pin "4") (pinfunction "4_4") (pintype "passive"))
    )
    (net (code "642") (name "Net-(IC37-Pad17)") (class "Default")
      (node (ref "IC37") (pin "17") (pinfunction "17_17") (pintype "passive"))
      (node (ref "IC45") (pin "17") (pinfunction "17_17") (pintype "passive"))
      (node (ref "SV74") (pin "5") (pinfunction "5_5") (pintype "passive"))
    )
    (net (code "643") (name "Net-(IC37-Pad18)") (class "Default")
      (node (ref "IC37") (pin "18") (pinfunction "18_18") (pintype "passive"))
      (node (ref "IC45") (pin "18") (pinfunction "18_18") (pintype "passive"))
      (node (ref "SV74") (pin "6") (pinfunction "6_6") (pintype "passive"))
    )
    (net (code "644") (name "Net-(IC37-Pad19)") (class "Default")
      (node (ref "IC37") (pin "19") (pinfunction "19_19") (pintype "passive"))
      (node (ref "IC45") (pin "19") (pinfunction "19_19") (pintype "passive"))
      (node (ref "SV74") (pin "7") (pinfunction "7_7") (pintype "passive"))
    )
    (net (code "645") (name "Net-(IC37-Pad20)") (class "Default")
      (node (ref "IC37") (pin "20") (pinfunction "20_20") (pintype "passive"))
      (node (ref "IC45") (pin "20") (pinfunction "20_20") (pintype "passive"))
      (node (ref "SV74") (pin "8") (pinfunction "8_8") (pintype "passive"))
    )
    (net (code "646") (name "Net-(IC37-Pad21)") (class "Default")
      (node (ref "IC37") (pin "21") (pinfunction "21_21") (pintype "passive"))
      (node (ref "IC45") (pin "21") (pinfunction "21_21") (pintype "passive"))
      (node (ref "SV74") (pin "9") (pinfunction "9_9") (pintype "passive"))
    )
    (net (code "647") (name "Net-(IC37-Pad22)") (class "Default")
      (node (ref "IC37") (pin "22") (pinfunction "22_22") (pintype "passive"))
      (node (ref "IC45") (pin "22") (pinfunction "22_22") (pintype "passive"))
      (node (ref "SV74") (pin "10") (pinfunction "10_10") (pintype "passive"))
    )
    (net (code "648") (name "Net-(IC37-Pad23)") (class "Default")
      (node (ref "IC37") (pin "23") (pinfunction "23_23") (pintype "passive"))
      (node (ref "IC45") (pin "23") (pinfunction "23_23") (pintype "passive"))
      (node (ref "SV74") (pin "11") (pinfunction "11_11") (pintype "passive"))
    )
    (net (code "649") (name "Net-(IC37-Pad24)") (class "Default")
      (node (ref "IC37") (pin "24") (pinfunction "24_24") (pintype "passive"))
      (node (ref "IC45") (pin "24") (pinfunction "24_24") (pintype "passive"))
      (node (ref "SV74") (pin "12") (pinfunction "12_12") (pintype "passive"))
    )
    (net (code "650") (name "Net-(IC38-Pad1)") (class "Default")
      (node (ref "IC38") (pin "1") (pinfunction "1_1") (pintype "passive"))
      (node (ref "IC46") (pin "1") (pinfunction "1_1") (pintype "passive"))
      (node (ref "SV75") (pin "2") (pinfunction "2_2") (pintype "passive"))
    )
    (net (code "651") (name "Net-(IC38-Pad2)") (class "Default")
      (node (ref "IC38") (pin "2") (pinfunction "2_2") (pintype "passive"))
      (node (ref "IC46") (pin "2") (pinfunction "2_2") (pintype "passive"))
      (node (ref "SV75") (pin "3") (pinfunction "3_3") (pintype "passive"))
    )
    (net (code "652") (name "Net-(IC38-Pad3)") (class "Default")
      (node (ref "IC38") (pin "3") (pinfunction "3_3") (pintype "passive"))
      (node (ref "IC46") (pin "3") (pinfunction "3_3") (pintype "passive"))
      (node (ref "SV75") (pin "4") (pinfunction "4_4") (pintype "passive"))
    )
    (net (code "653") (name "Net-(IC38-Pad4)") (class "Default")
      (node (ref "IC38") (pin "4") (pinfunction "4_4") (pintype "passive"))
      (node (ref "IC46") (pin "4") (pinfunction "4_4") (pintype "passive"))
      (node (ref "SV75") (pin "5") (pinfunction "5_5") (pintype "passive"))
    )
    (net (code "654") (name "Net-(IC38-Pad5)") (class "Default")
      (node (ref "IC38") (pin "5") (pinfunction "5_5") (pintype "passive"))
      (node (ref "IC46") (pin "5") (pinfunction "5_5") (pintype "passive"))
      (node (ref "SV75") (pin "6") (pinfunction "6_6") (pintype "passive"))
    )
    (net (code "655") (name "Net-(IC38-Pad6)") (class "Default")
      (node (ref "IC38") (pin "6") (pinfunction "6_6") (pintype "passive"))
      (node (ref "IC46") (pin "6") (pinfunction "6_6") (pintype "passive"))
      (node (ref "SV75") (pin "7") (pinfunction "7_7") (pintype "passive"))
    )
    (net (code "656") (name "Net-(IC38-Pad7)") (class "Default")
      (node (ref "IC38") (pin "7") (pinfunction "7_7") (pintype "passive"))
      (node (ref "IC46") (pin "7") (pinfunction "7_7") (pintype "passive"))
      (node (ref "SV75") (pin "8") (pinfunction "8_8") (pintype "passive"))
    )
    (net (code "657") (name "Net-(IC38-Pad8)") (class "Default")
      (node (ref "IC38") (pin "8") (pinfunction "8_8") (pintype "passive"))
      (node (ref "IC46") (pin "8") (pinfunction "8_8") (pintype "passive"))
      (node (ref "SV75") (pin "9") (pinfunction "9_9") (pintype "passive"))
    )
    (net (code "658") (name "Net-(IC38-Pad9)") (class "Default")
      (node (ref "IC38") (pin "9") (pinfunction "9_9") (pintype "passive"))
      (node (ref "IC46") (pin "9") (pinfunction "9_9") (pintype "passive"))
      (node (ref "SV75") (pin "10") (pinfunction "10_10") (pintype "passive"))
    )
    (net (code "659") (name "Net-(IC38-Pad10)") (class "Default")
      (node (ref "IC38") (pin "10") (pinfunction "10_10") (pintype "passive"))
      (node (ref "IC46") (pin "10") (pinfunction "10_10") (pintype "passive"))
      (node (ref "SV75") (pin "11") (pinfunction "11_11") (pintype "passive"))
    )
    (net (code "660") (name "Net-(IC38-Pad11)") (class "Default")
      (node (ref "IC38") (pin "11") (pinfunction "11_11") (pintype "passive"))
      (node (ref "IC46") (pin "11") (pinfunction "11_11") (pintype "passive"))
      (node (ref "SV75") (pin "12") (pinfunction "12_12") (pintype "passive"))
    )
    (net (code "661") (name "Net-(IC38-Pad12)") (class "Default")
      (node (ref "IC38") (pin "12") (pinfunction "12_12") (pintype "passive"))
      (node (ref "IC46") (pin "12") (pinfunction "12_12") (pintype "passive"))
      (node (ref "SV75") (pin "13") (pinfunction "13_13") (pintype "passive"))
    )
    (net (code "662") (name "Net-(IC38-Pad13)") (class "Default")
      (node (ref "IC38") (pin "13") (pinfunction "13_13") (pintype "passive"))
      (node (ref "IC46") (pin "13") (pinfunction "13_13") (pintype "passive"))
      (node (ref "SV76") (pin "1") (pinfunction "1_1") (pintype "passive"))
    )
    (net (code "663") (name "Net-(IC38-Pad14)") (class "Default")
      (node (ref "IC38") (pin "14") (pinfunction "14_14") (pintype "passive"))
      (node (ref "IC46") (pin "14") (pinfunction "14_14") (pintype "passive"))
      (node (ref "SV76") (pin "2") (pinfunction "2_2") (pintype "passive"))
    )
    (net (code "664") (name "Net-(IC38-Pad15)") (class "Default")
      (node (ref "IC38") (pin "15") (pinfunction "15_15") (pintype "passive"))
      (node (ref "IC46") (pin "15") (pinfunction "15_15") (pintype "passive"))
      (node (ref "SV76") (pin "3") (pinfunction "3_3") (pintype "passive"))
    )
    (net (code "665") (name "Net-(IC38-Pad16)") (class "Default")
      (node (ref "IC38") (pin "16") (pinfunction "16_16") (pintype "passive"))
      (node (ref "IC46") (pin "16") (pinfunction "16_16") (pintype "passive"))
      (node (ref "SV76") (pin "4") (pinfunction "4_4") (pintype "passive"))
    )
    (net (code "666") (name "Net-(IC38-Pad17)") (class "Default")
      (node (ref "IC38") (pin "17") (pinfunction "17_17") (pintype "passive"))
      (node (ref "IC46") (pin "17") (pinfunction "17_17") (pintype "passive"))
      (node (ref "SV76") (pin "5") (pinfunction "5_5") (pintype "passive"))
    )
    (net (code "667") (name "Net-(IC38-Pad18)") (class "Default")
      (node (ref "IC38") (pin "18") (pinfunction "18_18") (pintype "passive"))
      (node (ref "IC46") (pin "18") (pinfunction "18_18") (pintype "passive"))
      (node (ref "SV76") (pin "6") (pinfunction "6_6") (pintype "passive"))
    )
    (net (code "668") (name "Net-(IC38-Pad19)") (class "Default")
      (node (ref "IC38") (pin "19") (pinfunction "19_19") (pintype "passive"))
      (node (ref "IC46") (pin "19") (pinfunction "19_19") (pintype "passive"))
      (node (ref "SV76") (pin "7") (pinfunction "7_7") (pintype "passive"))
    )
    (net (code "669") (name "Net-(IC38-Pad20)") (class "Default")
      (node (ref "IC38") (pin "20") (pinfunction "20_20") (pintype "passive"))
      (node (ref "IC46") (pin "20") (pinfunction "20_20") (pintype "passive"))
      (node (ref "SV76") (pin "8") (pinfunction "8_8") (pintype "passive"))
    )
    (net (code "670") (name "Net-(IC38-Pad21)") (class "Default")
      (node (ref "IC38") (pin "21") (pinfunction "21_21") (pintype "passive"))
      (node (ref "IC46") (pin "21") (pinfunction "21_21") (pintype "passive"))
      (node (ref "SV76") (pin "9") (pinfunction "9_9") (pintype "passive"))
    )
    (net (code "671") (name "Net-(IC38-Pad22)") (class "Default")
      (node (ref "IC38") (pin "22") (pinfunction "22_22") (pintype "passive"))
      (node (ref "IC46") (pin "22") (pinfunction "22_22") (pintype "passive"))
      (node (ref "SV76") (pin "10") (pinfunction "10_10") (pintype "passive"))
    )
    (net (code "672") (name "Net-(IC38-Pad23)") (class "Default")
      (node (ref "IC38") (pin "23") (pinfunction "23_23") (pintype "passive"))
      (node (ref "IC46") (pin "23") (pinfunction "23_23") (pintype "passive"))
      (node (ref "SV76") (pin "11") (pinfunction "11_11") (pintype "passive"))
    )
    (net (code "673") (name "Net-(IC38-Pad24)") (class "Default")
      (node (ref "IC38") (pin "24") (pinfunction "24_24") (pintype "passive"))
      (node (ref "IC46") (pin "24") (pinfunction "24_24") (pintype "passive"))
      (node (ref "SV76") (pin "12") (pinfunction "12_12") (pintype "passive"))
    )
    (net (code "674") (name "Net-(U$1A-1)") (class "Default")
      (node (ref "U$1") (pin "AA1") (pinfunction "1_AA1") (pintype "bidirectional"))
      (node (ref "U$2") (pin "A2") (pinfunction "P$1_A2") (pintype "passive"))
    )
    (net (code "675") (name "Net-(U$1AA-1)") (class "Default")
      (node (ref "U$1") (pin "AR1") (pinfunction "1_AR1") (pintype "bidirectional"))
      (node (ref "U$2") (pin "R2") (pinfunction "P$1_R2") (pintype "passive"))
    )
    (net (code "676") (name "Net-(U$1AB-1)") (class "Default")
      (node (ref "U$1") (pin "AR2") (pinfunction "1_AR2") (pintype "bidirectional"))
      (node (ref "U$2") (pin "R1") (pinfunction "P$1_R1") (pintype "passive"))
    )
    (net (code "677") (name "Net-(U$1AC-1)") (class "Default")
      (node (ref "U$1") (pin "AS1") (pinfunction "1_AS1") (pintype "bidirectional"))
      (node (ref "U$2") (pin "S2") (pinfunction "P$1_S2") (pintype "passive"))
    )
    (net (code "678") (name "Net-(U$1AD-1)") (class "Default")
      (node (ref "U$1") (pin "AS2") (pinfunction "1_AS2") (pintype "bidirectional"))
      (node (ref "U$2") (pin "S1") (pinfunction "P$1_S1") (pintype "passive"))
    )
    (net (code "679") (name "Net-(U$1AF-1)") (class "Default")
      (node (ref "U$1") (pin "AT2") (pinfunction "1_AT2") (pintype "bidirectional"))
      (node (ref "U$2") (pin "T1") (pinfunction "P$1_T1") (pintype "passive"))
    )
    (net (code "680") (name "Net-(U$1AG-1)") (class "Default")
      (node (ref "U$1") (pin "AU1") (pinfunction "1_AU1") (pintype "bidirectional"))
      (node (ref "U$2") (pin "U2") (pinfunction "P$1_U2") (pintype "passive"))
    )
    (net (code "681") (name "Net-(U$1AH-1)") (class "Default")
      (node (ref "U$1") (pin "AU2") (pinfunction "1_AU2") (pintype "bidirectional"))
      (node (ref "U$2") (pin "U1") (pinfunction "P$1_U1") (pintype "passive"))
    )
    (net (code "682") (name "Net-(U$1AI-1)") (class "Default")
      (node (ref "U$1") (pin "AV1") (pinfunction "1_AV1") (pintype "bidirectional"))
      (node (ref "U$2") (pin "V2") (pinfunction "P$1_V2") (pintype "passive"))
    )
    (net (code "683") (name "Net-(U$1AJ-1)") (class "Default")
      (node (ref "U$1") (pin "AV2") (pinfunction "1_AV2") (pintype "bidirectional"))
      (node (ref "U$2") (pin "V1") (pinfunction "P$1_V1") (pintype "passive"))
    )
    (net (code "684") (name "Net-(U$1AK-1)") (class "Default")
      (node (ref "U$1") (pin "BA1") (pinfunction "1_BA1") (pintype "bidirectional"))
      (node (ref "U$3") (pin "A2") (pinfunction "P$1_A2") (pintype "passive"))
    )
    (net (code "685") (name "Net-(U$1AM-1)") (class "Default")
      (node (ref "U$1") (pin "BB1") (pinfunction "1_BB1") (pintype "bidirectional"))
      (node (ref "U$3") (pin "B2") (pinfunction "P$1_B2") (pintype "passive"))
    )
    (net (code "686") (name "Net-(U$1AN-1)") (class "Default")
      (node (ref "U$1") (pin "BB2") (pinfunction "1_BB2") (pintype "bidirectional"))
      (node (ref "U$3") (pin "B1") (pinfunction "P$1_B1") (pintype "passive"))
    )
    (net (code "687") (name "Net-(U$1AO-1)") (class "Default")
      (node (ref "U$1") (pin "BC1") (pinfunction "1_BC1") (pintype "bidirectional"))
      (node (ref "U$3") (pin "C2") (pinfunction "P$1_C2") (pintype "passive"))
    )
    (net (code "688") (name "Net-(U$1AQ-1)") (class "Default")
      (node (ref "U$1") (pin "BD1") (pinfunction "1_BD1") (pintype "bidirectional"))
      (node (ref "U$3") (pin "D2") (pinfunction "P$1_D2") (pintype "passive"))
    )
    (net (code "689") (name "Net-(U$1AR-1)") (class "Default")
      (node (ref "U$1") (pin "BD2") (pinfunction "1_BD2") (pintype "bidirectional"))
      (node (ref "U$3") (pin "D1") (pinfunction "P$1_D1") (pintype "passive"))
    )
    (net (code "690") (name "Net-(U$1AS-1)") (class "Default")
      (node (ref "U$1") (pin "BE1") (pinfunction "1_BE1") (pintype "bidirectional"))
      (node (ref "U$3") (pin "E2") (pinfunction "P$1_E2") (pintype "passive"))
    )
    (net (code "691") (name "Net-(U$1AT-1)") (class "Default")
      (node (ref "U$1") (pin "BE2") (pinfunction "1_BE2") (pintype "bidirectional"))
      (node (ref "U$3") (pin "E1") (pinfunction "P$1_E1") (pintype "passive"))
    )
    (net (code "692") (name "Net-(U$1AU-1)") (class "Default")
      (node (ref "U$1") (pin "BF1") (pinfunction "1_BF1") (pintype "bidirectional"))
      (node (ref "U$3") (pin "F2") (pinfunction "P$1_F2") (pintype "passive"))
    )
    (net (code "693") (name "Net-(U$1AV-1)") (class "Default")
      (node (ref "U$1") (pin "BF2") (pinfunction "1_BF2") (pintype "bidirectional"))
      (node (ref "U$3") (pin "F1") (pinfunction "P$1_F1") (pintype "passive"))
    )
    (net (code "694") (name "Net-(U$1AW-1)") (class "Default")
      (node (ref "U$1") (pin "BH1") (pinfunction "1_BH1") (pintype "bidirectional"))
      (node (ref "U$3") (pin "H2") (pinfunction "P$1_H2") (pintype "passive"))
    )
    (net (code "695") (name "Net-(U$1AX-1)") (class "Default")
      (node (ref "U$1") (pin "BH2") (pinfunction "1_BH2") (pintype "bidirectional"))
      (node (ref "U$3") (pin "H1") (pinfunction "P$1_H1") (pintype "passive"))
    )
    (net (code "696") (name "Net-(U$1AY-1)") (class "Default")
      (node (ref "U$1") (pin "BJ1") (pinfunction "1_BJ1") (pintype "bidirectional"))
      (node (ref "U$3") (pin "J2") (pinfunction "P$1_J2") (pintype "passive"))
    )
    (net (code "697") (name "Net-(U$1AZ-1)") (class "Default")
      (node (ref "U$1") (pin "BJ2") (pinfunction "1_BJ2") (pintype "bidirectional"))
      (node (ref "U$3") (pin "J1") (pinfunction "P$1_J1") (pintype "passive"))
    )
    (net (code "698") (name "Net-(U$1BA-1)") (class "Default")
      (node (ref "U$1") (pin "BK1") (pinfunction "1_BK1") (pintype "bidirectional"))
      (node (ref "U$3") (pin "K2") (pinfunction "P$1_K2") (pintype "passive"))
    )
    (net (code "699") (name "Net-(U$1BB-1)") (class "Default")
      (node (ref "U$1") (pin "BK2") (pinfunction "1_BK2") (pintype "bidirectional"))
      (node (ref "U$3") (pin "K1") (pinfunction "P$1_K1") (pintype "passive"))
    )
    (net (code "700") (name "Net-(U$1BC-1)") (class "Default")
      (node (ref "U$1") (pin "BL1") (pinfunction "1_BL1") (pintype "bidirectional"))
      (node (ref "U$3") (pin "L2") (pinfunction "P$1_L2") (pintype "passive"))
    )
    (net (code "701") (name "Net-(U$1BD-1)") (class "Default")
      (node (ref "U$1") (pin "BL2") (pinfunction "1_BL2") (pintype "bidirectional"))
      (node (ref "U$3") (pin "L1") (pinfunction "P$1_L1") (pintype "passive"))
    )
    (net (code "702") (name "Net-(U$1BE-1)") (class "Default")
      (node (ref "U$1") (pin "BM1") (pinfunction "1_BM1") (pintype "bidirectional"))
      (node (ref "U$3") (pin "M2") (pinfunction "P$1_M2") (pintype "passive"))
    )
    (net (code "703") (name "Net-(U$1BF-1)") (class "Default")
      (node (ref "U$1") (pin "BM2") (pinfunction "1_BM2") (pintype "bidirectional"))
      (node (ref "U$3") (pin "M1") (pinfunction "P$1_M1") (pintype "passive"))
    )
    (net (code "704") (name "Net-(U$1BG-1)") (class "Default")
      (node (ref "U$1") (pin "BN1") (pinfunction "1_BN1") (pintype "bidirectional"))
      (node (ref "U$3") (pin "N2") (pinfunction "P$1_N2") (pintype "passive"))
    )
    (net (code "705") (name "Net-(U$1BH-1)") (class "Default")
      (node (ref "U$1") (pin "BN2") (pinfunction "1_BN2") (pintype "bidirectional"))
      (node (ref "U$3") (pin "N1") (pinfunction "P$1_N1") (pintype "passive"))
    )
    (net (code "706") (name "Net-(U$1BI-1)") (class "Default")
      (node (ref "U$1") (pin "BP1") (pinfunction "1_BP1") (pintype "bidirectional"))
      (node (ref "U$3") (pin "P2") (pinfunction "P$1_P2") (pintype "passive"))
    )
    (net (code "707") (name "Net-(U$1BJ-1)") (class "Default")
      (node (ref "U$1") (pin "BP2") (pinfunction "1_BP2") (pintype "bidirectional"))
      (node (ref "U$3") (pin "P1") (pinfunction "P$1_P1") (pintype "passive"))
    )
    (net (code "708") (name "Net-(U$1BK-1)") (class "Default")
      (node (ref "U$1") (pin "BR1") (pinfunction "1_BR1") (pintype "bidirectional"))
      (node (ref "U$3") (pin "R2") (pinfunction "P$1_R2") (pintype "passive"))
    )
    (net (code "709") (name "Net-(U$1BL-1)") (class "Default")
      (node (ref "U$1") (pin "BR2") (pinfunction "1_BR2") (pintype "bidirectional"))
      (node (ref "U$3") (pin "R1") (pinfunction "P$1_R1") (pintype "passive"))
    )
    (net (code "710") (name "Net-(U$1BM-1)") (class "Default")
      (node (ref "U$1") (pin "BS1") (pinfunction "1_BS1") (pintype "bidirectional"))
      (node (ref "U$3") (pin "S2") (pinfunction "P$1_S2") (pintype "passive"))
    )
    (net (code "711") (name "Net-(U$1BN-1)") (class "Default")
      (node (ref "U$1") (pin "BS2") (pinfunction "1_BS2") (pintype "bidirectional"))
      (node (ref "U$3") (pin "S1") (pinfunction "P$1_S1") (pintype "passive"))
    )
    (net (code "712") (name "Net-(U$1BP-1)") (class "Default")
      (node (ref "U$1") (pin "BT2") (pinfunction "1_BT2") (pintype "bidirectional"))
      (node (ref "U$3") (pin "T1") (pinfunction "P$1_T1") (pintype "passive"))
    )
    (net (code "713") (name "Net-(U$1BQ-1)") (class "Default")
      (node (ref "U$1") (pin "BU1") (pinfunction "1_BU1") (pintype "bidirectional"))
      (node (ref "U$3") (pin "U2") (pinfunction "P$1_U2") (pintype "passive"))
    )
    (net (code "714") (name "Net-(U$1BR-1)") (class "Default")
      (node (ref "U$1") (pin "BU2") (pinfunction "1_BU2") (pintype "bidirectional"))
      (node (ref "U$3") (pin "U1") (pinfunction "P$1_U1") (pintype "passive"))
    )
    (net (code "715") (name "Net-(U$1BS-1)") (class "Default")
      (node (ref "U$1") (pin "BV1") (pinfunction "1_BV1") (pintype "bidirectional"))
      (node (ref "U$3") (pin "V2") (pinfunction "P$1_V2") (pintype "passive"))
    )
    (net (code "716") (name "Net-(U$1BT-1)") (class "Default")
      (node (ref "U$1") (pin "BV2") (pinfunction "1_BV2") (pintype "bidirectional"))
      (node (ref "U$3") (pin "V1") (pinfunction "P$1_V1") (pintype "passive"))
    )
    (net (code "717") (name "Net-(U$1BU-1)") (class "Default")
      (node (ref "U$1") (pin "CA1") (pinfunction "1_CA1") (pintype "bidirectional"))
      (node (ref "U$4") (pin "A2") (pinfunction "P$1_A2") (pintype "passive"))
    )
    (net (code "718") (name "Net-(U$1BW-1)") (class "Default")
      (node (ref "U$1") (pin "CB1") (pinfunction "1_CB1") (pintype "bidirectional"))
      (node (ref "U$4") (pin "B2") (pinfunction "P$1_B2") (pintype "passive"))
    )
    (net (code "719") (name "Net-(U$1BX-1)") (class "Default")
      (node (ref "U$1") (pin "CB2") (pinfunction "1_CB2") (pintype "bidirectional"))
      (node (ref "U$4") (pin "B1") (pinfunction "P$1_B1") (pintype "passive"))
    )
    (net (code "720") (name "Net-(U$1BY-1)") (class "Default")
      (node (ref "U$1") (pin "CC1") (pinfunction "1_CC1") (pintype "bidirectional"))
      (node (ref "U$4") (pin "C2") (pinfunction "P$1_C2") (pintype "passive"))
    )
    (net (code "721") (name "Net-(U$1C-1)") (class "Default")
      (node (ref "U$1") (pin "AB1") (pinfunction "1_AB1") (pintype "bidirectional"))
      (node (ref "U$2") (pin "B2") (pinfunction "P$1_B2") (pintype "passive"))
    )
    (net (code "722") (name "Net-(U$1CA-1)") (class "Default")
      (node (ref "U$1") (pin "CD1") (pinfunction "1_CD1") (pintype "bidirectional"))
      (node (ref "U$4") (pin "D2") (pinfunction "P$1_D2") (pintype "passive"))
    )
    (net (code "723") (name "Net-(U$1CB-1)") (class "Default")
      (node (ref "U$1") (pin "CD2") (pinfunction "1_CD2") (pintype "bidirectional"))
      (node (ref "U$4") (pin "D1") (pinfunction "P$1_D1") (pintype "passive"))
    )
    (net (code "724") (name "Net-(U$1CC-1)") (class "Default")
      (node (ref "U$1") (pin "CE1") (pinfunction "1_CE1") (pintype "bidirectional"))
      (node (ref "U$4") (pin "E2") (pinfunction "P$1_E2") (pintype "passive"))
    )
    (net (code "725") (name "Net-(U$1CD-1)") (class "Default")
      (node (ref "U$1") (pin "CE2") (pinfunction "1_CE2") (pintype "bidirectional"))
      (node (ref "U$4") (pin "E1") (pinfunction "P$1_E1") (pintype "passive"))
    )
    (net (code "726") (name "Net-(U$1CE-1)") (class "Default")
      (node (ref "U$1") (pin "CF1") (pinfunction "1_CF1") (pintype "bidirectional"))
      (node (ref "U$4") (pin "F2") (pinfunction "P$1_F2") (pintype "passive"))
    )
    (net (code "727") (name "Net-(U$1CF-1)") (class "Default")
      (node (ref "U$1") (pin "CF2") (pinfunction "1_CF2") (pintype "bidirectional"))
      (node (ref "U$4") (pin "F1") (pinfunction "P$1_F1") (pintype "passive"))
    )
    (net (code "728") (name "Net-(U$1CG-1)") (class "Default")
      (node (ref "U$1") (pin "CH1") (pinfunction "1_CH1") (pintype "bidirectional"))
      (node (ref "U$4") (pin "H2") (pinfunction "P$1_H2") (pintype "passive"))
    )
    (net (code "729") (name "Net-(U$1CH-1)") (class "Default")
      (node (ref "U$1") (pin "CH2") (pinfunction "1_CH2") (pintype "bidirectional"))
      (node (ref "U$4") (pin "H1") (pinfunction "P$1_H1") (pintype "passive"))
    )
    (net (code "730") (name "Net-(U$1CI-1)") (class "Default")
      (node (ref "U$1") (pin "CJ1") (pinfunction "1_CJ1") (pintype "bidirectional"))
      (node (ref "U$4") (pin "J2") (pinfunction "P$1_J2") (pintype "passive"))
    )
    (net (code "731") (name "Net-(U$1CJ-1)") (class "Default")
      (node (ref "U$1") (pin "CJ2") (pinfunction "1_CJ2") (pintype "bidirectional"))
      (node (ref "U$4") (pin "J1") (pinfunction "P$1_J1") (pintype "passive"))
    )
    (net (code "732") (name "Net-(U$1CK-1)") (class "Default")
      (node (ref "U$1") (pin "CK1") (pinfunction "1_CK1") (pintype "bidirectional"))
      (node (ref "U$4") (pin "K2") (pinfunction "P$1_K2") (pintype "passive"))
    )
    (net (code "733") (name "Net-(U$1CL-1)") (class "Default")
      (node (ref "U$1") (pin "CK2") (pinfunction "1_CK2") (pintype "bidirectional"))
      (node (ref "U$4") (pin "K1") (pinfunction "P$1_K1") (pintype "passive"))
    )
    (net (code "734") (name "Net-(U$1CM-1)") (class "Default")
      (node (ref "U$1") (pin "CL1") (pinfunction "1_CL1") (pintype "bidirectional"))
      (node (ref "U$4") (pin "L2") (pinfunction "P$1_L2") (pintype "passive"))
    )
    (net (code "735") (name "Net-(U$1CN-1)") (class "Default")
      (node (ref "U$1") (pin "CL2") (pinfunction "1_CL2") (pintype "bidirectional"))
      (node (ref "U$4") (pin "L1") (pinfunction "P$1_L1") (pintype "passive"))
    )
    (net (code "736") (name "Net-(U$1CO-1)") (class "Default")
      (node (ref "U$1") (pin "CM1") (pinfunction "1_CM1") (pintype "bidirectional"))
      (node (ref "U$4") (pin "M2") (pinfunction "P$1_M2") (pintype "passive"))
    )
    (net (code "737") (name "Net-(U$1CP-1)") (class "Default")
      (node (ref "U$1") (pin "CM2") (pinfunction "1_CM2") (pintype "bidirectional"))
      (node (ref "U$4") (pin "M1") (pinfunction "P$1_M1") (pintype "passive"))
    )
    (net (code "738") (name "Net-(U$1CQ-1)") (class "Default")
      (node (ref "U$1") (pin "CN1") (pinfunction "1_CN1") (pintype "bidirectional"))
      (node (ref "U$4") (pin "N2") (pinfunction "P$1_N2") (pintype "passive"))
    )
    (net (code "739") (name "Net-(U$1CR-1)") (class "Default")
      (node (ref "U$1") (pin "CN2") (pinfunction "1_CN2") (pintype "bidirectional"))
      (node (ref "U$4") (pin "N1") (pinfunction "P$1_N1") (pintype "passive"))
    )
    (net (code "740") (name "Net-(U$1CS-1)") (class "Default")
      (node (ref "U$1") (pin "CP1") (pinfunction "1_CP1") (pintype "bidirectional"))
      (node (ref "U$4") (pin "P2") (pinfunction "P$1_P2") (pintype "passive"))
    )
    (net (code "741") (name "Net-(U$1CT-1)") (class "Default")
      (node (ref "U$1") (pin "CP2") (pinfunction "1_CP2") (pintype "bidirectional"))
      (node (ref "U$4") (pin "P1") (pinfunction "P$1_P1") (pintype "passive"))
    )
    (net (code "742") (name "Net-(U$1CU-1)") (class "Default")
      (node (ref "U$1") (pin "CR1") (pinfunction "1_CR1") (pintype "bidirectional"))
      (node (ref "U$4") (pin "R2") (pinfunction "P$1_R2") (pintype "passive"))
    )
    (net (code "743") (name "Net-(U$1CV-1)") (class "Default")
      (node (ref "U$1") (pin "CR2") (pinfunction "1_CR2") (pintype "bidirectional"))
      (node (ref "U$4") (pin "R1") (pinfunction "P$1_R1") (pintype "passive"))
    )
    (net (code "744") (name "Net-(U$1CW-1)") (class "Default")
      (node (ref "U$1") (pin "CS1") (pinfunction "1_CS1") (pintype "bidirectional"))
      (node (ref "U$4") (pin "S2") (pinfunction "P$1_S2") (pintype "passive"))
    )
    (net (code "745") (name "Net-(U$1CX-1)") (class "Default")
      (node (ref "U$1") (pin "CS2") (pinfunction "1_CS2") (pintype "bidirectional"))
      (node (ref "U$4") (pin "S1") (pinfunction "P$1_S1") (pintype "passive"))
    )
    (net (code "746") (name "Net-(U$1CZ-1)") (class "Default")
      (node (ref "U$1") (pin "CT2") (pinfunction "1_CT2") (pintype "bidirectional"))
      (node (ref "U$4") (pin "T1") (pinfunction "P$1_T1") (pintype "passive"))
    )
    (net (code "747") (name "Net-(U$1D-1)") (class "Default")
      (node (ref "U$1") (pin "AB2") (pinfunction "1_AB2") (pintype "bidirectional"))
      (node (ref "U$2") (pin "B1") (pinfunction "P$1_B1") (pintype "passive"))
    )
    (net (code "748") (name "Net-(U$1DA-1)") (class "Default")
      (node (ref "U$1") (pin "CU1") (pinfunction "1_CU1") (pintype "bidirectional"))
      (node (ref "U$4") (pin "U2") (pinfunction "P$1_U2") (pintype "passive"))
    )
    (net (code "749") (name "Net-(U$1DB-1)") (class "Default")
      (node (ref "U$1") (pin "CU2") (pinfunction "1_CU2") (pintype "bidirectional"))
      (node (ref "U$4") (pin "U1") (pinfunction "P$1_U1") (pintype "passive"))
    )
    (net (code "750") (name "Net-(U$1DC-1)") (class "Default")
      (node (ref "U$1") (pin "CV1") (pinfunction "1_CV1") (pintype "bidirectional"))
      (node (ref "U$4") (pin "V2") (pinfunction "P$1_V2") (pintype "passive"))
    )
    (net (code "751") (name "Net-(U$1DD-1)") (class "Default")
      (node (ref "U$1") (pin "CV2") (pinfunction "1_CV2") (pintype "bidirectional"))
      (node (ref "U$4") (pin "V1") (pinfunction "P$1_V1") (pintype "passive"))
    )
    (net (code "752") (name "Net-(U$1DE-1)") (class "Default")
      (node (ref "U$1") (pin "DA1") (pinfunction "1_DA1") (pintype "bidirectional"))
      (node (ref "U$5") (pin "A2") (pinfunction "P$1_A2") (pintype "passive"))
    )
    (net (code "753") (name "Net-(U$1DG-1)") (class "Default")
      (node (ref "U$1") (pin "DB1") (pinfunction "1_DB1") (pintype "bidirectional"))
      (node (ref "U$5") (pin "B2") (pinfunction "P$1_B2") (pintype "passive"))
    )
    (net (code "754") (name "Net-(U$1DH-1)") (class "Default")
      (node (ref "U$1") (pin "DB2") (pinfunction "1_DB2") (pintype "bidirectional"))
      (node (ref "U$5") (pin "B1") (pinfunction "P$1_B1") (pintype "passive"))
    )
    (net (code "755") (name "Net-(U$1DI-1)") (class "Default")
      (node (ref "U$1") (pin "DC1") (pinfunction "1_DC1") (pintype "bidirectional"))
      (node (ref "U$5") (pin "C2") (pinfunction "P$1_C2") (pintype "passive"))
    )
    (net (code "756") (name "Net-(U$1DK-1)") (class "Default")
      (node (ref "U$1") (pin "DD1") (pinfunction "1_DD1") (pintype "bidirectional"))
      (node (ref "U$5") (pin "D2") (pinfunction "P$1_D2") (pintype "passive"))
    )
    (net (code "757") (name "Net-(U$1DL-1)") (class "Default")
      (node (ref "U$1") (pin "DD2") (pinfunction "1_DD2") (pintype "bidirectional"))
      (node (ref "U$5") (pin "D1") (pinfunction "P$1_D1") (pintype "passive"))
    )
    (net (code "758") (name "Net-(U$1DM-1)") (class "Default")
      (node (ref "U$1") (pin "DE1") (pinfunction "1_DE1") (pintype "bidirectional"))
      (node (ref "U$5") (pin "E2") (pinfunction "P$1_E2") (pintype "passive"))
    )
    (net (code "759") (name "Net-(U$1DN-1)") (class "Default")
      (node (ref "U$1") (pin "DE2") (pinfunction "1_DE2") (pintype "bidirectional"))
      (node (ref "U$5") (pin "E1") (pinfunction "P$1_E1") (pintype "passive"))
    )
    (net (code "760") (name "Net-(U$1DO-1)") (class "Default")
      (node (ref "U$1") (pin "DF1") (pinfunction "1_DF1") (pintype "bidirectional"))
      (node (ref "U$5") (pin "F2") (pinfunction "P$1_F2") (pintype "passive"))
    )
    (net (code "761") (name "Net-(U$1DP-1)") (class "Default")
      (node (ref "U$1") (pin "DF2") (pinfunction "1_DF2") (pintype "bidirectional"))
      (node (ref "U$5") (pin "F1") (pinfunction "P$1_F1") (pintype "passive"))
    )
    (net (code "762") (name "Net-(U$1DQ-1)") (class "Default")
      (node (ref "U$1") (pin "DH1") (pinfunction "1_DH1") (pintype "bidirectional"))
      (node (ref "U$5") (pin "H2") (pinfunction "P$1_H2") (pintype "passive"))
    )
    (net (code "763") (name "Net-(U$1DR-1)") (class "Default")
      (node (ref "U$1") (pin "DH2") (pinfunction "1_DH2") (pintype "bidirectional"))
      (node (ref "U$5") (pin "H1") (pinfunction "P$1_H1") (pintype "passive"))
    )
    (net (code "764") (name "Net-(U$1DS-1)") (class "Default")
      (node (ref "U$1") (pin "DJ1") (pinfunction "1_DJ1") (pintype "bidirectional"))
      (node (ref "U$5") (pin "J2") (pinfunction "P$1_J2") (pintype "passive"))
    )
    (net (code "765") (name "Net-(U$1DT-1)") (class "Default")
      (node (ref "U$1") (pin "DJ2") (pinfunction "1_DJ2") (pintype "bidirectional"))
      (node (ref "U$5") (pin "J1") (pinfunction "P$1_J1") (pintype "passive"))
    )
    (net (code "766") (name "Net-(U$1DU-1)") (class "Default")
      (node (ref "U$1") (pin "DK1") (pinfunction "1_DK1") (pintype "bidirectional"))
      (node (ref "U$5") (pin "K2") (pinfunction "P$1_K2") (pintype "passive"))
    )
    (net (code "767") (name "Net-(U$1DV-1)") (class "Default")
      (node (ref "U$1") (pin "DK2") (pinfunction "1_DK2") (pintype "bidirectional"))
      (node (ref "U$5") (pin "K1") (pinfunction "P$1_K1") (pintype "passive"))
    )
    (net (code "768") (name "Net-(U$1DW-1)") (class "Default")
      (node (ref "U$1") (pin "DL1") (pinfunction "1_DL1") (pintype "bidirectional"))
      (node (ref "U$5") (pin "L2") (pinfunction "P$1_L2") (pintype "passive"))
    )
    (net (code "769") (name "Net-(U$1DX-1)") (class "Default")
      (node (ref "U$1") (pin "DL2") (pinfunction "1_DL2") (pintype "bidirectional"))
      (node (ref "U$5") (pin "L1") (pinfunction "P$1_L1") (pintype "passive"))
    )
    (net (code "770") (name "Net-(U$1DY-1)") (class "Default")
      (node (ref "U$1") (pin "DM1") (pinfunction "1_DM1") (pintype "bidirectional"))
      (node (ref "U$5") (pin "M2") (pinfunction "P$1_M2") (pintype "passive"))
    )
    (net (code "771") (name "Net-(U$1DZ-1)") (class "Default")
      (node (ref "U$1") (pin "DM2") (pinfunction "1_DM2") (pintype "bidirectional"))
      (node (ref "U$5") (pin "M1") (pinfunction "P$1_M1") (pintype "passive"))
    )
    (net (code "772") (name "Net-(U$1E-1)") (class "Default")
      (node (ref "U$1") (pin "AC1") (pinfunction "1_AC1") (pintype "bidirectional"))
      (node (ref "U$2") (pin "C2") (pinfunction "P$1_C2") (pintype "passive"))
    )
    (net (code "773") (name "Net-(U$1EA-1)") (class "Default")
      (node (ref "U$1") (pin "DN1") (pinfunction "1_DN1") (pintype "bidirectional"))
      (node (ref "U$5") (pin "N2") (pinfunction "P$1_N2") (pintype "passive"))
    )
    (net (code "774") (name "Net-(U$1EB-1)") (class "Default")
      (node (ref "U$1") (pin "DN2") (pinfunction "1_DN2") (pintype "bidirectional"))
      (node (ref "U$5") (pin "N1") (pinfunction "P$1_N1") (pintype "passive"))
    )
    (net (code "775") (name "Net-(U$1EC-1)") (class "Default")
      (node (ref "U$1") (pin "DP1") (pinfunction "1_DP1") (pintype "bidirectional"))
      (node (ref "U$5") (pin "P2") (pinfunction "P$1_P2") (pintype "passive"))
    )
    (net (code "776") (name "Net-(U$1ED-1)") (class "Default")
      (node (ref "U$1") (pin "DP2") (pinfunction "1_DP2") (pintype "bidirectional"))
      (node (ref "U$5") (pin "P1") (pinfunction "P$1_P1") (pintype "passive"))
    )
    (net (code "777") (name "Net-(U$1EE-1)") (class "Default")
      (node (ref "U$1") (pin "DR1") (pinfunction "1_DR1") (pintype "bidirectional"))
      (node (ref "U$5") (pin "R2") (pinfunction "P$1_R2") (pintype "passive"))
    )
    (net (code "778") (name "Net-(U$1EF-1)") (class "Default")
      (node (ref "U$1") (pin "DR2") (pinfunction "1_DR2") (pintype "bidirectional"))
      (node (ref "U$5") (pin "R1") (pinfunction "P$1_R1") (pintype "passive"))
    )
    (net (code "779") (name "Net-(U$1EG-1)") (class "Default")
      (node (ref "U$1") (pin "DS1") (pinfunction "1_DS1") (pintype "bidirectional"))
      (node (ref "U$5") (pin "S2") (pinfunction "P$1_S2") (pintype "passive"))
    )
    (net (code "780") (name "Net-(U$1EH-1)") (class "Default")
      (node (ref "U$1") (pin "DS2") (pinfunction "1_DS2") (pintype "bidirectional"))
      (node (ref "U$5") (pin "S1") (pinfunction "P$1_S1") (pintype "passive"))
    )
    (net (code "781") (name "Net-(U$1EJ-1)") (class "Default")
      (node (ref "U$1") (pin "DT2") (pinfunction "1_DT2") (pintype "bidirectional"))
      (node (ref "U$5") (pin "T1") (pinfunction "P$1_T1") (pintype "passive"))
    )
    (net (code "782") (name "Net-(U$1EK-1)") (class "Default")
      (node (ref "U$1") (pin "DU1") (pinfunction "1_DU1") (pintype "bidirectional"))
      (node (ref "U$5") (pin "U2") (pinfunction "P$1_U2") (pintype "passive"))
    )
    (net (code "783") (name "Net-(U$1EL-1)") (class "Default")
      (node (ref "U$1") (pin "DU2") (pinfunction "1_DU2") (pintype "bidirectional"))
      (node (ref "U$5") (pin "U1") (pinfunction "P$1_U1") (pintype "passive"))
    )
    (net (code "784") (name "Net-(U$1EM-1)") (class "Default")
      (node (ref "U$1") (pin "DV1") (pinfunction "1_DV1") (pintype "bidirectional"))
      (node (ref "U$5") (pin "V2") (pinfunction "P$1_V2") (pintype "passive"))
    )
    (net (code "785") (name "Net-(U$1EN-1)") (class "Default")
      (node (ref "U$1") (pin "DV2") (pinfunction "1_DV2") (pintype "bidirectional"))
      (node (ref "U$5") (pin "V1") (pinfunction "P$1_V1") (pintype "passive"))
    )
    (net (code "786") (name "Net-(U$1G-1)") (class "Default")
      (node (ref "U$1") (pin "AD1") (pinfunction "1_AD1") (pintype "bidirectional"))
      (node (ref "U$2") (pin "D2") (pinfunction "P$1_D2") (pintype "passive"))
    )
    (net (code "787") (name "Net-(U$1H-1)") (class "Default")
      (node (ref "U$1") (pin "AD2") (pinfunction "1_AD2") (pintype "bidirectional"))
      (node (ref "U$2") (pin "D1") (pinfunction "P$1_D1") (pintype "passive"))
    )
    (net (code "788") (name "Net-(U$1I-1)") (class "Default")
      (node (ref "U$1") (pin "AE1") (pinfunction "1_AE1") (pintype "bidirectional"))
      (node (ref "U$2") (pin "E2") (pinfunction "P$1_E2") (pintype "passive"))
    )
    (net (code "789") (name "Net-(U$1J-1)") (class "Default")
      (node (ref "U$1") (pin "AE2") (pinfunction "1_AE2") (pintype "bidirectional"))
      (node (ref "U$2") (pin "E1") (pinfunction "P$1_E1") (pintype "passive"))
    )
    (net (code "790") (name "Net-(U$1K-1)") (class "Default")
      (node (ref "U$1") (pin "AF1") (pinfunction "1_AF1") (pintype "bidirectional"))
      (node (ref "U$2") (pin "F2") (pinfunction "P$1_F2") (pintype "passive"))
    )
    (net (code "791") (name "Net-(U$1L-1)") (class "Default")
      (node (ref "U$1") (pin "AF2") (pinfunction "1_AF2") (pintype "bidirectional"))
      (node (ref "U$2") (pin "F1") (pinfunction "P$1_F1") (pintype "passive"))
    )
    (net (code "792") (name "Net-(U$1M-1)") (class "Default")
      (node (ref "U$1") (pin "AH1") (pinfunction "1_AH1") (pintype "bidirectional"))
      (node (ref "U$2") (pin "H2") (pinfunction "P$1_H2") (pintype "passive"))
    )
    (net (code "793") (name "Net-(U$1N-1)") (class "Default")
      (node (ref "U$1") (pin "AH2") (pinfunction "1_AH2") (pintype "bidirectional"))
      (node (ref "U$2") (pin "H1") (pinfunction "P$1_H1") (pintype "passive"))
    )
    (net (code "794") (name "Net-(U$1O-1)") (class "Default")
      (node (ref "U$1") (pin "AJ1") (pinfunction "1_AJ1") (pintype "bidirectional"))
      (node (ref "U$2") (pin "J2") (pinfunction "P$1_J2") (pintype "passive"))
    )
    (net (code "795") (name "Net-(U$1P-1)") (class "Default")
      (node (ref "U$1") (pin "AJ2") (pinfunction "1_AJ2") (pintype "bidirectional"))
      (node (ref "U$2") (pin "J1") (pinfunction "P$1_J1") (pintype "passive"))
    )
    (net (code "796") (name "Net-(U$1Q-1)") (class "Default")
      (node (ref "U$1") (pin "AK1") (pinfunction "1_AK1") (pintype "bidirectional"))
      (node (ref "U$2") (pin "K2") (pinfunction "P$1_K2") (pintype "passive"))
    )
    (net (code "797") (name "Net-(U$1R-1)") (class "Default")
      (node (ref "U$1") (pin "AK2") (pinfunction "1_AK2") (pintype "bidirectional"))
      (node (ref "U$2") (pin "K1") (pinfunction "P$1_K1") (pintype "passive"))
    )
    (net (code "798") (name "Net-(U$1S-1)") (class "Default")
      (node (ref "U$1") (pin "AL1") (pinfunction "1_AL1") (pintype "bidirectional"))
      (node (ref "U$2") (pin "L2") (pinfunction "P$1_L2") (pintype "passive"))
    )
    (net (code "799") (name "Net-(U$1T-1)") (class "Default")
      (node (ref "U$1") (pin "AL2") (pinfunction "1_AL2") (pintype "bidirectional"))
      (node (ref "U$2") (pin "L1") (pinfunction "P$1_L1") (pintype "passive"))
    )
    (net (code "800") (name "Net-(U$1U-1)") (class "Default")
      (node (ref "U$1") (pin "AM1") (pinfunction "1_AM1") (pintype "bidirectional"))
      (node (ref "U$2") (pin "M2") (pinfunction "P$1_M2") (pintype "passive"))
    )
    (net (code "801") (name "Net-(U$1V-1)") (class "Default")
      (node (ref "U$1") (pin "AM2") (pinfunction "1_AM2") (pintype "bidirectional"))
      (node (ref "U$2") (pin "M1") (pinfunction "P$1_M1") (pintype "passive"))
    )
    (net (code "802") (name "Net-(U$1W-1)") (class "Default")
      (node (ref "U$1") (pin "AN1") (pinfunction "1_AN1") (pintype "bidirectional"))
      (node (ref "U$2") (pin "N2") (pinfunction "P$1_N2") (pintype "passive"))
    )
    (net (code "803") (name "Net-(U$1X-1)") (class "Default")
      (node (ref "U$1") (pin "AN2") (pinfunction "1_AN2") (pintype "bidirectional"))
      (node (ref "U$2") (pin "N1") (pinfunction "P$1_N1") (pintype "passive"))
    )
    (net (code "804") (name "Net-(U$1Y-1)") (class "Default")
      (node (ref "U$1") (pin "AP1") (pinfunction "1_AP1") (pintype "bidirectional"))
      (node (ref "U$2") (pin "P2") (pinfunction "P$1_P2") (pintype "passive"))
    )
    (net (code "805") (name "Net-(U$1Z-1)") (class "Default")
      (node (ref "U$1") (pin "AP2") (pinfunction "1_AP2") (pintype "bidirectional"))
      (node (ref "U$2") (pin "P1") (pinfunction "P$1_P1") (pintype "passive"))
    )
    (net (code "806") (name "VCC") (class "Default")
      (node (ref "C1") (pin "1") (pinfunction "1_1") (pintype "passive"))
      (node (ref "C10") (pin "1") (pinfunction "1_1") (pintype "passive"))
      (node (ref "C11") (pin "1") (pinfunction "1_1") (pintype "passive"))
      (node (ref "C12") (pin "1") (pinfunction "1_1") (pintype "passive"))
      (node (ref "C13") (pin "1") (pinfunction "1_1") (pintype "passive"))
      (node (ref "C14") (pin "1") (pinfunction "1_1") (pintype "passive"))
      (node (ref "C15") (pin "1") (pinfunction "1_1") (pintype "passive"))
      (node (ref "C16") (pin "1") (pinfunction "1_1") (pintype "passive"))
      (node (ref "C17") (pin "1") (pinfunction "1_1") (pintype "passive"))
      (node (ref "C18") (pin "1") (pinfunction "1_1") (pintype "passive"))
      (node (ref "C19") (pin "1") (pinfunction "1_1") (pintype "passive"))
      (node (ref "C2") (pin "1") (pinfunction "1_1") (pintype "passive"))
      (node (ref "C20") (pin "1") (pinfunction "1_1") (pintype "passive"))
      (node (ref "C21") (pin "1") (pinfunction "1_1") (pintype "passive"))
      (node (ref "C22") (pin "1") (pinfunction "1_1") (pintype "passive"))
      (node (ref "C23") (pin "1") (pinfunction "1_1") (pintype "passive"))
      (node (ref "C24") (pin "1") (pinfunction "1_1") (pintype "passive"))
      (node (ref "C25") (pin "1") (pinfunction "1_1") (pintype "passive"))
      (node (ref "C26") (pin "1") (pinfunction "1_1") (pintype "passive"))
      (node (ref "C27") (pin "1") (pinfunction "1_1") (pintype "passive"))
      (node (ref "C28") (pin "1") (pinfunction "1_1") (pintype "passive"))
      (node (ref "C29") (pin "1") (pinfunction "1_1") (pintype "passive"))
      (node (ref "C3") (pin "1") (pinfunction "1_1") (pintype "passive"))
      (node (ref "C30") (pin "1") (pinfunction "1_1") (pintype "passive"))
      (node (ref "C31") (pin "1") (pinfunction "1_1") (pintype "passive"))
      (node (ref "C32") (pin "1") (pinfunction "1_1") (pintype "passive"))
      (node (ref "C33") (pin "1") (pinfunction "1_1") (pintype "passive"))
      (node (ref "C34") (pin "1") (pinfunction "1_1") (pintype "passive"))
      (node (ref "C35") (pin "1") (pinfunction "1_1") (pintype "passive"))
      (node (ref "C36") (pin "1") (pinfunction "1_1") (pintype "passive"))
      (node (ref "C37") (pin "1") (pinfunction "1_1") (pintype "passive"))
      (node (ref "C38") (pin "1") (pinfunction "1_1") (pintype "passive"))
      (node (ref "C39") (pin "+") (pinfunction "+_+") (pintype "passive"))
      (node (ref "C4") (pin "1") (pinfunction "1_1") (pintype "passive"))
      (node (ref "C40") (pin "+") (pinfunction "+_+") (pintype "passive"))
      (node (ref "C5") (pin "1") (pinfunction "1_1") (pintype "passive"))
      (node (ref "C6") (pin "1") (pinfunction "1_1") (pintype "passive"))
      (node (ref "C7") (pin "1") (pinfunction "1_1") (pintype "passive"))
      (node (ref "C8") (pin "1") (pinfunction "1_1") (pintype "passive"))
      (node (ref "C9") (pin "1") (pinfunction "1_1") (pintype "passive"))
      (node (ref "SV10") (pin "9") (pinfunction "9_9") (pintype "passive"))
      (node (ref "SV12") (pin "9") (pinfunction "9_9") (pintype "passive"))
      (node (ref "SV14") (pin "9") (pinfunction "9_9") (pintype "passive"))
      (node (ref "SV16") (pin "9") (pinfunction "9_9") (pintype "passive"))
      (node (ref "SV18") (pin "9") (pinfunction "9_9") (pintype "passive"))
      (node (ref "SV2") (pin "9") (pinfunction "9_9") (pintype "passive"))
      (node (ref "SV20") (pin "9") (pinfunction "9_9") (pintype "passive"))
      (node (ref "SV22") (pin "9") (pinfunction "9_9") (pintype "passive"))
      (node (ref "SV24") (pin "9") (pinfunction "9_9") (pintype "passive"))
      (node (ref "SV26") (pin "9") (pinfunction "9_9") (pintype "passive"))
      (node (ref "SV28") (pin "9") (pinfunction "9_9") (pintype "passive"))
      (node (ref "SV30") (pin "9") (pinfunction "9_9") (pintype "passive"))
      (node (ref "SV32") (pin "9") (pinfunction "9_9") (pintype "passive"))
      (node (ref "SV34") (pin "9") (pinfunction "9_9") (pintype "passive"))
      (node (ref "SV36") (pin "9") (pinfunction "9_9") (pintype "passive"))
      (node (ref "SV38") (pin "9") (pinfunction "9_9") (pintype "passive"))
      (node (ref "SV4") (pin "9") (pinfunction "9_9") (pintype "passive"))
      (node (ref "SV40") (pin "9") (pinfunction "9_9") (pintype "passive"))
      (node (ref "SV42") (pin "9") (pinfunction "9_9") (pintype "passive"))
      (node (ref "SV44") (pin "9") (pinfunction "9_9") (pintype "passive"))
      (node (ref "SV46") (pin "9") (pinfunction "9_9") (pintype "passive"))
      (node (ref "SV48") (pin "9") (pinfunction "9_9") (pintype "passive"))
      (node (ref "SV50") (pin "9") (pinfunction "9_9") (pintype "passive"))
      (node (ref "SV52") (pin "9") (pinfunction "9_9") (pintype "passive"))
      (node (ref "SV54") (pin "9") (pinfunction "9_9") (pintype "passive"))
      (node (ref "SV56") (pin "9") (pinfunction "9_9") (pintype "passive"))
      (node (ref "SV58") (pin "9") (pinfunction "9_9") (pintype "passive"))
      (node (ref "SV6") (pin "9") (pinfunction "9_9") (pintype "passive"))
      (node (ref "SV60") (pin "9") (pinfunction "9_9") (pintype "passive"))
      (node (ref "SV62") (pin "13") (pinfunction "13_13") (pintype "passive"))
      (node (ref "SV64") (pin "13") (pinfunction "13_13") (pintype "passive"))
      (node (ref "SV66") (pin "13") (pinfunction "13_13") (pintype "passive"))
      (node (ref "SV68") (pin "13") (pinfunction "13_13") (pintype "passive"))
      (node (ref "SV70") (pin "13") (pinfunction "13_13") (pintype "passive"))
      (node (ref "SV72") (pin "13") (pinfunction "13_13") (pintype "passive"))
      (node (ref "SV74") (pin "13") (pinfunction "13_13") (pintype "passive"))
      (node (ref "SV76") (pin "13") (pinfunction "13_13") (pintype "passive"))
      (node (ref "SV8") (pin "9") (pinfunction "9_9") (pintype "passive"))
      (node (ref "U$1") (pin "AA2") (pinfunction "1_AA2") (pintype "bidirectional"))
      (node (ref "U$1") (pin "BA2") (pinfunction "1_BA2") (pintype "bidirectional"))
      (node (ref "U$1") (pin "CA2") (pinfunction "1_CA2") (pintype "bidirectional"))
      (node (ref "U$1") (pin "DA2") (pinfunction "1_DA2") (pintype "bidirectional"))
      (node (ref "U$2") (pin "A1") (pinfunction "P$1_A1") (pintype "passive"))
      (node (ref "U$3") (pin "A1") (pinfunction "P$1_A1") (pintype "passive"))
      (node (ref "U$4") (pin "A1") (pinfunction "P$1_A1") (pintype "passive"))
      (node (ref "U$5") (pin "A1") (pinfunction "P$1_A1") (pintype "passive"))
    )
  )
)
